# mainboard-revb.net
KiCad netlist of a schematic drawn in EAGLE
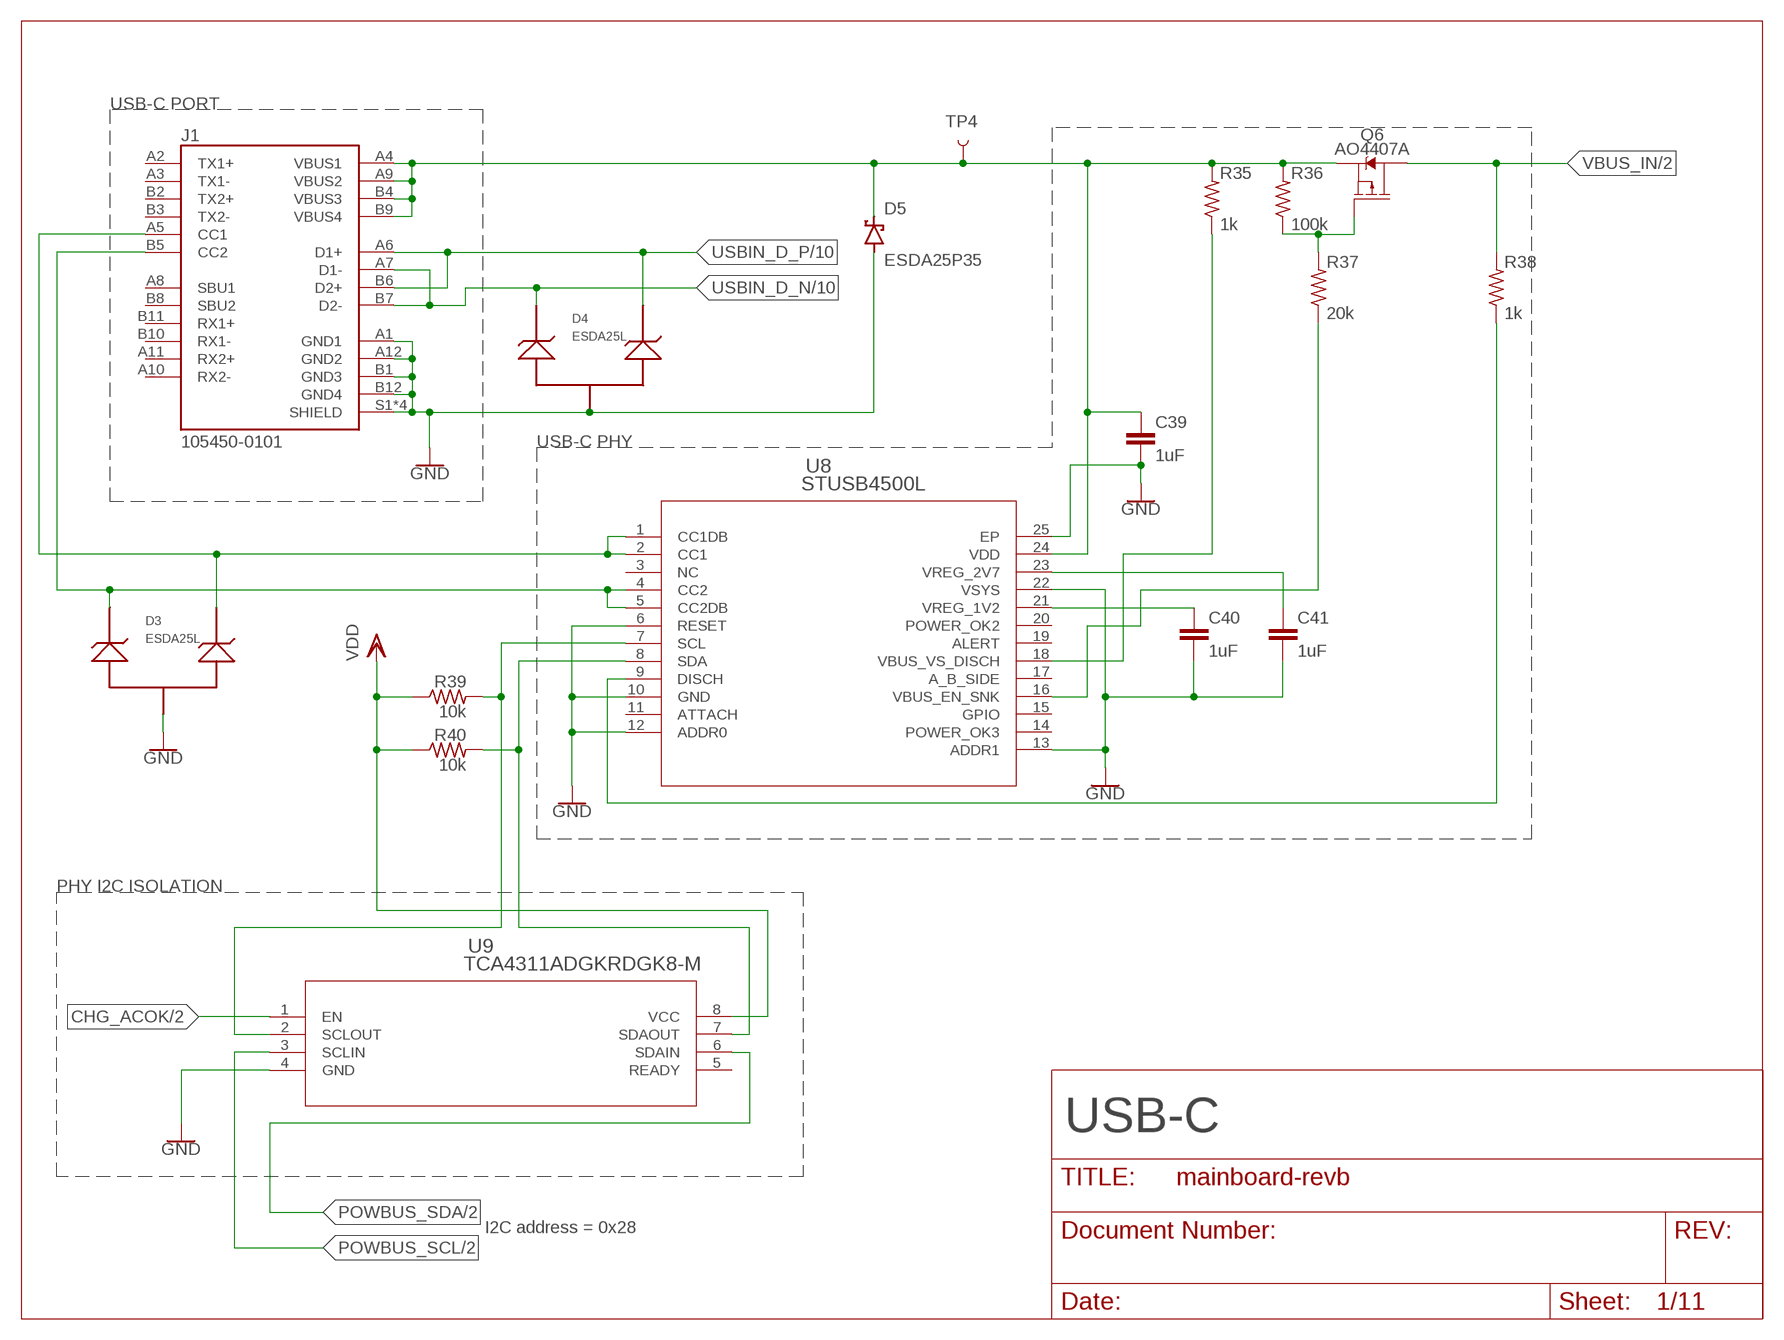
[diagram p0: schematic, sheet 1]
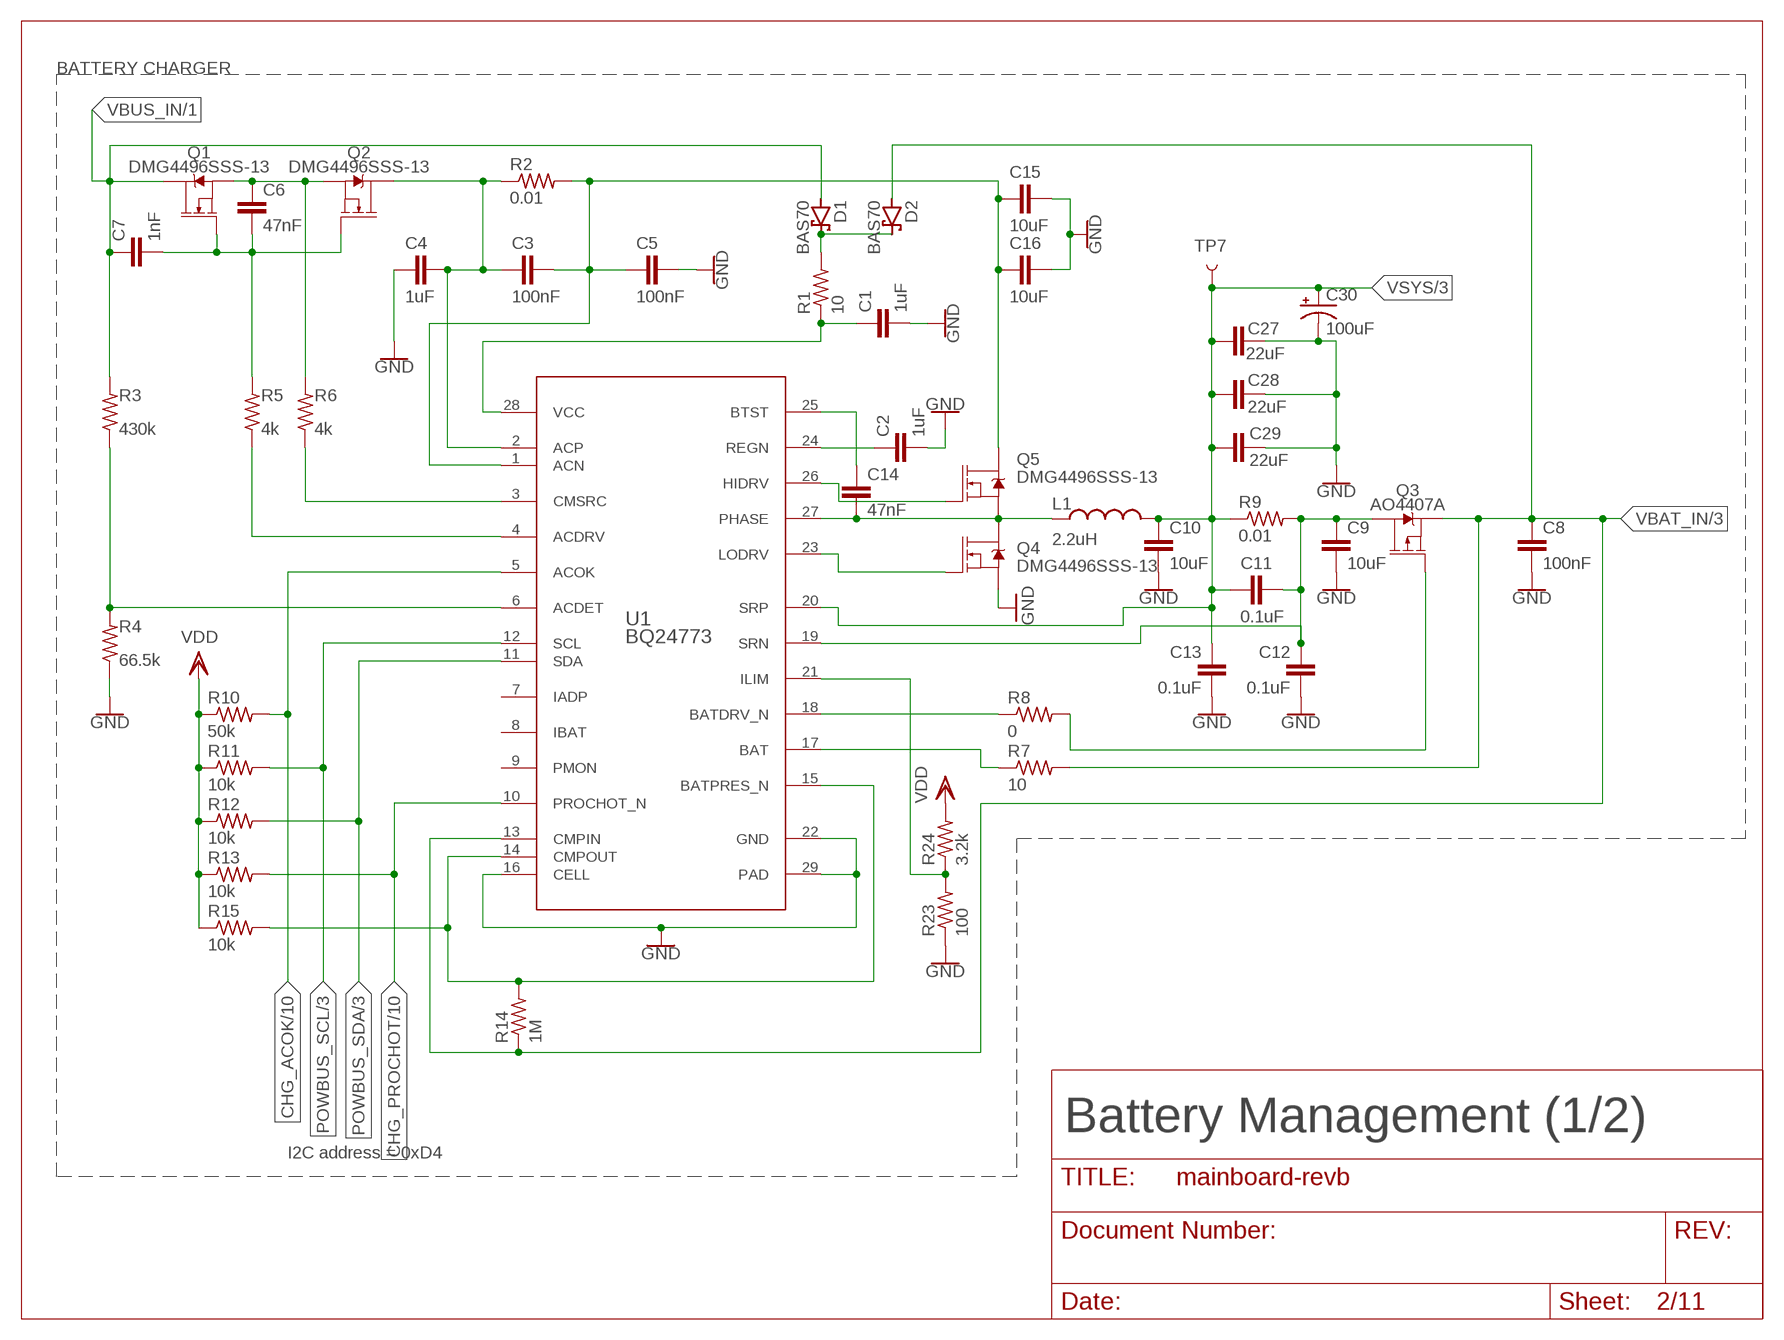
[diagram p1: schematic, sheet 2]
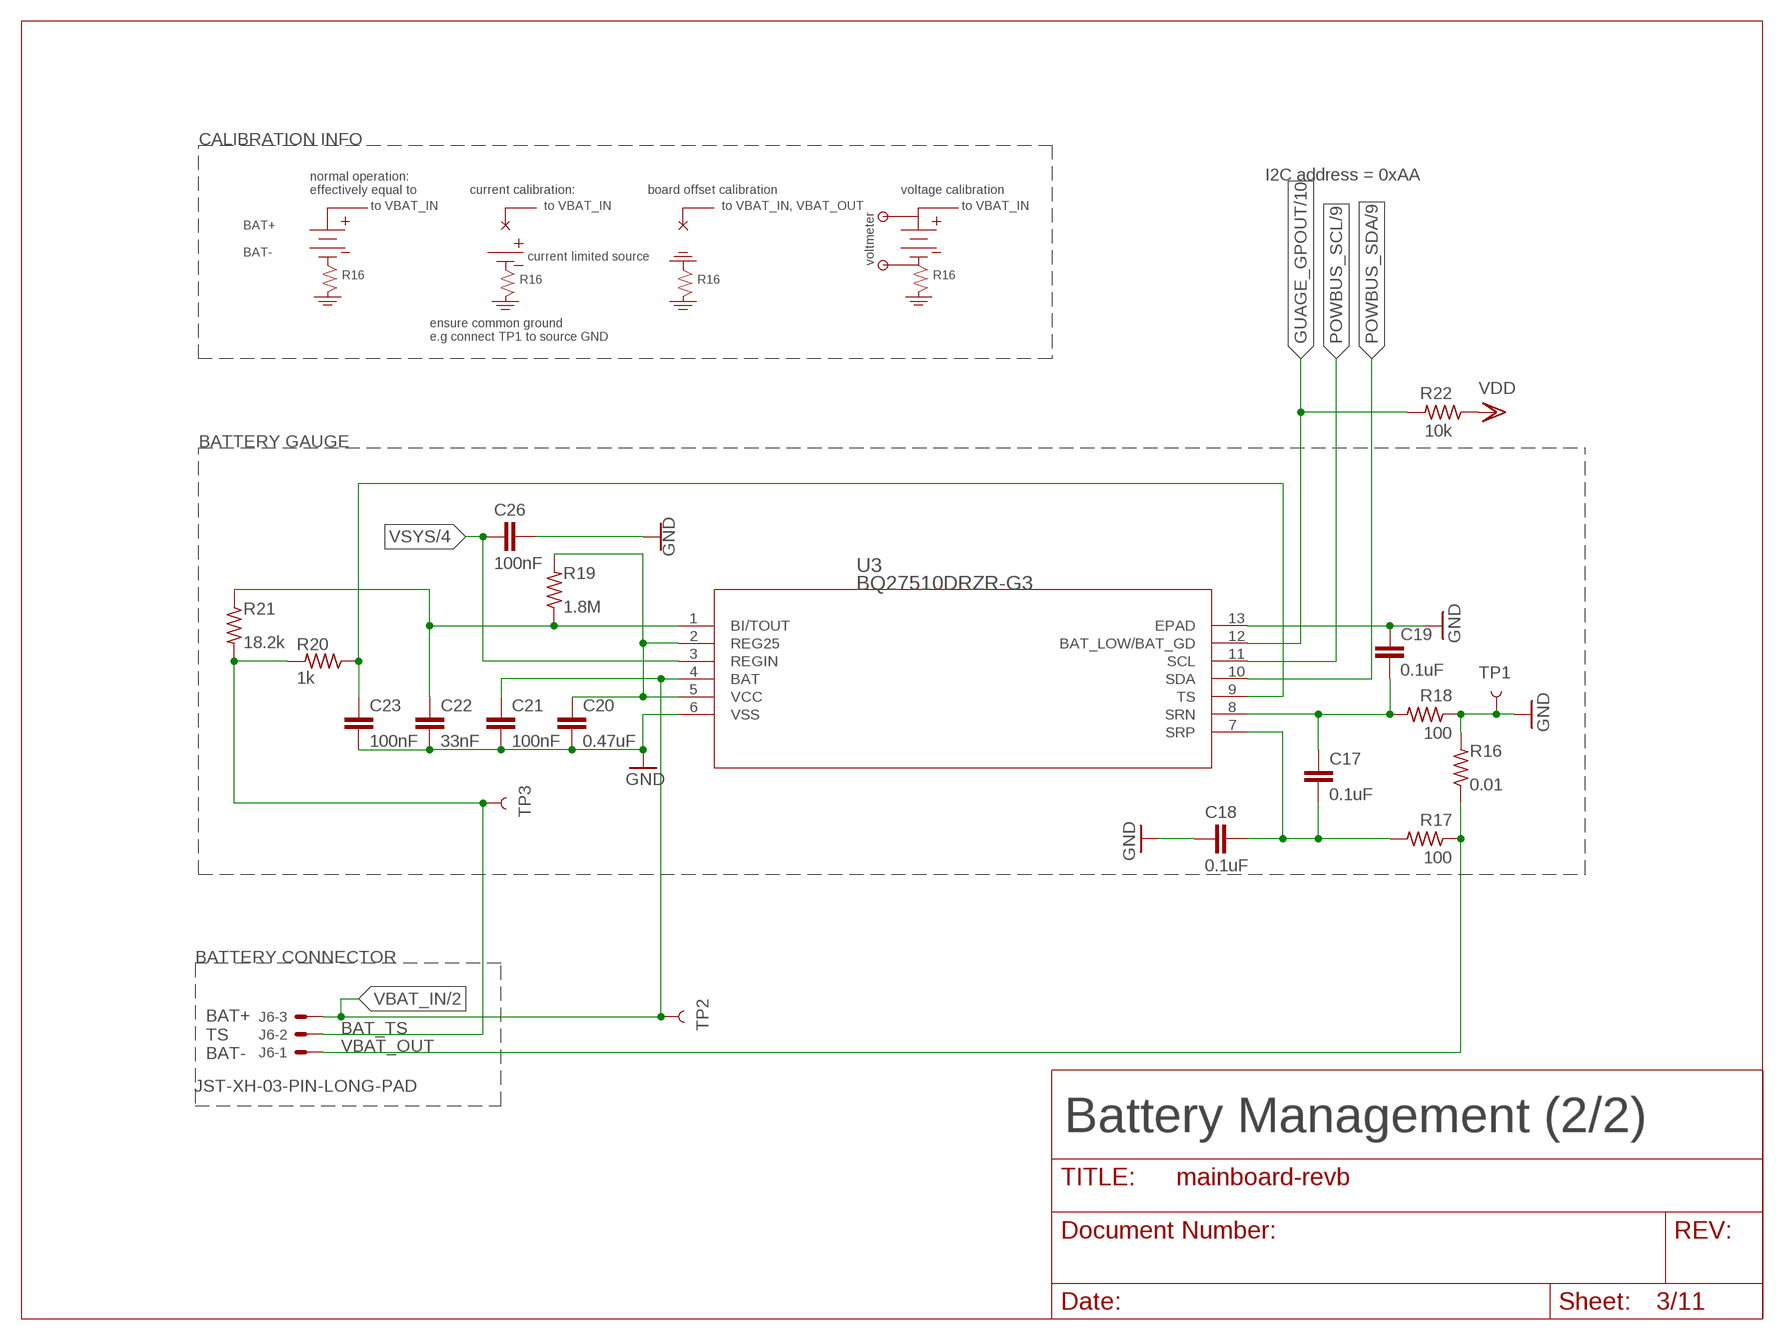
[diagram p2: schematic, sheet 3]
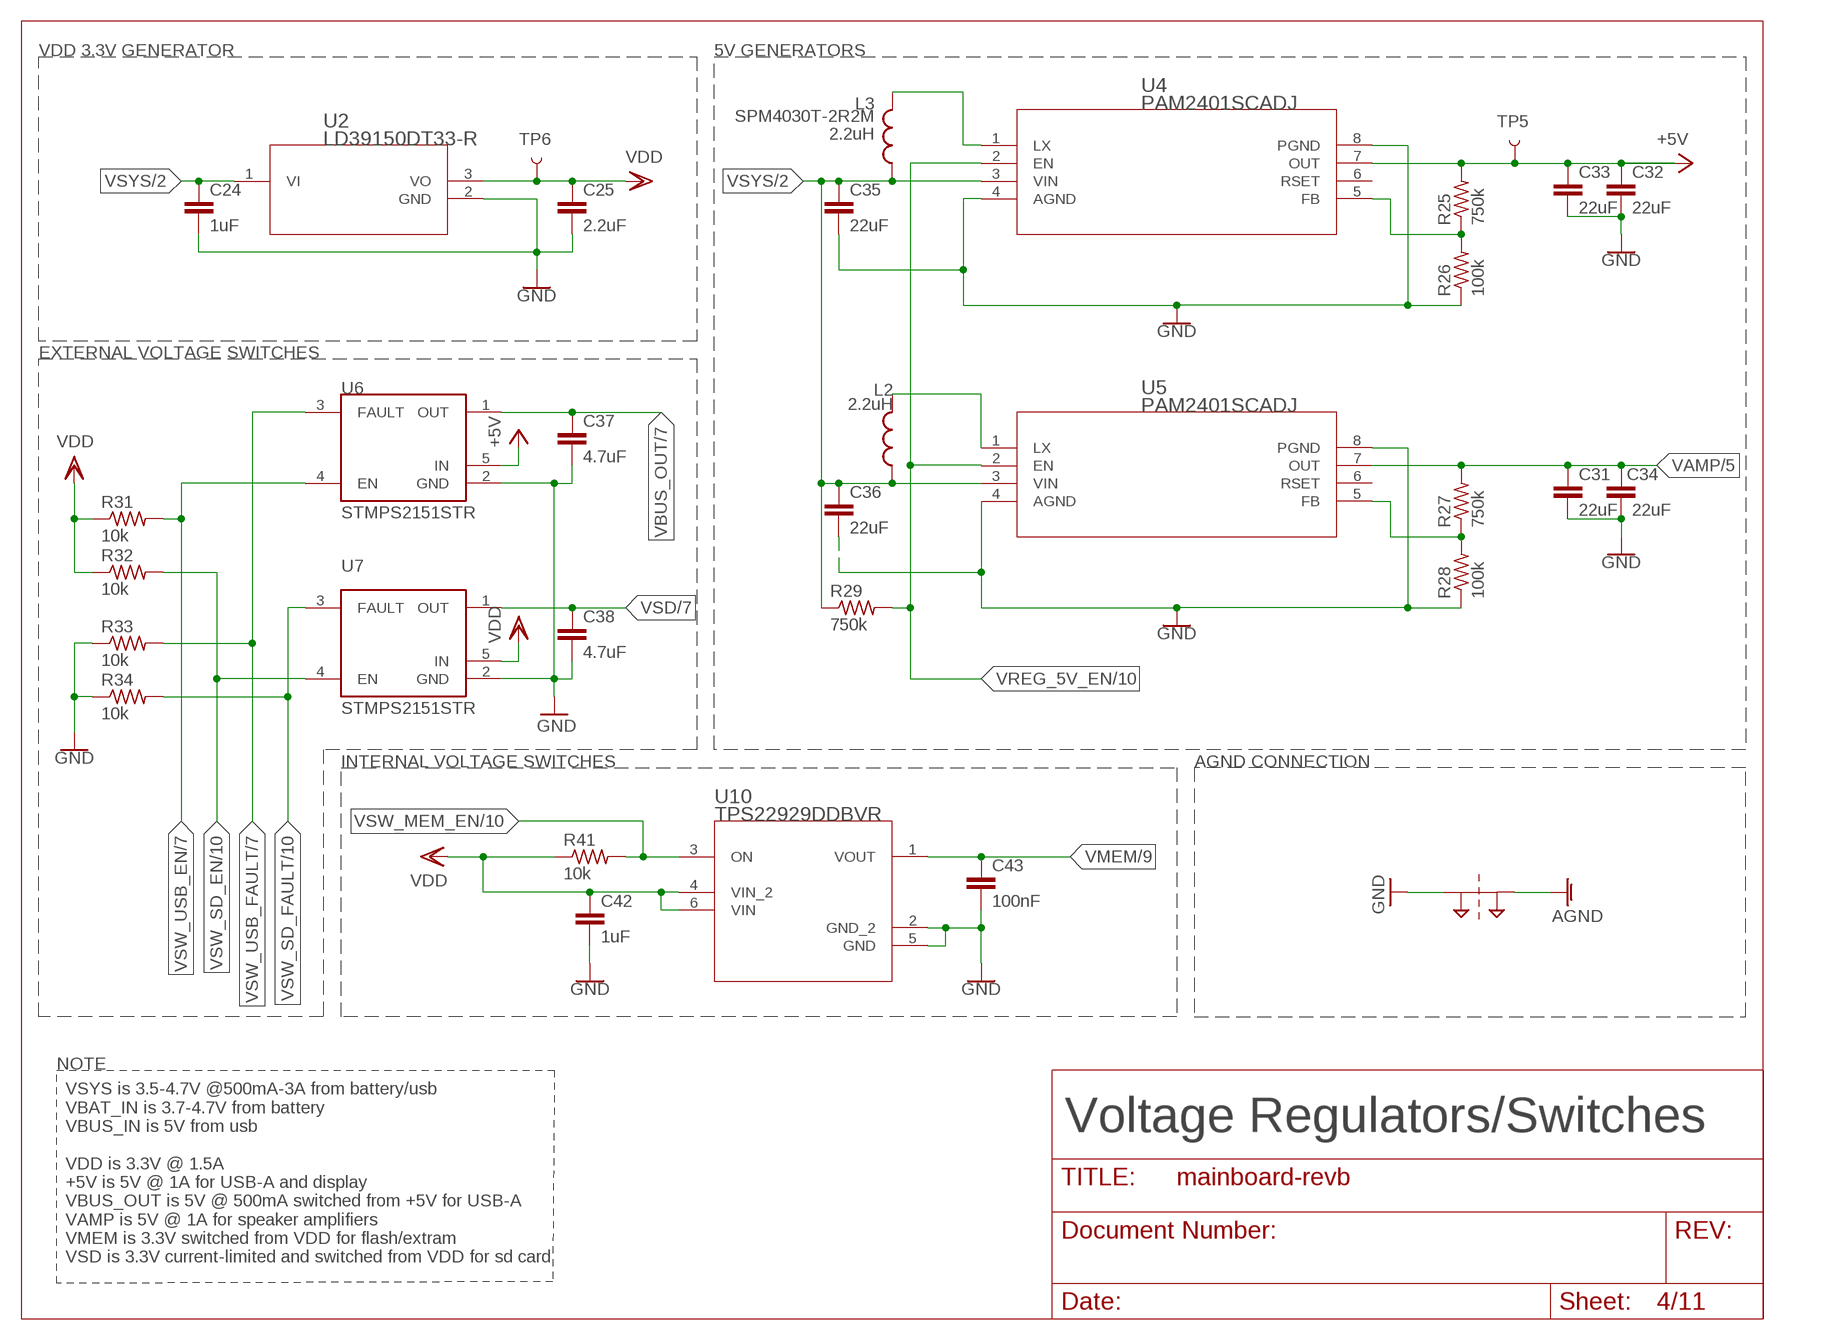
[diagram p3: schematic, sheet 4]
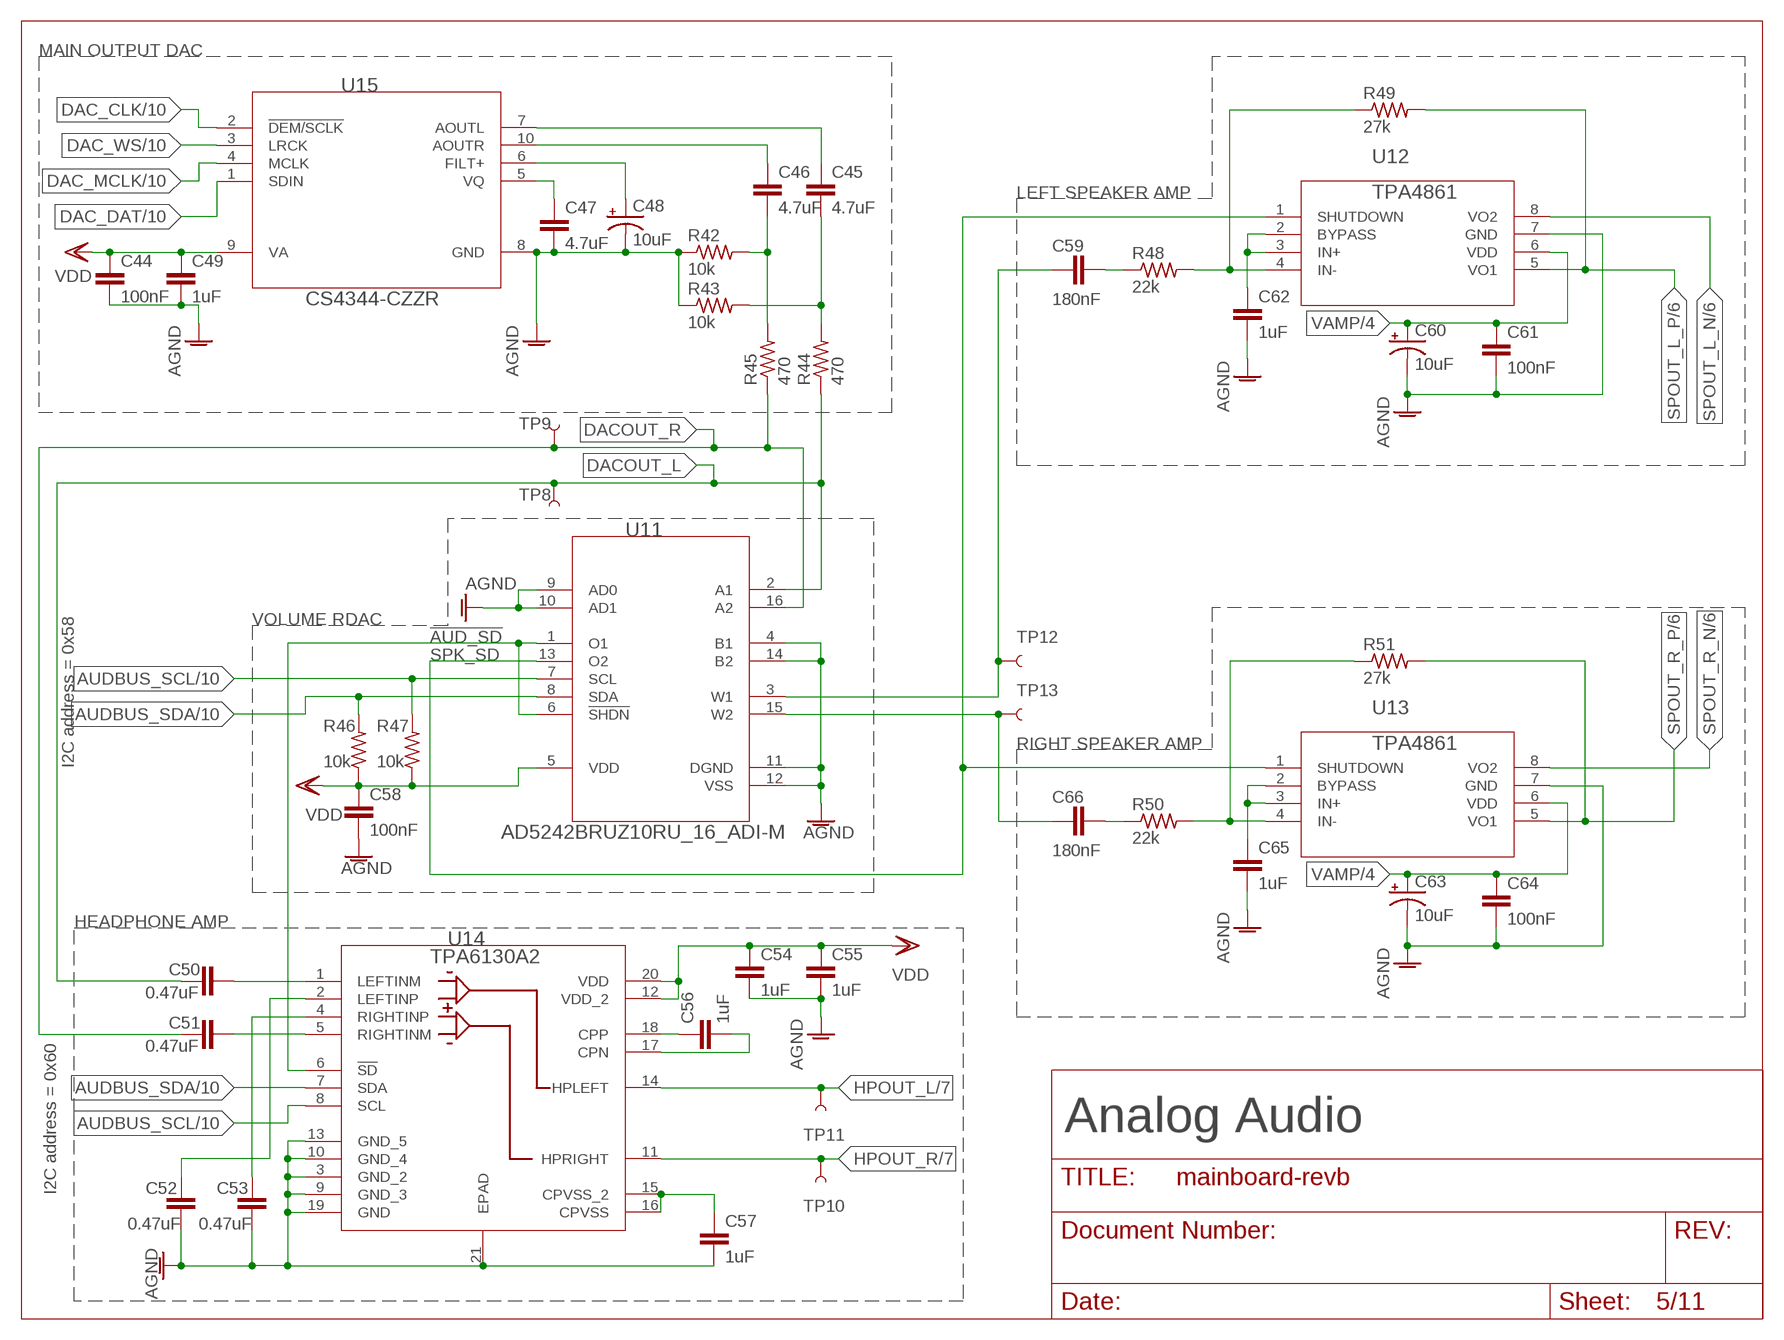
[diagram p4: schematic, sheet 5]
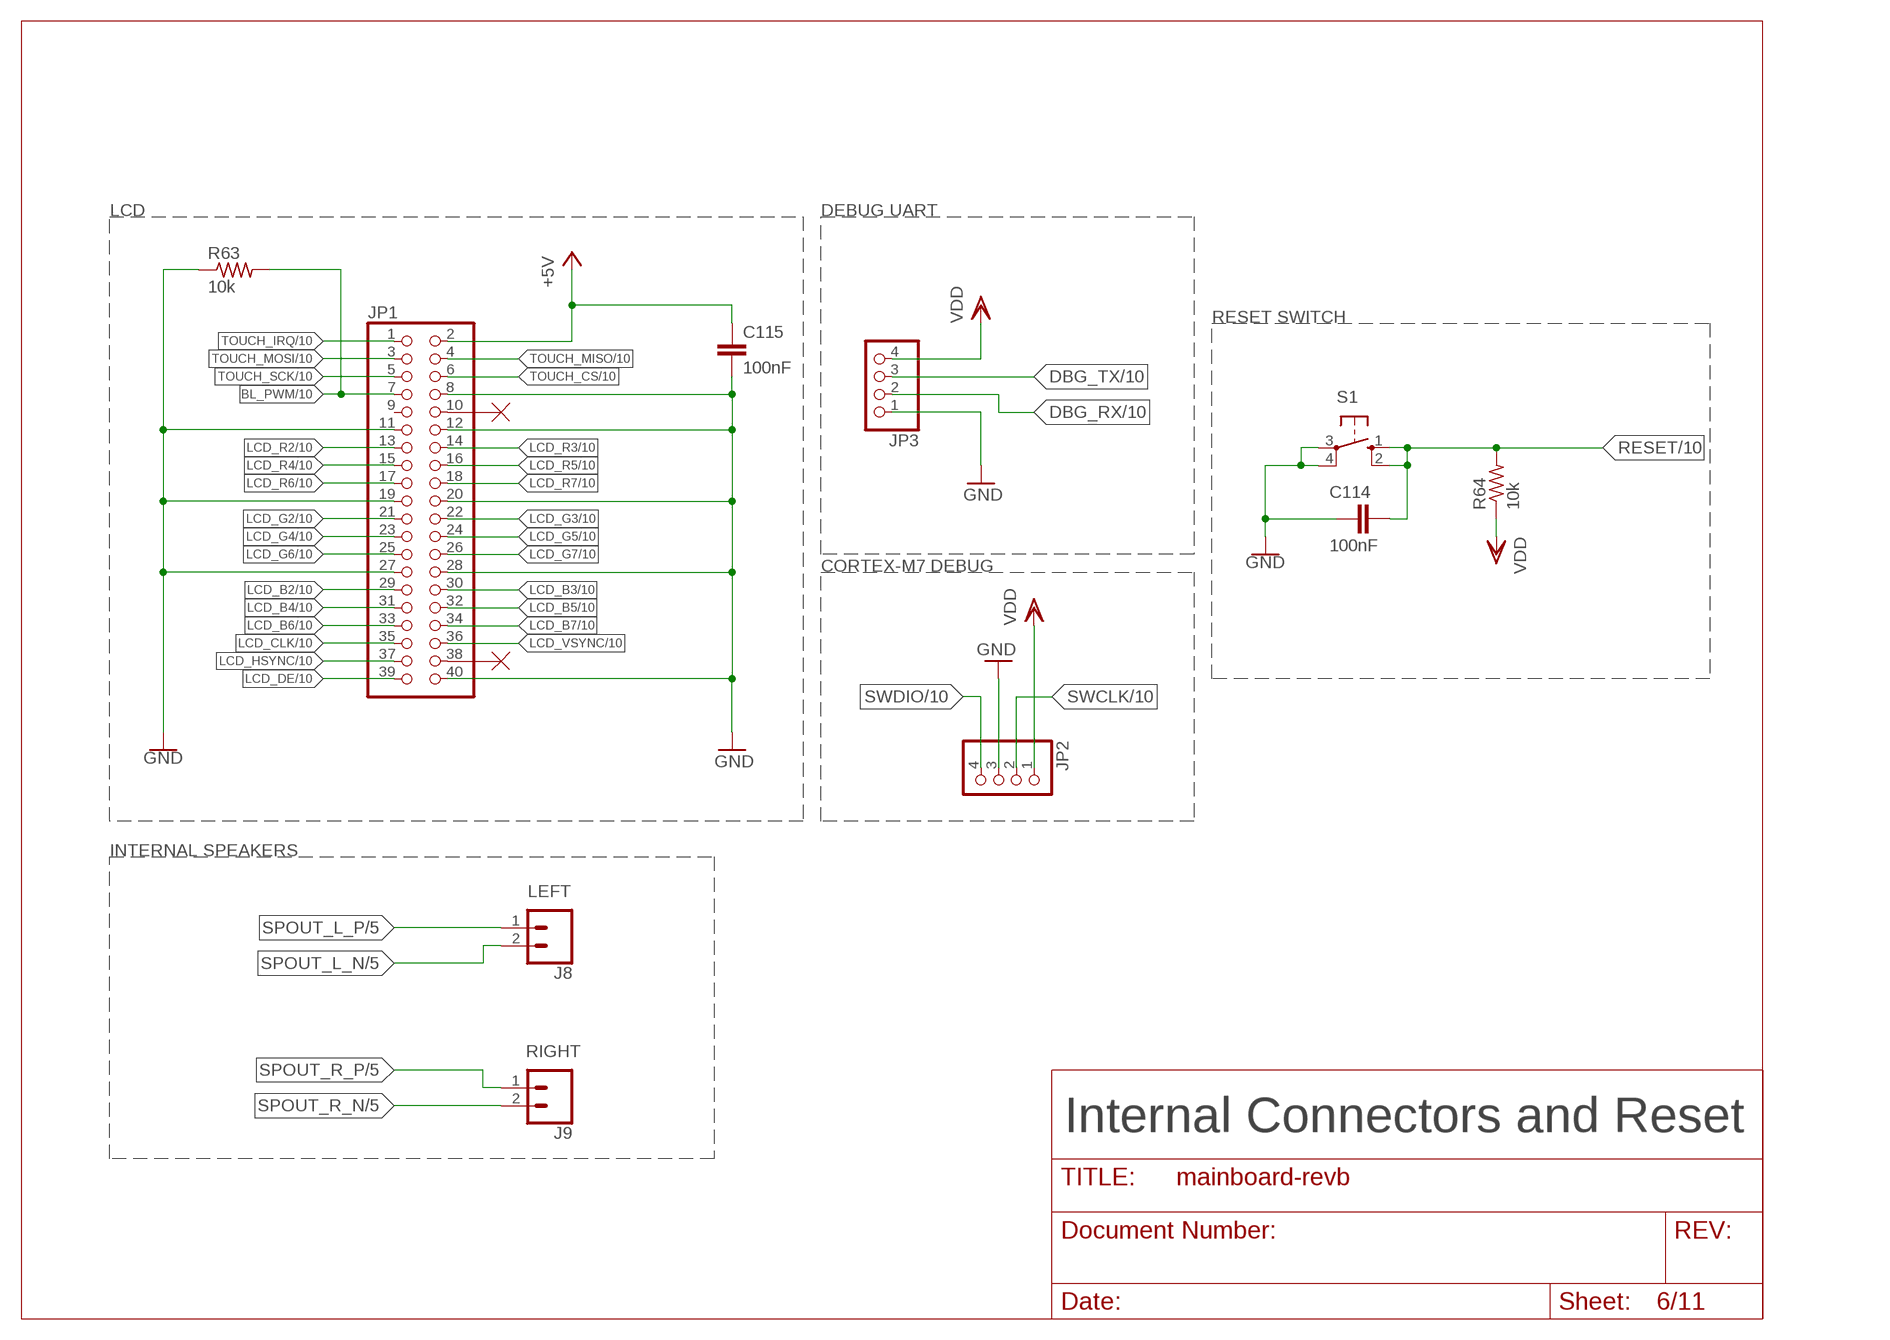
[diagram p5: schematic, sheet 6]
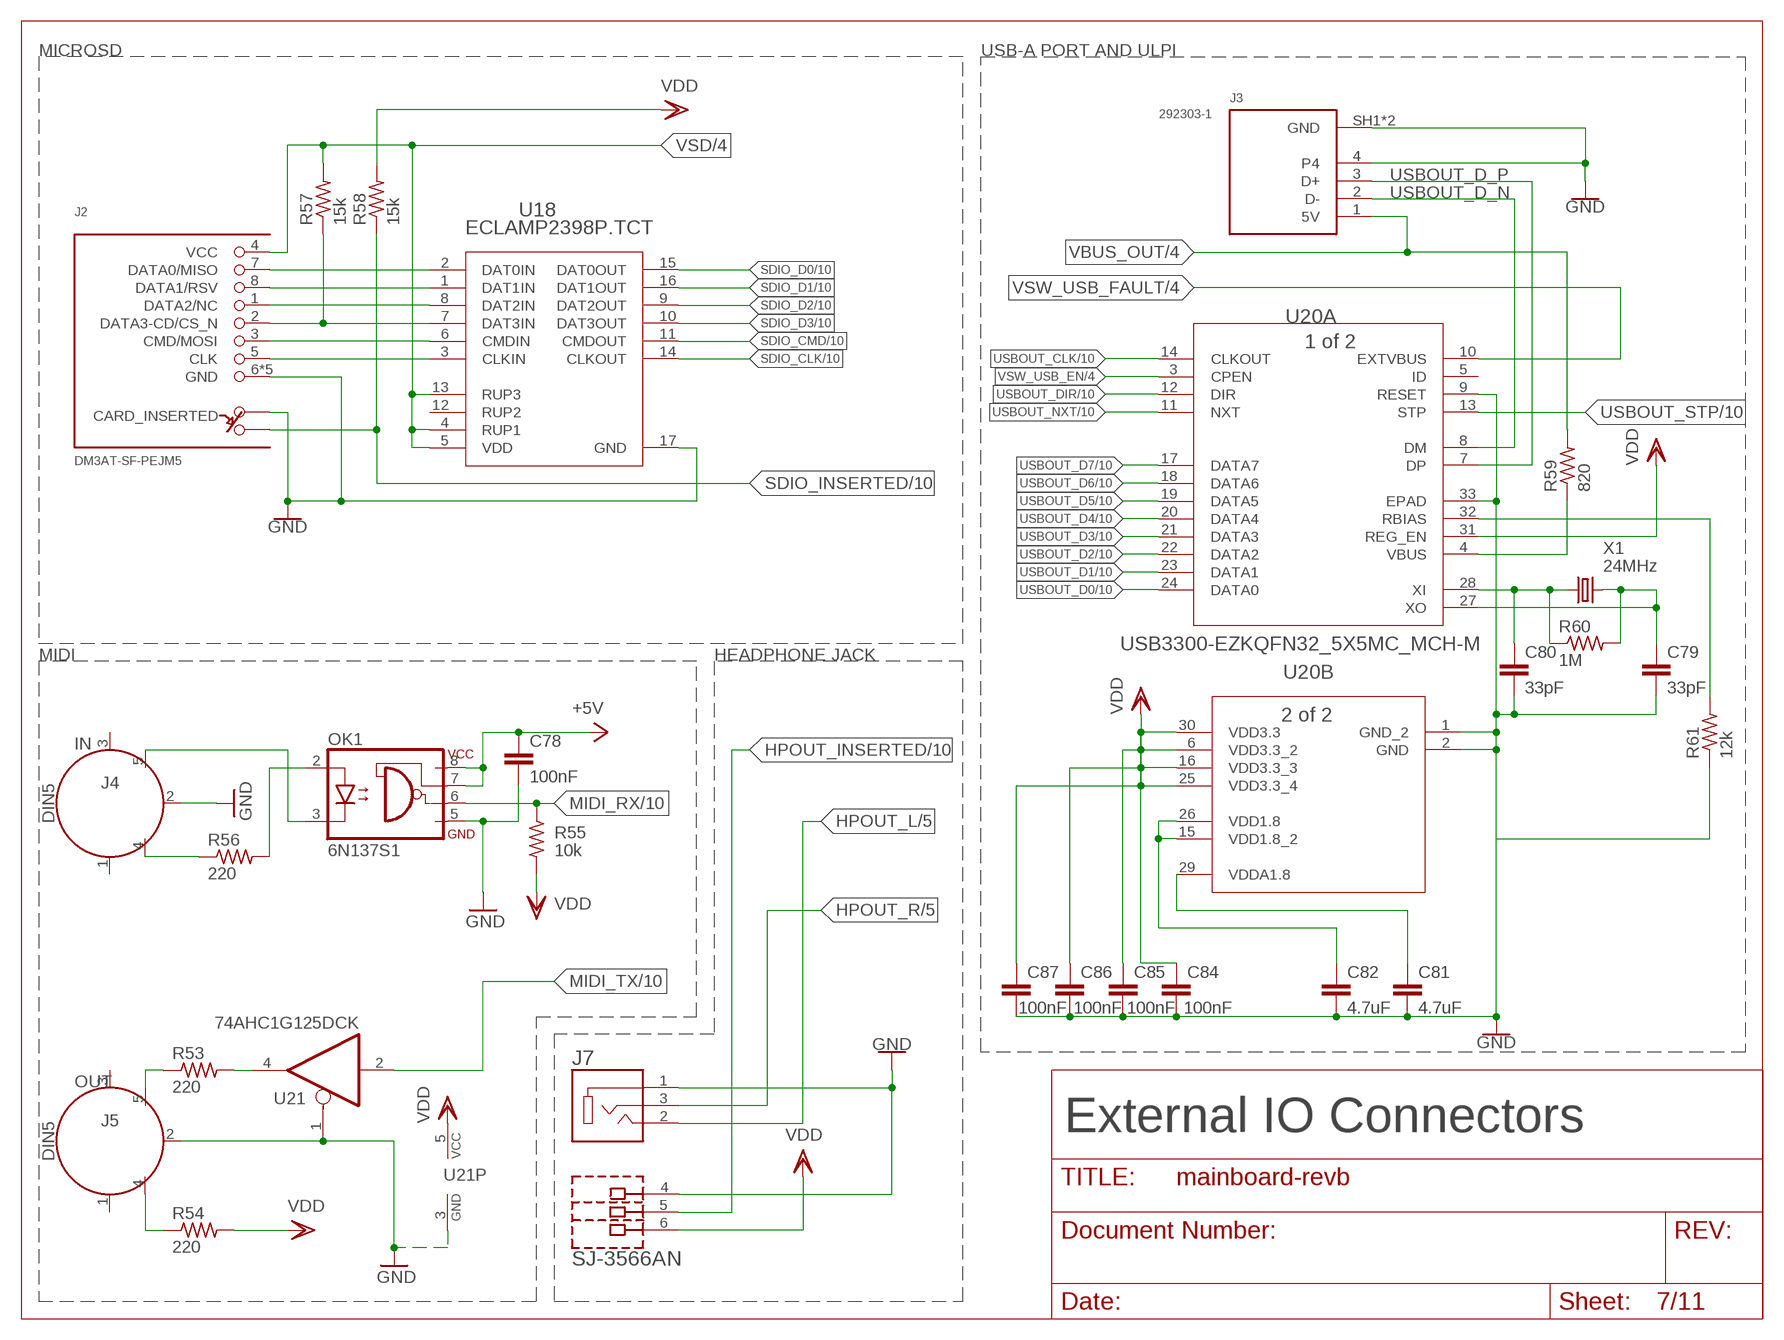
[diagram p6: schematic, sheet 7]
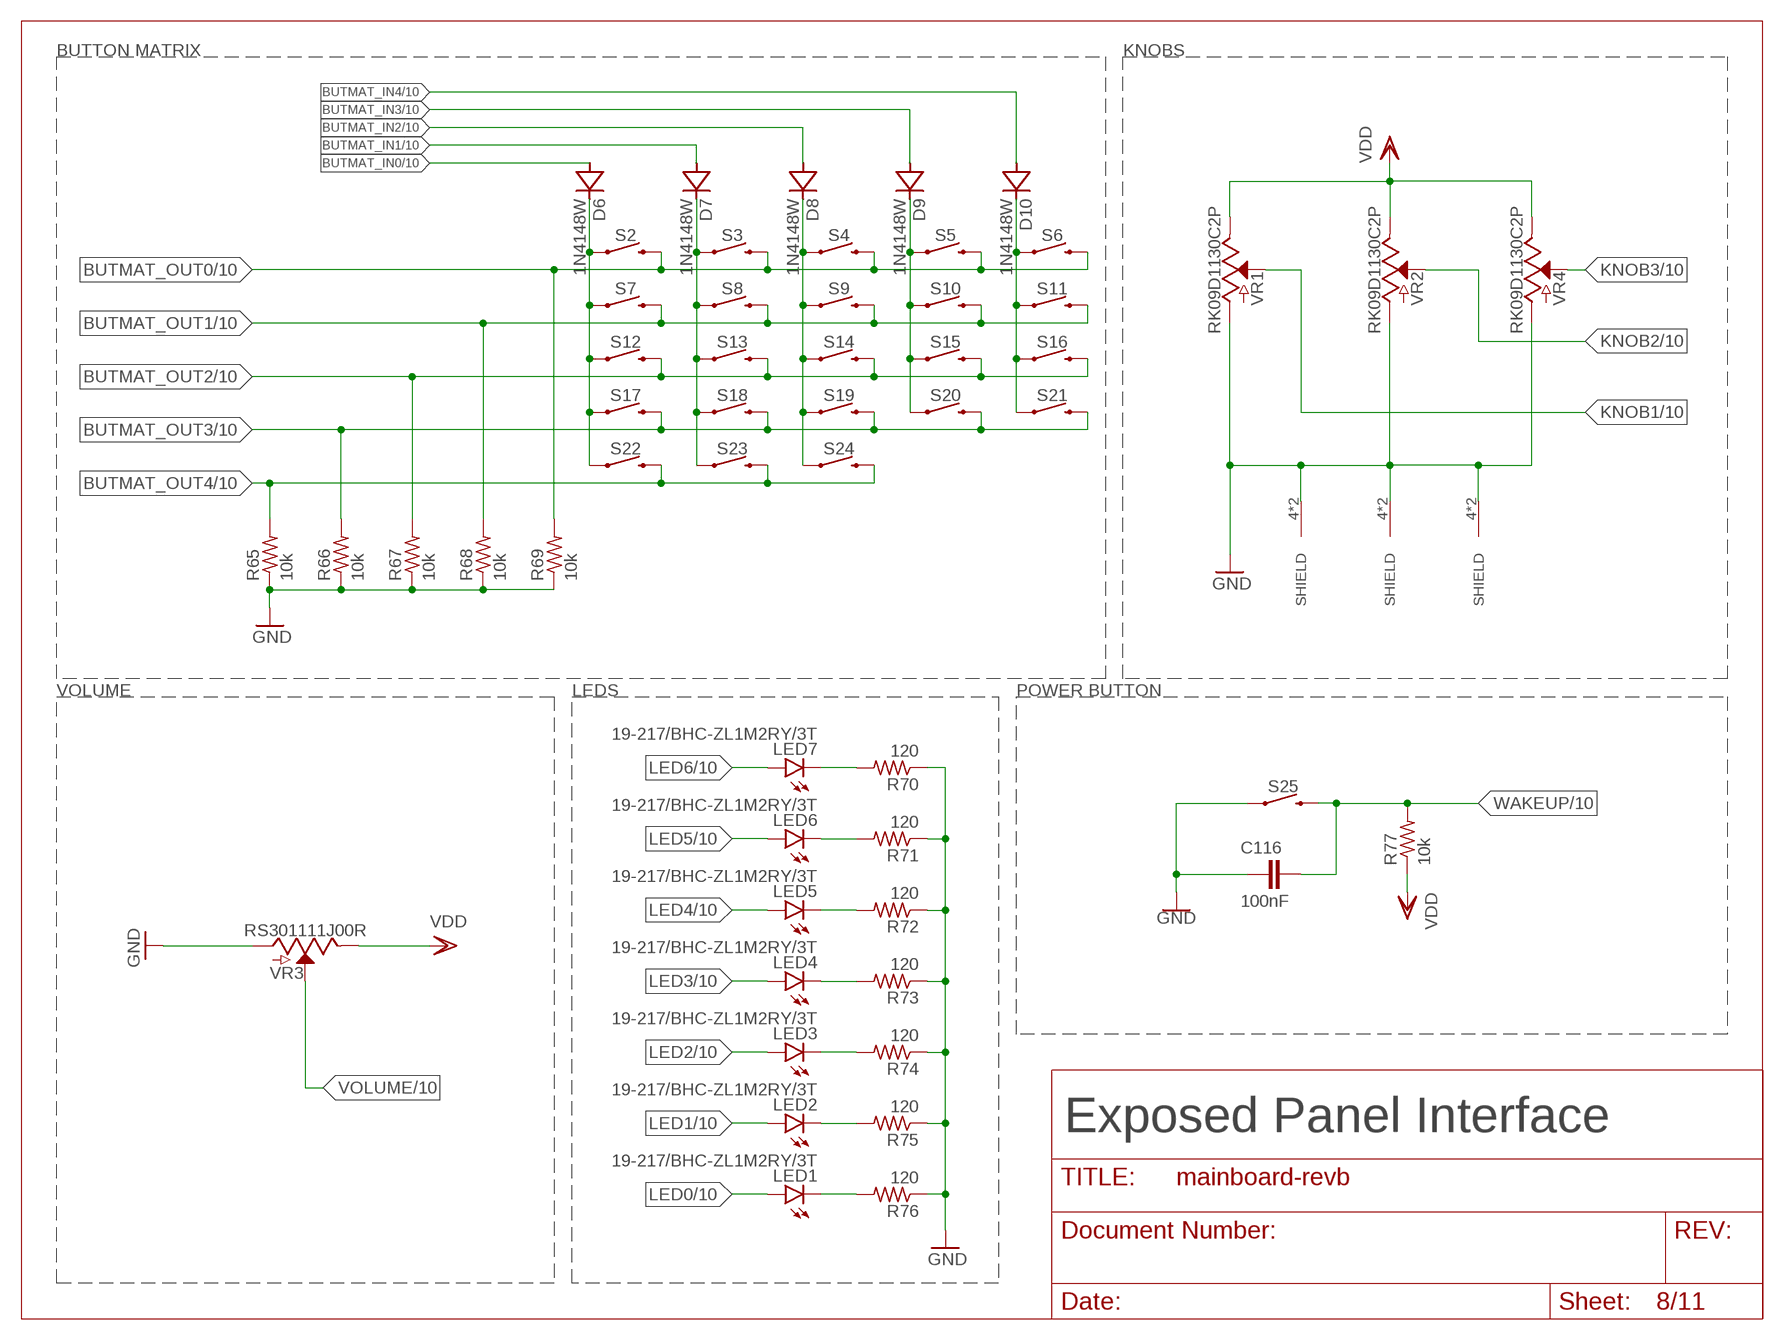
[diagram p7: schematic, sheet 8]
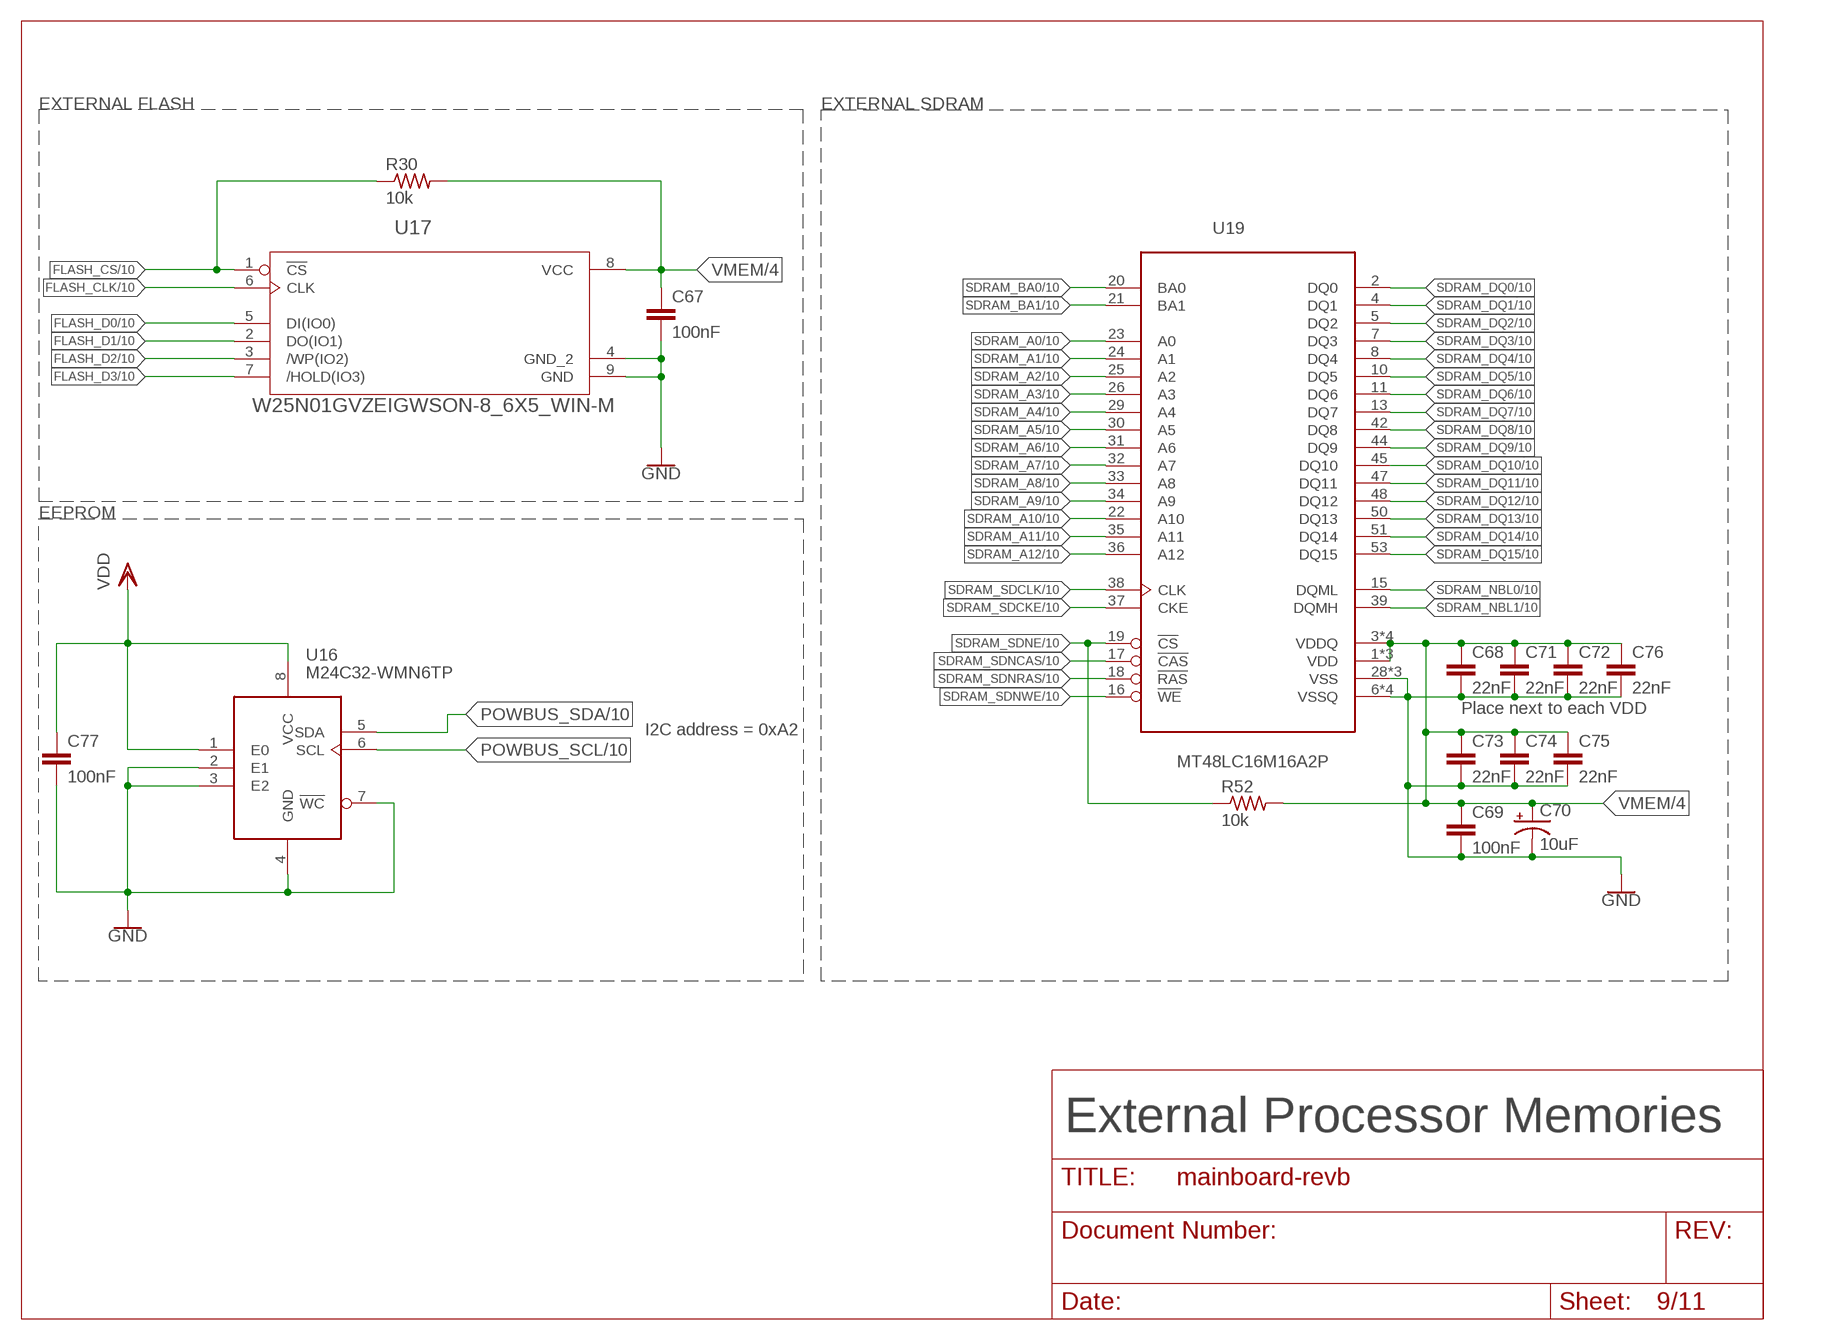
[diagram p8: schematic, sheet 9]
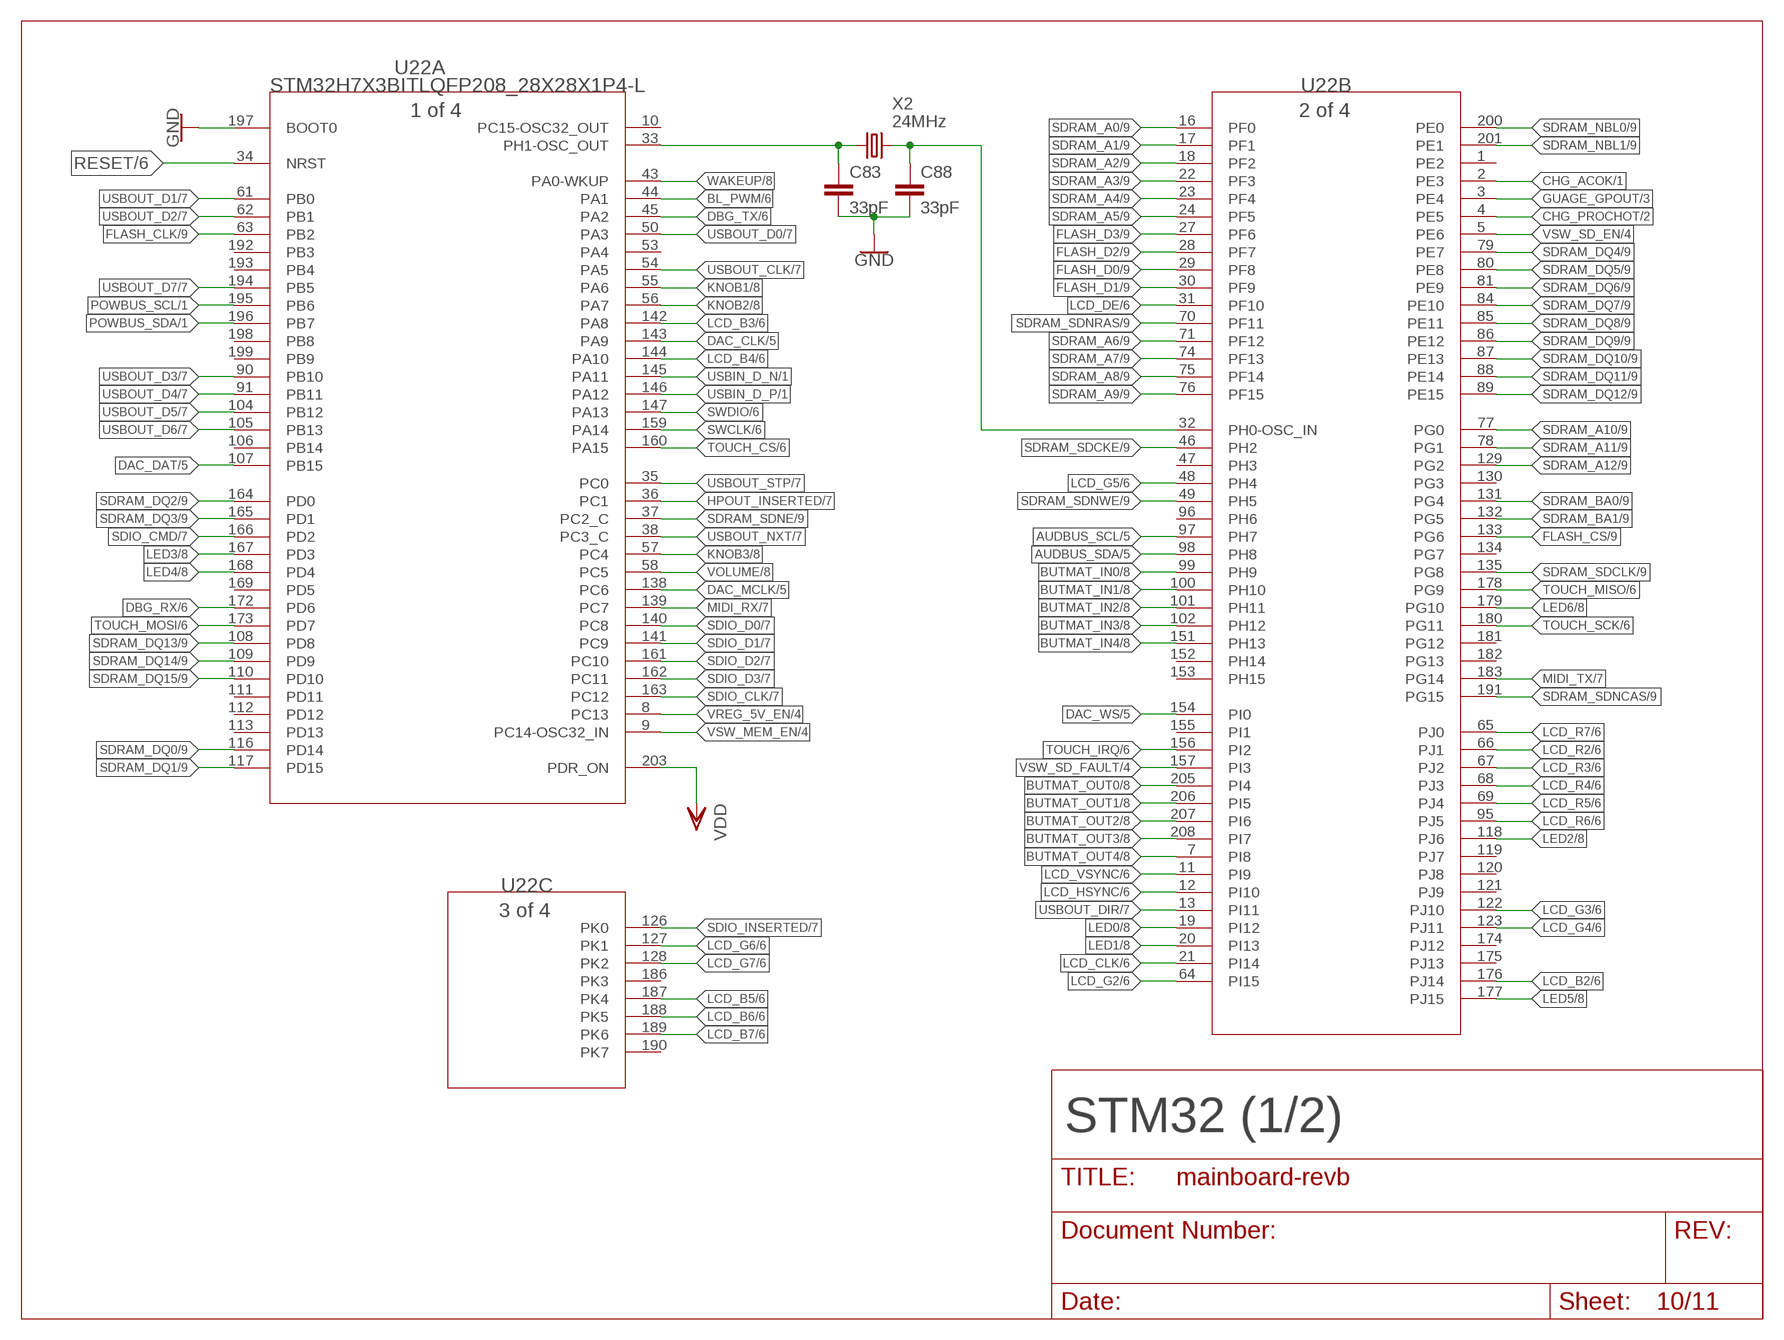
[diagram p9: schematic, sheet 10]
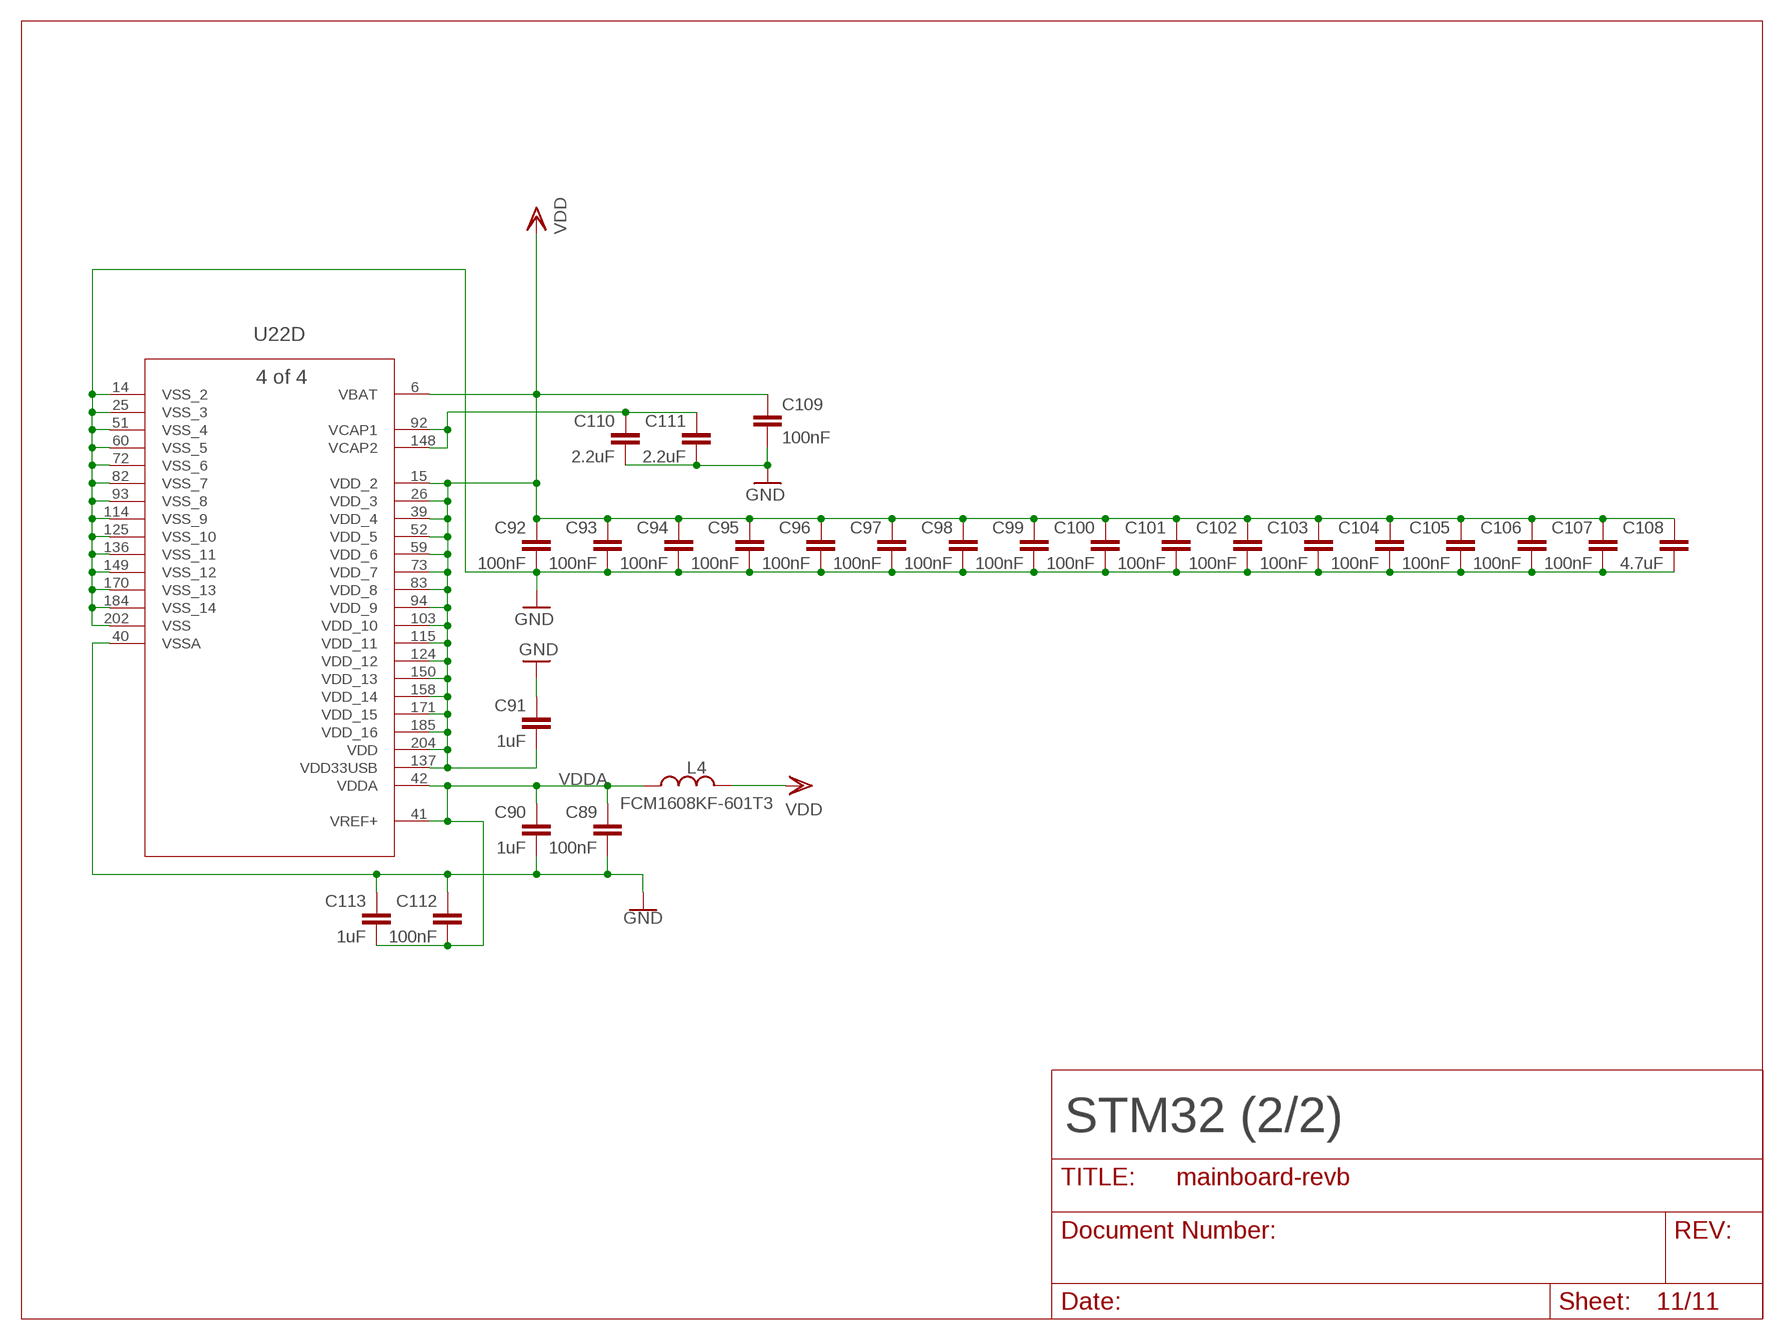
[diagram p10: schematic, sheet 11]

(export (version "E")
  (design (tool "Eeschema 10.0.6"))
  (components
    (comp (ref "C17")
      (value "0.1uF")
      (footprint "eagle-import:C0402")
      (libsource (lib "eagle-import") (part "C-EUC0402"))
    )
    (comp (ref "C18")
      (value "0.1uF")
      (footprint "eagle-import:C0402")
      (libsource (lib "eagle-import") (part "C-EUC0402"))
    )
    (comp (ref "C19")
      (value "0.1uF")
      (footprint "eagle-import:C0402")
      (libsource (lib "eagle-import") (part "C-EUC0402"))
    )
    (comp (ref "C20")
      (value "0.47uF")
      (footprint "eagle-import:C0402")
      (libsource (lib "eagle-import") (part "C-EUC0402"))
    )
    (comp (ref "C21")
      (value "100nF")
      (footprint "eagle-import:C0402")
      (libsource (lib "eagle-import") (part "C-EUC0402"))
    )
    (comp (ref "C22")
      (value "33nF")
      (footprint "eagle-import:C0402")
      (libsource (lib "eagle-import") (part "C-EUC0402"))
    )
    (comp (ref "C23")
      (value "100nF")
      (footprint "eagle-import:C0402")
      (libsource (lib "eagle-import") (part "C-EUC0402"))
    )
    (comp (ref "C26")
      (value "100nF")
      (footprint "eagle-import:C0402")
      (libsource (lib "eagle-import") (part "C-EUC0402"))
    )
    (comp (ref "J6")
      (value "JST-XH-03-PIN-LONG-PAD")
      (footprint "eagle-import:JST-XH-03-PACKAGE-LONG-PAD")
      (libsource (lib "eagle-import") (part "JST-XH-03-PIN-LONG-PAD"))
    )
    (comp (ref "R16")
      (value "0.01")
      (footprint "eagle-import:R0402")
      (libsource (lib "eagle-import") (part "R-US_R0402"))
    )
    (comp (ref "R17")
      (value "100")
      (footprint "eagle-import:R0402")
      (libsource (lib "eagle-import") (part "R-US_R0402"))
    )
    (comp (ref "R18")
      (value "100")
      (footprint "eagle-import:R0402")
      (libsource (lib "eagle-import") (part "R-US_R0402"))
    )
    (comp (ref "R19")
      (value "1.8M")
      (footprint "eagle-import:R0402")
      (libsource (lib "eagle-import") (part "R-US_R0402"))
    )
    (comp (ref "R20")
      (value "1k")
      (footprint "eagle-import:R0402")
      (libsource (lib "eagle-import") (part "R-US_R0402"))
    )
    (comp (ref "R21")
      (value "18.2k")
      (footprint "eagle-import:R0402")
      (libsource (lib "eagle-import") (part "R-US_R0402"))
    )
    (comp (ref "R22")
      (value "10k")
      (footprint "eagle-import:R0402")
      (libsource (lib "eagle-import") (part "R-US_R0402"))
    )
    (comp (ref "TP1")
      (value "TEST-POINT3X4")
      (footprint "eagle-import:PAD.03X.04")
      (libsource (lib "eagle-import") (part "TEST-POINT3X4"))
    )
    (comp (ref "TP2")
      (value "TEST-POINT3X4")
      (footprint "eagle-import:PAD.03X.04")
      (libsource (lib "eagle-import") (part "TEST-POINT3X4"))
    )
    (comp (ref "TP3")
      (value "TEST-POINT3X4")
      (footprint "eagle-import:PAD.03X.04")
      (libsource (lib "eagle-import") (part "TEST-POINT3X4"))
    )
    (comp (ref "U3")
      (value "BQ27510DRZR-G3")
      (footprint "eagle-import:DRZ12_1P95X2P45_TEX")
      (fields (field (name "MANUFACTURER") "Texas Instruments"))
      (libsource (lib "eagle-import") (part "BQ27510DRZR-G3"))
    )
    (comp (ref "C1")
      (value "1uF")
      (footprint "eagle-import:C0402")
      (libsource (lib "eagle-import") (part "C-EUC0402"))
    )
    (comp (ref "C2")
      (value "1uF")
      (footprint "eagle-import:C0402")
      (libsource (lib "eagle-import") (part "C-EUC0402"))
    )
    (comp (ref "C3")
      (value "100nF")
      (footprint "eagle-import:C0402")
      (libsource (lib "eagle-import") (part "C-EUC0402"))
    )
    (comp (ref "C4")
      (value "1uF")
      (footprint "eagle-import:C0402")
      (libsource (lib "eagle-import") (part "C-EUC0402"))
    )
    (comp (ref "C5")
      (value "100nF")
      (footprint "eagle-import:C0402")
      (libsource (lib "eagle-import") (part "C-EUC0402"))
    )
    (comp (ref "C6")
      (value "47nF")
      (footprint "eagle-import:C0402")
      (libsource (lib "eagle-import") (part "C-EUC0402"))
    )
    (comp (ref "C7")
      (value "1nF")
      (footprint "eagle-import:C0402")
      (libsource (lib "eagle-import") (part "C-EUC0402"))
    )
    (comp (ref "C8")
      (value "100nF")
      (footprint "eagle-import:C0402")
      (libsource (lib "eagle-import") (part "C-EUC0402"))
    )
    (comp (ref "C9")
      (value "10uF")
      (footprint "eagle-import:C0402")
      (libsource (lib "eagle-import") (part "C-EUC0402"))
    )
    (comp (ref "C10")
      (value "10uF")
      (footprint "eagle-import:C0402")
      (libsource (lib "eagle-import") (part "C-EUC0402"))
    )
    (comp (ref "C11")
      (value "0.1uF")
      (footprint "eagle-import:C0402")
      (libsource (lib "eagle-import") (part "C-EUC0402"))
    )
    (comp (ref "C12")
      (value "0.1uF")
      (footprint "eagle-import:C0402")
      (libsource (lib "eagle-import") (part "C-EUC0402"))
    )
    (comp (ref "C13")
      (value "0.1uF")
      (footprint "eagle-import:C0402")
      (libsource (lib "eagle-import") (part "C-EUC0402"))
    )
    (comp (ref "C14")
      (value "47nF")
      (footprint "eagle-import:C0402")
      (libsource (lib "eagle-import") (part "C-EUC0402"))
    )
    (comp (ref "C15")
      (value "10uF")
      (footprint "eagle-import:C0402")
      (libsource (lib "eagle-import") (part "C-EUC0402"))
    )
    (comp (ref "C16")
      (value "10uF")
      (footprint "eagle-import:C0402")
      (libsource (lib "eagle-import") (part "C-EUC0402"))
    )
    (comp (ref "C27")
      (value "22uF")
      (footprint "eagle-import:C0402")
      (libsource (lib "eagle-import") (part "C-EUC0402"))
    )
    (comp (ref "C28")
      (value "22uF")
      (footprint "eagle-import:C0402")
      (libsource (lib "eagle-import") (part "C-EUC0402"))
    )
    (comp (ref "C29")
      (value "22uF")
      (footprint "eagle-import:C0402")
      (libsource (lib "eagle-import") (part "C-EUC0402"))
    )
    (comp (ref "C30")
      (value "100uF")
      (footprint "eagle-import:C_6032-28R")
      (libsource (lib "eagle-import") (part "CPOL-USC/6032-28R"))
    )
    (comp (ref "D1")
      (value "BAS70")
      (footprint "eagle-import:SOT23")
      (libsource (lib "eagle-import") (part "BAS70"))
    )
    (comp (ref "D2")
      (value "BAS70")
      (footprint "eagle-import:SOT23")
      (libsource (lib "eagle-import") (part "BAS70"))
    )
    (comp (ref "L1")
      (value "2.2uH")
      (footprint "eagle-import:INDPM7165X300N")
      (libsource (lib "eagle-import") (part "SPM6530T-2R2M"))
    )
    (comp (ref "Q1")
      (value "DMG4496SSS-13")
      (footprint "eagle-import:SOIC8")
      (libsource (lib "eagle-import") (part "DMG4496SSS-13"))
    )
    (comp (ref "Q2")
      (value "DMG4496SSS-13")
      (footprint "eagle-import:SOIC8")
      (libsource (lib "eagle-import") (part "DMG4496SSS-13"))
    )
    (comp (ref "Q3")
      (value "AO4407A")
      (footprint "eagle-import:SOIC8")
      (libsource (lib "eagle-import") (part "AO4407A"))
    )
    (comp (ref "Q4")
      (value "DMG4496SSS-13")
      (footprint "eagle-import:SOIC8")
      (libsource (lib "eagle-import") (part "DMG4496SSS-13"))
    )
    (comp (ref "Q5")
      (value "DMG4496SSS-13")
      (footprint "eagle-import:SOIC8")
      (libsource (lib "eagle-import") (part "DMG4496SSS-13"))
    )
    (comp (ref "R1")
      (value "10")
      (footprint "eagle-import:R0402")
      (libsource (lib "eagle-import") (part "R-US_R0402"))
    )
    (comp (ref "R2")
      (value "0.01")
      (footprint "eagle-import:R0402")
      (libsource (lib "eagle-import") (part "R-US_R0402"))
    )
    (comp (ref "R3")
      (value "430k")
      (footprint "eagle-import:R0402")
      (libsource (lib "eagle-import") (part "R-US_R0402"))
    )
    (comp (ref "R4")
      (value "66.5k")
      (footprint "eagle-import:R0402")
      (libsource (lib "eagle-import") (part "R-US_R0402"))
    )
    (comp (ref "R5")
      (value "4k")
      (footprint "eagle-import:R0402")
      (libsource (lib "eagle-import") (part "R-US_R0402"))
    )
    (comp (ref "R6")
      (value "4k")
      (footprint "eagle-import:R0402")
      (libsource (lib "eagle-import") (part "R-US_R0402"))
    )
    (comp (ref "R7")
      (value "10")
      (footprint "eagle-import:R0402")
      (libsource (lib "eagle-import") (part "R-US_R0402"))
    )
    (comp (ref "R8")
      (value "0")
      (footprint "eagle-import:R0402")
      (libsource (lib "eagle-import") (part "R-US_R0402"))
    )
    (comp (ref "R9")
      (value "0.01")
      (footprint "eagle-import:R0402")
      (libsource (lib "eagle-import") (part "R-US_R0402"))
    )
    (comp (ref "R10")
      (value "50k")
      (footprint "eagle-import:R0402")
      (libsource (lib "eagle-import") (part "R-US_R0402"))
    )
    (comp (ref "R11")
      (value "10k")
      (footprint "eagle-import:R0402")
      (libsource (lib "eagle-import") (part "R-US_R0402"))
    )
    (comp (ref "R12")
      (value "10k")
      (footprint "eagle-import:R0402")
      (libsource (lib "eagle-import") (part "R-US_R0402"))
    )
    (comp (ref "R13")
      (value "10k")
      (footprint "eagle-import:R0402")
      (libsource (lib "eagle-import") (part "R-US_R0402"))
    )
    (comp (ref "R14")
      (value "1M")
      (footprint "eagle-import:R0402")
      (libsource (lib "eagle-import") (part "R-US_R0402"))
    )
    (comp (ref "R15")
      (value "10k")
      (footprint "eagle-import:R0402")
      (libsource (lib "eagle-import") (part "R-US_R0402"))
    )
    (comp (ref "R23")
      (value "100")
      (footprint "eagle-import:R0402")
      (libsource (lib "eagle-import") (part "R-US_R0402"))
    )
    (comp (ref "R24")
      (value "3.2k")
      (footprint "eagle-import:R0402")
      (libsource (lib "eagle-import") (part "R-US_R0402"))
    )
    (comp (ref "TP7")
      (value "TEST-POINT3X4")
      (footprint "eagle-import:PAD.03X.04")
      (libsource (lib "eagle-import") (part "SparkFun-Connectors_513_TEST-POINT3X4"))
    )
    (comp (ref "U1")
      (value "Value")
      (footprint "eagle-import:RUY0028A")
      (fields
        (field (name "ALTERNATE_PARTNUMBER") "BQ24773RUYT")
        (field (name "MANUFACTURER") "Texas Instruments")
        (field (name "PARTNUMBER") "BQ24773RUYR")
      )
      (libsource (lib "eagle-import") (part "BQ24773RUYR"))
    )
    (comp (ref "C78")
      (value "100nF")
      (footprint "eagle-import:C0402")
      (libsource (lib "eagle-import") (part "C-EUC0402"))
    )
    (comp (ref "C79")
      (value "33pF")
      (footprint "eagle-import:C0402")
      (libsource (lib "eagle-import") (part "C-EUC0402"))
    )
    (comp (ref "C80")
      (value "33pF")
      (footprint "eagle-import:C0402")
      (libsource (lib "eagle-import") (part "C-EUC0402"))
    )
    (comp (ref "C81")
      (value "4.7uF")
      (footprint "eagle-import:C0402")
      (libsource (lib "eagle-import") (part "C-EUC0402"))
    )
    (comp (ref "C82")
      (value "4.7uF")
      (footprint "eagle-import:C0402")
      (libsource (lib "eagle-import") (part "C-EUC0402"))
    )
    (comp (ref "C84")
      (value "100nF")
      (footprint "eagle-import:C0402")
      (libsource (lib "eagle-import") (part "C-EUC0402"))
    )
    (comp (ref "C85")
      (value "100nF")
      (footprint "eagle-import:C0402")
      (libsource (lib "eagle-import") (part "C-EUC0402"))
    )
    (comp (ref "C86")
      (value "100nF")
      (footprint "eagle-import:C0402")
      (libsource (lib "eagle-import") (part "C-EUC0402"))
    )
    (comp (ref "C87")
      (value "100nF")
      (footprint "eagle-import:C0402")
      (libsource (lib "eagle-import") (part "C-EUC0402"))
    )
    (comp (ref "J2")
      (value "DM3AT-SF-PEJM5")
      (footprint "eagle-import:DM3AT-SF-PEJM5")
      (fields (field (name "MANUFACTURER") "Hirose Electric Co Ltd"))
      (libsource (lib "eagle-import") (part "DM3AT-SF-PEJM5"))
    )
    (comp (ref "J3")
      (value "292303-1")
      (footprint "eagle-import:TE_292303-1")
      (fields (field (name "MF") "TE Connectivity"))
      (libsource (lib "eagle-import") (part "292303-1"))
    )
    (comp (ref "J4")
      (value "DIN5")
      (footprint "eagle-import:DIN5-RA-PTH")
      (libsource (lib "eagle-import") (part "DIN5"))
    )
    (comp (ref "J5")
      (value "DIN5")
      (footprint "eagle-import:DIN5-RA-PTH")
      (libsource (lib "eagle-import") (part "DIN5"))
    )
    (comp (ref "J7")
      (value "SJ-3566AN")
      (footprint "eagle-import:CUI_SJ-3566AN")
      (fields (field (name "MF") "CUI Devices"))
      (libsource (lib "eagle-import") (part "SJ-3566AN"))
    )
    (comp (ref "OK1")
      (value "6N137S1")
      (footprint "eagle-import:SOP254P1030X390-8L")
      (libsource (lib "eagle-import") (part "6N137S1"))
    )
    (comp (ref "R53")
      (value "220")
      (footprint "eagle-import:R0603")
      (libsource (lib "eagle-import") (part "R-US_R0603"))
    )
    (comp (ref "R54")
      (value "220")
      (footprint "eagle-import:R0603")
      (libsource (lib "eagle-import") (part "R-US_R0603"))
    )
    (comp (ref "R55")
      (value "10k")
      (footprint "eagle-import:R0603")
      (libsource (lib "eagle-import") (part "R-US_R0603"))
    )
    (comp (ref "R56")
      (value "220")
      (footprint "eagle-import:R0603")
      (libsource (lib "eagle-import") (part "R-US_R0603"))
    )
    (comp (ref "R57")
      (value "15k")
      (footprint "eagle-import:R0603")
      (libsource (lib "eagle-import") (part "R-US_R0603"))
    )
    (comp (ref "R58")
      (value "15k")
      (footprint "eagle-import:R0603")
      (libsource (lib "eagle-import") (part "R-US_R0603"))
    )
    (comp (ref "R59")
      (value "820")
      (footprint "eagle-import:R0603")
      (libsource (lib "eagle-import") (part "R-US_R0603"))
    )
    (comp (ref "R60")
      (value "1M")
      (footprint "eagle-import:R0603")
      (libsource (lib "eagle-import") (part "R-US_R0603"))
    )
    (comp (ref "R61")
      (value "12k")
      (footprint "eagle-import:R0603")
      (libsource (lib "eagle-import") (part "R-US_R0603"))
    )
    (comp (ref "U18")
      (value "ECLAMP2398P.TCT")
      (footprint "eagle-import:SLP4014P16_SEM")
      (fields (field (name "COPYRIGHT") "Copyright (C) 2018 Accelerated Designs. All rights reserved"))
      (libsource (lib "eagle-import") (part "ECLAMP2398P.TCT"))
    )
    (comp (ref "U20")
      (value "USB3300-EZKQFN32_5X5MC_MCH-M")
      (footprint "eagle-import:QFN32_5X5MC_MCH-M")
      (fields
        (field (name "MANUFACTURER_PART_NUMBER") "USB3300-EZK")
        (field (name "COPYRIGHT") "Copyright (C) 2018 Accelerated Designs. All rights reserved")
      )
      (libsource (lib "eagle-import") (part "USB3300-EZKQFN32_5X5MC_MCH-M"))
    )
    (comp (ref "U21")
      (value "74AHC1G125DCK")
      (footprint "eagle-import:SC70-5")
      (libsource (lib "eagle-import") (part "741G125DCKAHC"))
    )
    (comp (ref "X1")
      (value "24MHz")
      (footprint "eagle-import:HC49_S")
      (libsource (lib "eagle-import") (part "CRYSTALHC49S"))
    )
    (comp (ref "C83")
      (value "33pF")
      (footprint "eagle-import:C0603")
      (libsource (lib "eagle-import") (part "C-EUC0603"))
    )
    (comp (ref "C88")
      (value "33pF")
      (footprint "eagle-import:C0603")
      (libsource (lib "eagle-import") (part "C-EUC0603"))
    )
    (comp (ref "U22")
      (value "STM32H7X3BITLQFP208_28X28X1P4-L")
      (footprint "eagle-import:LQFP208_28X28X1P4-L")
      (fields
        (field (name "MANUFACTURER_PART_NUMBER") "STM32H7X3BIT")
        (field (name "COPYRIGHT") "Copyright (C) 2016 Accelerated Designs. All rights reserved")
      )
      (libsource (lib "eagle-import") (part "STM32H7X3BITLQFP208_28X28X1P4-L"))
    )
    (comp (ref "X2")
      (value "24MHz")
      (footprint "eagle-import:HC49_S")
      (libsource (lib "eagle-import") (part "CRYSTALHC49S"))
    )
    (comp (ref "C39")
      (value "1uF")
      (footprint "eagle-import:C0805")
      (libsource (lib "eagle-import") (part "C-EUC0805"))
    )
    (comp (ref "C40")
      (value "1uF")
      (footprint "eagle-import:C0805")
      (libsource (lib "eagle-import") (part "C-EUC0805"))
    )
    (comp (ref "C41")
      (value "1uF")
      (footprint "eagle-import:C0805")
      (libsource (lib "eagle-import") (part "C-EUC0805"))
    )
    (comp (ref "D3")
      (value "ESDA25L")
      (footprint "eagle-import:SOT85P255X140-3L")
      (libsource (lib "eagle-import") (part "ESDAL"))
    )
    (comp (ref "D4")
      (value "ESDA25L")
      (footprint "eagle-import:SOT85P255X140-3L")
      (libsource (lib "eagle-import") (part "ESDAL"))
    )
    (comp (ref "D5")
      (value "ESDA25P35")
      (footprint "eagle-import:SOD123FL")
      (libsource (lib "eagle-import") (part "SMF5.0AT1"))
    )
    (comp (ref "J1")
      (value "105450-0101")
      (footprint "eagle-import:MOLEX_105450-0101")
      (fields
        (field (name "DIGI-KEY_PART_NUMBER") "WM12856CT-ND")
        (field (name "MF") "Molex")
        (field (name "MP") "1054500101")
      )
      (libsource (lib "eagle-import") (part "105450-0101"))
    )
    (comp (ref "Q6")
      (value "AO4407A")
      (footprint "eagle-import:SOIC8")
      (libsource (lib "eagle-import") (part "AO4407A"))
    )
    (comp (ref "R35")
      (value "1k")
      (footprint "eagle-import:R0402")
      (libsource (lib "eagle-import") (part "R-US_R0402"))
    )
    (comp (ref "R36")
      (value "100k")
      (footprint "eagle-import:R0402")
      (libsource (lib "eagle-import") (part "R-US_R0402"))
    )
    (comp (ref "R37")
      (value "20k")
      (footprint "eagle-import:R0402")
      (libsource (lib "eagle-import") (part "R-US_R0402"))
    )
    (comp (ref "R38")
      (value "1k")
      (footprint "eagle-import:R0402")
      (libsource (lib "eagle-import") (part "R-US_R0402"))
    )
    (comp (ref "R39")
      (value "10k")
      (footprint "eagle-import:R0402")
      (libsource (lib "eagle-import") (part "R-US_R0402"))
    )
    (comp (ref "R40")
      (value "10k")
      (footprint "eagle-import:R0402")
      (libsource (lib "eagle-import") (part "R-US_R0402"))
    )
    (comp (ref "TP4")
      (value "TEST-POINT3X4")
      (footprint "eagle-import:PAD.03X.04")
      (libsource (lib "eagle-import") (part "SparkFun-Connectors_513_TEST-POINT3X4"))
    )
    (comp (ref "U8")
      (value "STUSB4500L")
      (footprint "eagle-import:QFN24EP_4X4_STM-M")
      (fields
        (field (name "MANUFACTURER_PART_NUMBER") "STUSB4500QTR")
        (field (name "COPYRIGHT") "Copyright (C) 2018 Accelerated Designs. All rights reserved")
      )
      (libsource (lib "eagle-import") (part "STUSB4500QTRQFN24EP_4X4_STM-M"))
    )
    (comp (ref "U9")
      (value "TCA4311ADGKRDGK8-M")
      (footprint "eagle-import:DGK8-M")
      (fields
        (field (name "GENERIC_PART_NUMBER") "TCA4311A")
        (field (name "MANUFACTURER") "Texas Instruments")
        (field (name "MANUFACTURER_PART_NUMBER") "TCA4311ADGKR")
      )
      (libsource (lib "eagle-import") (part "TCA4311ADGKRDGK8-M"))
    )
    (comp (ref "C44")
      (value "100nF")
      (footprint "eagle-import:C0504")
      (libsource (lib "eagle-import") (part "C-EUC0504"))
    )
    (comp (ref "C45")
      (value "4.7uF")
      (footprint "eagle-import:C0504")
      (libsource (lib "eagle-import") (part "C-EUC0504"))
    )
    (comp (ref "C46")
      (value "4.7uF")
      (footprint "eagle-import:C0504")
      (libsource (lib "eagle-import") (part "C-EUC0504"))
    )
    (comp (ref "C47")
      (value "4.7uF")
      (footprint "eagle-import:C0504")
      (libsource (lib "eagle-import") (part "C-EUC0504"))
    )
    (comp (ref "C48")
      (value "10uF")
      (footprint "eagle-import:SMC_C")
      (libsource (lib "eagle-import") (part "CPOL-USSMCC"))
    )
    (comp (ref "C49")
      (value "1uF")
      (footprint "eagle-import:C0504")
      (libsource (lib "eagle-import") (part "C-EUC0504"))
    )
    (comp (ref "C50")
      (value "0.47uF")
      (footprint "eagle-import:C0504")
      (libsource (lib "eagle-import") (part "C-EUC0504"))
    )
    (comp (ref "C51")
      (value "0.47uF")
      (footprint "eagle-import:C0504")
      (libsource (lib "eagle-import") (part "C-EUC0504"))
    )
    (comp (ref "C52")
      (value "0.47uF")
      (footprint "eagle-import:C0504")
      (libsource (lib "eagle-import") (part "C-EUC0504"))
    )
    (comp (ref "C53")
      (value "0.47uF")
      (footprint "eagle-import:C0504")
      (libsource (lib "eagle-import") (part "C-EUC0504"))
    )
    (comp (ref "C54")
      (value "1uF")
      (footprint "eagle-import:C0504")
      (libsource (lib "eagle-import") (part "C-EUC0504"))
    )
    (comp (ref "C55")
      (value "1uF")
      (footprint "eagle-import:C0504")
      (libsource (lib "eagle-import") (part "C-EUC0504"))
    )
    (comp (ref "C56")
      (value "1uF")
      (footprint "eagle-import:C0504")
      (libsource (lib "eagle-import") (part "C-EUC0504"))
    )
    (comp (ref "C57")
      (value "1uF")
      (footprint "eagle-import:C0504")
      (libsource (lib "eagle-import") (part "C-EUC0504"))
    )
    (comp (ref "C58")
      (value "100nF")
      (footprint "eagle-import:C0504")
      (libsource (lib "eagle-import") (part "C-EUC0504"))
    )
    (comp (ref "C59")
      (value "180nF")
      (footprint "eagle-import:C0504")
      (libsource (lib "eagle-import") (part "C-EUC0504"))
    )
    (comp (ref "C60")
      (value "10uF")
      (footprint "eagle-import:SMC_C")
      (libsource (lib "eagle-import") (part "CPOL-USSMCC"))
    )
    (comp (ref "C61")
      (value "100nF")
      (footprint "eagle-import:C0504")
      (libsource (lib "eagle-import") (part "C-EUC0504"))
    )
    (comp (ref "C62")
      (value "1uF")
      (footprint "eagle-import:C0504")
      (libsource (lib "eagle-import") (part "C-EUC0504"))
    )
    (comp (ref "C63")
      (value "10uF")
      (footprint "eagle-import:SMC_C")
      (libsource (lib "eagle-import") (part "CPOL-USSMCC"))
    )
    (comp (ref "C64")
      (value "100nF")
      (footprint "eagle-import:C0504")
      (libsource (lib "eagle-import") (part "C-EUC0504"))
    )
    (comp (ref "C65")
      (value "1uF")
      (footprint "eagle-import:C0504")
      (libsource (lib "eagle-import") (part "C-EUC0504"))
    )
    (comp (ref "C66")
      (value "180nF")
      (footprint "eagle-import:C0504")
      (libsource (lib "eagle-import") (part "C-EUC0504"))
    )
    (comp (ref "R42")
      (value "10k")
      (footprint "eagle-import:R0603")
      (libsource (lib "eagle-import") (part "R-US_R0603"))
    )
    (comp (ref "R43")
      (value "10k")
      (footprint "eagle-import:R0603")
      (libsource (lib "eagle-import") (part "R-US_R0603"))
    )
    (comp (ref "R44")
      (value "470")
      (footprint "eagle-import:R0603")
      (libsource (lib "eagle-import") (part "R-US_R0603"))
    )
    (comp (ref "R45")
      (value "470")
      (footprint "eagle-import:R0603")
      (libsource (lib "eagle-import") (part "R-US_R0603"))
    )
    (comp (ref "R46")
      (value "10k")
      (footprint "eagle-import:R0603")
      (libsource (lib "eagle-import") (part "R-US_R0603"))
    )
    (comp (ref "R47")
      (value "10k")
      (footprint "eagle-import:R0603")
      (libsource (lib "eagle-import") (part "R-US_R0603"))
    )
    (comp (ref "R48")
      (value "22k")
      (footprint "eagle-import:R0603")
      (libsource (lib "eagle-import") (part "R-US_R0603"))
    )
    (comp (ref "R49")
      (value "27k")
      (footprint "eagle-import:R0603")
      (libsource (lib "eagle-import") (part "R-US_R0603"))
    )
    (comp (ref "R50")
      (value "22k")
      (footprint "eagle-import:R0603")
      (libsource (lib "eagle-import") (part "R-US_R0603"))
    )
    (comp (ref "R51")
      (value "27k")
      (footprint "eagle-import:R0603")
      (libsource (lib "eagle-import") (part "R-US_R0603"))
    )
    (comp (ref "TP8")
      (value "TEST-POINT3X4")
      (footprint "eagle-import:PAD.03X.04")
      (libsource (lib "eagle-import") (part "TEST-POINT3X4"))
    )
    (comp (ref "TP9")
      (value "TEST-POINT3X4")
      (footprint "eagle-import:PAD.03X.04")
      (libsource (lib "eagle-import") (part "TEST-POINT3X4"))
    )
    (comp (ref "TP10")
      (value "TEST-POINT3X4")
      (footprint "eagle-import:PAD.03X.04")
      (libsource (lib "eagle-import") (part "TEST-POINT3X4"))
    )
    (comp (ref "TP11")
      (value "TEST-POINT3X4")
      (footprint "eagle-import:PAD.03X.04")
      (libsource (lib "eagle-import") (part "TEST-POINT3X4"))
    )
    (comp (ref "TP12")
      (value "TEST-POINT3X4")
      (footprint "eagle-import:PAD.03X.04")
      (libsource (lib "eagle-import") (part "TEST-POINT3X4"))
    )
    (comp (ref "TP13")
      (value "TEST-POINT3X4")
      (footprint "eagle-import:PAD.03X.04")
      (libsource (lib "eagle-import") (part "TEST-POINT3X4"))
    )
    (comp (ref "U11")
      (value "AD5242BRUZ10RU_16_ADI-M")
      (footprint "eagle-import:RU_16_ADI-M")
      (fields (field (name "MANUFACTURER_PART_NUMBER") "AD5242BRUZ10"))
      (libsource (lib "eagle-import") (part "AD5242BRUZ10RU_16_ADI-M"))
    )
    (comp (ref "U12")
      (value "TPA4861DRD8_TEX-M")
      (footprint "eagle-import:D8_TEX-M")
      (fields
        (field (name "MANUFACTURER") "Texas Instruments")
        (field (name "MANUFACTURER_PART_NUMBER") "TPA4861DR")
      )
      (libsource (lib "eagle-import") (part "TPA4861DRD8_TEX-M"))
    )
    (comp (ref "U13")
      (value "TPA4861DRD8_TEX-M")
      (footprint "eagle-import:D8_TEX-M")
      (fields
        (field (name "MANUFACTURER") "Texas Instruments")
        (field (name "MANUFACTURER_PART_NUMBER") "TPA4861DR")
      )
      (libsource (lib "eagle-import") (part "TPA4861DRD8_TEX-M"))
    )
    (comp (ref "U14")
      (value "TPA6130A2RTJR")
      (footprint "eagle-import:RTJ20_2P7X2P7")
      (fields (field (name "MANUFACTURER") "Texas Instruments"))
      (libsource (lib "eagle-import") (part "TPA6130A2RTJR"))
    )
    (comp (ref "U15")
      (value "CS4344-CZZR")
      (footprint "eagle-import:CIR_3TSSOP-10")
      (libsource (lib "eagle-import") (part "CS4344-CZZR"))
    )
    (comp (ref "C116")
      (value "100nF")
      (footprint "eagle-import:C0603")
      (libsource (lib "eagle-import") (part "C-EUC0603"))
    )
    (comp (ref "D6")
      (value "1N4148W")
      (footprint "eagle-import:SOD123")
      (libsource (lib "eagle-import") (part "1N4148W"))
    )
    (comp (ref "D7")
      (value "1N4148W")
      (footprint "eagle-import:SOD123")
      (libsource (lib "eagle-import") (part "1N4148W"))
    )
    (comp (ref "D8")
      (value "1N4148W")
      (footprint "eagle-import:SOD123")
      (libsource (lib "eagle-import") (part "1N4148W"))
    )
    (comp (ref "D9")
      (value "1N4148W")
      (footprint "eagle-import:SOD123")
      (libsource (lib "eagle-import") (part "1N4148W"))
    )
    (comp (ref "D10")
      (value "1N4148W")
      (footprint "eagle-import:SOD123")
      (libsource (lib "eagle-import") (part "1N4148W"))
    )
    (comp (ref "LED1")
      (value "19-217/BHC-ZL1M2RY/3T")
      (footprint "eagle-import:CHIPLED_0603")
      (libsource (lib "eagle-import") (part "LEDCHIPLED_0603"))
    )
    (comp (ref "LED2")
      (value "19-217/BHC-ZL1M2RY/3T")
      (footprint "eagle-import:CHIPLED_0603")
      (libsource (lib "eagle-import") (part "LEDCHIPLED_0603"))
    )
    (comp (ref "LED3")
      (value "19-217/BHC-ZL1M2RY/3T")
      (footprint "eagle-import:CHIPLED_0603")
      (libsource (lib "eagle-import") (part "LEDCHIPLED_0603"))
    )
    (comp (ref "LED4")
      (value "19-217/BHC-ZL1M2RY/3T")
      (footprint "eagle-import:CHIPLED_0603")
      (libsource (lib "eagle-import") (part "LEDCHIPLED_0603"))
    )
    (comp (ref "LED5")
      (value "19-217/BHC-ZL1M2RY/3T")
      (footprint "eagle-import:CHIPLED_0603")
      (libsource (lib "eagle-import") (part "LEDCHIPLED_0603"))
    )
    (comp (ref "LED6")
      (value "19-217/BHC-ZL1M2RY/3T")
      (footprint "eagle-import:CHIPLED_0603")
      (libsource (lib "eagle-import") (part "LEDCHIPLED_0603"))
    )
    (comp (ref "LED7")
      (value "19-217/BHC-ZL1M2RY/3T")
      (footprint "eagle-import:CHIPLED_0603")
      (libsource (lib "eagle-import") (part "LEDCHIPLED_0603"))
    )
    (comp (ref "R65")
      (value "10k")
      (footprint "eagle-import:R0603")
      (libsource (lib "eagle-import") (part "R-US_R0603"))
    )
    (comp (ref "R66")
      (value "10k")
      (footprint "eagle-import:R0603")
      (libsource (lib "eagle-import") (part "R-US_R0603"))
    )
    (comp (ref "R67")
      (value "10k")
      (footprint "eagle-import:R0603")
      (libsource (lib "eagle-import") (part "R-US_R0603"))
    )
    (comp (ref "R68")
      (value "10k")
      (footprint "eagle-import:R0603")
      (libsource (lib "eagle-import") (part "R-US_R0603"))
    )
    (comp (ref "R69")
      (value "10k")
      (footprint "eagle-import:R0603")
      (libsource (lib "eagle-import") (part "R-US_R0603"))
    )
    (comp (ref "R70")
      (value "120")
      (footprint "eagle-import:R0603")
      (libsource (lib "eagle-import") (part "R-US_R0603"))
    )
    (comp (ref "R71")
      (value "120")
      (footprint "eagle-import:R0603")
      (libsource (lib "eagle-import") (part "R-US_R0603"))
    )
    (comp (ref "R72")
      (value "120")
      (footprint "eagle-import:R0603")
      (libsource (lib "eagle-import") (part "R-US_R0603"))
    )
    (comp (ref "R73")
      (value "120")
      (footprint "eagle-import:R0603")
      (libsource (lib "eagle-import") (part "R-US_R0603"))
    )
    (comp (ref "R74")
      (value "120")
      (footprint "eagle-import:R0603")
      (libsource (lib "eagle-import") (part "R-US_R0603"))
    )
    (comp (ref "R75")
      (value "120")
      (footprint "eagle-import:R0603")
      (libsource (lib "eagle-import") (part "R-US_R0603"))
    )
    (comp (ref "R76")
      (value "120")
      (footprint "eagle-import:R0603")
      (libsource (lib "eagle-import") (part "R-US_R0603"))
    )
    (comp (ref "R77")
      (value "10k")
      (footprint "eagle-import:R0603")
      (libsource (lib "eagle-import") (part "R-US_R0603"))
    )
    (comp (ref "S2")
      (value "B3F-1052")
      (footprint "eagle-import:TACTILE_SWITCH_PTH_6.0MM")
      (libsource (lib "eagle-import") (part "B3F-1052"))
    )
    (comp (ref "S3")
      (value "B3F-1052")
      (footprint "eagle-import:TACTILE_SWITCH_PTH_6.0MM")
      (libsource (lib "eagle-import") (part "B3F-1052"))
    )
    (comp (ref "S4")
      (value "B3F-1052")
      (footprint "eagle-import:TACTILE_SWITCH_PTH_6.0MM")
      (libsource (lib "eagle-import") (part "B3F-1052"))
    )
    (comp (ref "S5")
      (value "B3F-1052")
      (footprint "eagle-import:TACTILE_SWITCH_PTH_6.0MM")
      (libsource (lib "eagle-import") (part "B3F-1052"))
    )
    (comp (ref "S6")
      (value "B3F-1052")
      (footprint "eagle-import:TACTILE_SWITCH_PTH_6.0MM")
      (libsource (lib "eagle-import") (part "B3F-1052"))
    )
    (comp (ref "S7")
      (value "B3F-1052")
      (footprint "eagle-import:TACTILE_SWITCH_PTH_6.0MM")
      (libsource (lib "eagle-import") (part "B3F-1052"))
    )
    (comp (ref "S8")
      (value "B3F-1052")
      (footprint "eagle-import:TACTILE_SWITCH_PTH_6.0MM")
      (libsource (lib "eagle-import") (part "B3F-1052"))
    )
    (comp (ref "S9")
      (value "B3F-1052")
      (footprint "eagle-import:TACTILE_SWITCH_PTH_6.0MM")
      (libsource (lib "eagle-import") (part "B3F-1052"))
    )
    (comp (ref "S10")
      (value "B3F-1052")
      (footprint "eagle-import:TACTILE_SWITCH_PTH_6.0MM")
      (libsource (lib "eagle-import") (part "B3F-1052"))
    )
    (comp (ref "S11")
      (value "B3F-1052")
      (footprint "eagle-import:TACTILE_SWITCH_PTH_6.0MM")
      (libsource (lib "eagle-import") (part "B3F-1052"))
    )
    (comp (ref "S12")
      (value "B3F-1052")
      (footprint "eagle-import:TACTILE_SWITCH_PTH_6.0MM")
      (libsource (lib "eagle-import") (part "B3F-1052"))
    )
    (comp (ref "S13")
      (value "B3F-1052")
      (footprint "eagle-import:TACTILE_SWITCH_PTH_6.0MM")
      (libsource (lib "eagle-import") (part "B3F-1052"))
    )
    (comp (ref "S14")
      (value "B3F-1052")
      (footprint "eagle-import:TACTILE_SWITCH_PTH_6.0MM")
      (libsource (lib "eagle-import") (part "B3F-1052"))
    )
    (comp (ref "S15")
      (value "B3F-1052")
      (footprint "eagle-import:TACTILE_SWITCH_PTH_6.0MM")
      (libsource (lib "eagle-import") (part "B3F-1052"))
    )
    (comp (ref "S16")
      (value "B3F-1052")
      (footprint "eagle-import:TACTILE_SWITCH_PTH_6.0MM")
      (libsource (lib "eagle-import") (part "B3F-1052"))
    )
    (comp (ref "S17")
      (value "B3F-1052")
      (footprint "eagle-import:TACTILE_SWITCH_PTH_6.0MM")
      (libsource (lib "eagle-import") (part "B3F-1052"))
    )
    (comp (ref "S18")
      (value "B3F-1052")
      (footprint "eagle-import:TACTILE_SWITCH_PTH_6.0MM")
      (libsource (lib "eagle-import") (part "B3F-1052"))
    )
    (comp (ref "S19")
      (value "B3F-1052")
      (footprint "eagle-import:TACTILE_SWITCH_PTH_6.0MM")
      (libsource (lib "eagle-import") (part "B3F-1052"))
    )
    (comp (ref "S20")
      (value "B3F-1052")
      (footprint "eagle-import:TACTILE_SWITCH_PTH_6.0MM")
      (libsource (lib "eagle-import") (part "B3F-1052"))
    )
    (comp (ref "S21")
      (value "B3F-1052")
      (footprint "eagle-import:TACTILE_SWITCH_PTH_6.0MM")
      (libsource (lib "eagle-import") (part "B3F-1052"))
    )
    (comp (ref "S22")
      (value "B3F-1052")
      (footprint "eagle-import:TACTILE_SWITCH_PTH_6.0MM")
      (libsource (lib "eagle-import") (part "B3F-1052"))
    )
    (comp (ref "S23")
      (value "B3F-1052")
      (footprint "eagle-import:TACTILE_SWITCH_PTH_6.0MM")
      (libsource (lib "eagle-import") (part "B3F-1052"))
    )
    (comp (ref "S24")
      (value "B3F-1052")
      (footprint "eagle-import:TACTILE_SWITCH_PTH_6.0MM")
      (libsource (lib "eagle-import") (part "B3F-1052"))
    )
    (comp (ref "S25")
      (value "B3F-1052")
      (footprint "eagle-import:TACTILE_SWITCH_PTH_6.0MM")
      (libsource (lib "eagle-import") (part "B3F-1052"))
    )
    (comp (ref "VR1")
      (value "RK09D1130C2P")
      (footprint "eagle-import:RK09D1130C3C")
      (fields
        (field (name "MOUSER_PART_NUMBER") "688-RK09D1130C2P")
        (field (name "RS_PART_NUMBER") "1726272")
      )
      (libsource (lib "eagle-import") (part "RK09D1130C2P"))
    )
    (comp (ref "VR2")
      (value "RK09D1130C2P")
      (footprint "eagle-import:RK09D1130C3C")
      (fields
        (field (name "MOUSER_PART_NUMBER") "688-RK09D1130C2P")
        (field (name "RS_PART_NUMBER") "1726272")
      )
      (libsource (lib "eagle-import") (part "RK09D1130C2P"))
    )
    (comp (ref "VR3")
      (value "RS301111J00R")
      (footprint "eagle-import:RS301111J00R")
      (fields (field (name "LCSC_PART_NUMBER") "C361172"))
      (libsource (lib "eagle-import") (part "RS301111J00R"))
    )
    (comp (ref "VR4")
      (value "RK09D1130C2P")
      (footprint "eagle-import:RK09D1130C3C")
      (fields
        (field (name "MOUSER_PART_NUMBER") "688-RK09D1130C2P")
        (field (name "RS_PART_NUMBER") "1726272")
      )
      (libsource (lib "eagle-import") (part "RK09D1130C2P"))
    )
    (comp (ref "C89")
      (value "100nF")
      (footprint "eagle-import:C0603")
      (libsource (lib "eagle-import") (part "C-EUC0603"))
    )
    (comp (ref "C90")
      (value "1uF")
      (footprint "eagle-import:C0603")
      (libsource (lib "eagle-import") (part "C-EUC0603"))
    )
    (comp (ref "C91")
      (value "1uF")
      (footprint "eagle-import:C0603")
      (libsource (lib "eagle-import") (part "C-EUC0603"))
    )
    (comp (ref "C92")
      (value "100nF")
      (footprint "eagle-import:C0603")
      (libsource (lib "eagle-import") (part "C-EUC0603"))
    )
    (comp (ref "C93")
      (value "100nF")
      (footprint "eagle-import:C0603")
      (libsource (lib "eagle-import") (part "C-EUC0603"))
    )
    (comp (ref "C94")
      (value "100nF")
      (footprint "eagle-import:C0603")
      (libsource (lib "eagle-import") (part "C-EUC0603"))
    )
    (comp (ref "C95")
      (value "100nF")
      (footprint "eagle-import:C0603")
      (libsource (lib "eagle-import") (part "C-EUC0603"))
    )
    (comp (ref "C96")
      (value "100nF")
      (footprint "eagle-import:C0603")
      (libsource (lib "eagle-import") (part "C-EUC0603"))
    )
    (comp (ref "C97")
      (value "100nF")
      (footprint "eagle-import:C0603")
      (libsource (lib "eagle-import") (part "C-EUC0603"))
    )
    (comp (ref "C98")
      (value "100nF")
      (footprint "eagle-import:C0603")
      (libsource (lib "eagle-import") (part "C-EUC0603"))
    )
    (comp (ref "C99")
      (value "100nF")
      (footprint "eagle-import:C0603")
      (libsource (lib "eagle-import") (part "C-EUC0603"))
    )
    (comp (ref "C100")
      (value "100nF")
      (footprint "eagle-import:C0603")
      (libsource (lib "eagle-import") (part "C-EUC0603"))
    )
    (comp (ref "C101")
      (value "100nF")
      (footprint "eagle-import:C0603")
      (libsource (lib "eagle-import") (part "C-EUC0603"))
    )
    (comp (ref "C102")
      (value "100nF")
      (footprint "eagle-import:C0603")
      (libsource (lib "eagle-import") (part "C-EUC0603"))
    )
    (comp (ref "C103")
      (value "100nF")
      (footprint "eagle-import:C0603")
      (libsource (lib "eagle-import") (part "C-EUC0603"))
    )
    (comp (ref "C104")
      (value "100nF")
      (footprint "eagle-import:C0603")
      (libsource (lib "eagle-import") (part "C-EUC0603"))
    )
    (comp (ref "C105")
      (value "100nF")
      (footprint "eagle-import:C0603")
      (libsource (lib "eagle-import") (part "C-EUC0603"))
    )
    (comp (ref "C106")
      (value "100nF")
      (footprint "eagle-import:C0603")
      (libsource (lib "eagle-import") (part "C-EUC0603"))
    )
    (comp (ref "C107")
      (value "100nF")
      (footprint "eagle-import:C0603")
      (libsource (lib "eagle-import") (part "C-EUC0603"))
    )
    (comp (ref "C108")
      (value "4.7uF")
      (footprint "eagle-import:C0603")
      (libsource (lib "eagle-import") (part "C-EUC0603"))
    )
    (comp (ref "C109")
      (value "100nF")
      (footprint "eagle-import:C0603")
      (libsource (lib "eagle-import") (part "C-EUC0603"))
    )
    (comp (ref "C110")
      (value "2.2uF")
      (footprint "eagle-import:C0603")
      (libsource (lib "eagle-import") (part "C-EUC0603"))
    )
    (comp (ref "C111")
      (value "2.2uF")
      (footprint "eagle-import:C0603")
      (libsource (lib "eagle-import") (part "C-EUC0603"))
    )
    (comp (ref "C112")
      (value "100nF")
      (footprint "eagle-import:C0603")
      (libsource (lib "eagle-import") (part "C-EUC0603"))
    )
    (comp (ref "C113")
      (value "1uF")
      (footprint "eagle-import:C0603")
      (libsource (lib "eagle-import") (part "C-EUC0603"))
    )
    (comp (ref "L4")
      (value "FCM1608KF-601T3")
      (footprint "eagle-import:INDC1608X95N")
      (fields (field (name "MPN") "FCM1608KF-601T3"))
      (libsource (lib "eagle-import") (part "LCHIP-0603(1608-METRIC)_"))
    )
    (comp (ref "C24")
      (value "1uF")
      (footprint "eagle-import:C0402")
      (libsource (lib "eagle-import") (part "C-EUC0402"))
    )
    (comp (ref "C25")
      (value "2.2uF")
      (footprint "eagle-import:C0402")
      (libsource (lib "eagle-import") (part "C-EUC0402"))
    )
    (comp (ref "C31")
      (value "22uF")
      (footprint "eagle-import:C0402")
      (libsource (lib "eagle-import") (part "C-EUC0402"))
    )
    (comp (ref "C32")
      (value "22uF")
      (footprint "eagle-import:C0402")
      (libsource (lib "eagle-import") (part "C-EUC0402"))
    )
    (comp (ref "C33")
      (value "22uF")
      (footprint "eagle-import:C0402")
      (libsource (lib "eagle-import") (part "C-EUC0402"))
    )
    (comp (ref "C34")
      (value "22uF")
      (footprint "eagle-import:C0402")
      (libsource (lib "eagle-import") (part "C-EUC0402"))
    )
    (comp (ref "C35")
      (value "22uF")
      (footprint "eagle-import:C0402")
      (libsource (lib "eagle-import") (part "C-EUC0402"))
    )
    (comp (ref "C36")
      (value "22uF")
      (footprint "eagle-import:C0402")
      (libsource (lib "eagle-import") (part "C-EUC0402"))
    )
    (comp (ref "C37")
      (value "4.7uF")
      (footprint "eagle-import:C0402")
      (libsource (lib "eagle-import") (part "C-EUC0402"))
    )
    (comp (ref "C38")
      (value "4.7uF")
      (footprint "eagle-import:C0402")
      (libsource (lib "eagle-import") (part "C-EUC0402"))
    )
    (comp (ref "C42")
      (value "1uF")
      (footprint "eagle-import:C0402")
      (libsource (lib "eagle-import") (part "C-EUC0402"))
    )
    (comp (ref "C43")
      (value "100nF")
      (footprint "eagle-import:C0402")
      (libsource (lib "eagle-import") (part "C-EUC0402"))
    )
    (comp (ref "L2")
      (value "2.2uH")
      (footprint "eagle-import:INDM4030X267")
      (fields (field (name "MPN") "SPM4030T-2R2M"))
      (libsource (lib "eagle-import") (part "LMOLDED-1612(4030-METRIC)_"))
    )
    (comp (ref "L3")
      (value "2.2uH")
      (footprint "eagle-import:INDM4030X267")
      (fields (field (name "MPN") "SPM4030T-2R2M"))
      (libsource (lib "eagle-import") (part "LMOLDED-1612(4030-METRIC)_"))
    )
    (comp (ref "R25")
      (value "750k")
      (footprint "eagle-import:R0805")
      (libsource (lib "eagle-import") (part "R-US_R0805"))
    )
    (comp (ref "R26")
      (value "100k")
      (footprint "eagle-import:R0805")
      (libsource (lib "eagle-import") (part "R-US_R0805"))
    )
    (comp (ref "R27")
      (value "750k")
      (footprint "eagle-import:R0805")
      (libsource (lib "eagle-import") (part "R-US_R0805"))
    )
    (comp (ref "R28")
      (value "100k")
      (footprint "eagle-import:R0805")
      (libsource (lib "eagle-import") (part "R-US_R0805"))
    )
    (comp (ref "R29")
      (value "750k")
      (footprint "eagle-import:R0805")
      (libsource (lib "eagle-import") (part "R-US_R0805"))
    )
    (comp (ref "R31")
      (value "10k")
      (footprint "eagle-import:R0805")
      (libsource (lib "eagle-import") (part "R-US_R0805"))
    )
    (comp (ref "R32")
      (value "10k")
      (footprint "eagle-import:R0805")
      (libsource (lib "eagle-import") (part "R-US_R0805"))
    )
    (comp (ref "R33")
      (value "10k")
      (footprint "eagle-import:R0805")
      (libsource (lib "eagle-import") (part "R-US_R0805"))
    )
    (comp (ref "R34")
      (value "10k")
      (footprint "eagle-import:R0805")
      (libsource (lib "eagle-import") (part "R-US_R0805"))
    )
    (comp (ref "R41")
      (value "10k")
      (footprint "eagle-import:R0805")
      (libsource (lib "eagle-import") (part "R-US_R0805"))
    )
    (comp (ref "SUPPLY1")
      (value "2PT_GND_TIE")
      (footprint "eagle-import:2PT_GND_TIE")
      (libsource (lib "eagle-import") (part "2PT_GND_TIE"))
    )
    (comp (ref "TP5")
      (value "TEST-POINT3X4")
      (footprint "eagle-import:PAD.03X.04")
      (libsource (lib "eagle-import") (part "SparkFun-Connectors_513_TEST-POINT3X4"))
    )
    (comp (ref "TP6")
      (value "TEST-POINT3X4")
      (footprint "eagle-import:PAD.03X.04")
      (libsource (lib "eagle-import") (part "SparkFun-Connectors_513_TEST-POINT3X4"))
    )
    (comp (ref "U2")
      (value "LD39150DT33-R")
      (footprint "eagle-import:SOT_0DT33-R_STM")
      (libsource (lib "eagle-import") (part "LD39150DT33-R"))
    )
    (comp (ref "U4")
      (value "PAM2401SCADJ")
      (footprint "eagle-import:MSOP8_DIO")
      (libsource (lib "eagle-import") (part "PAM2401SCADJ"))
    )
    (comp (ref "U5")
      (value "PAM2401SCADJ")
      (footprint "eagle-import:MSOP8_DIO")
      (libsource (lib "eagle-import") (part "PAM2401SCADJ"))
    )
    (comp (ref "U6")
      (value "STMPS2151STR")
      (footprint "eagle-import:SOT23-5L")
      (libsource (lib "eagle-import") (part "STMPS2151STR"))
    )
    (comp (ref "U7")
      (value "STMPS2151STR")
      (footprint "eagle-import:SOT23-5L")
      (libsource (lib "eagle-import") (part "STMPS2151STR"))
    )
    (comp (ref "U10")
      (value "TPS22929DDBVR")
      (footprint "eagle-import:DBV6")
      (fields
        (field (name "GENERIC_PART_NUMBER") "TPS22929D")
        (field (name "MANUFACTURER") "Texas Instruments")
      )
      (libsource (lib "eagle-import") (part "TPS22929DDBVR"))
    )
    (comp (ref "C114")
      (value "100nF")
      (footprint "eagle-import:C0603")
      (libsource (lib "eagle-import") (part "C-EUC0603"))
    )
    (comp (ref "C115")
      (value "100nF")
      (footprint "eagle-import:C0603")
      (libsource (lib "eagle-import") (part "C-EUC0603"))
    )
    (comp (ref "J8")
      (value "CONN_025MM")
      (footprint "eagle-import:SCREWTERMINAL-5MM-2")
      (libsource (lib "eagle-import") (part "CONN_025MM"))
    )
    (comp (ref "J9")
      (value "CONN_025MM")
      (footprint "eagle-import:SCREWTERMINAL-5MM-2")
      (libsource (lib "eagle-import") (part "CONN_025MM"))
    )
    (comp (ref "JP1")
      (value "PINHD-2X20")
      (footprint "eagle-import:2X20")
      (libsource (lib "eagle-import") (part "PINHD-2X20"))
    )
    (comp (ref "JP2")
      (value "PINHD-1X4")
      (footprint "eagle-import:1X04")
      (libsource (lib "eagle-import") (part "PINHD-1X4"))
    )
    (comp (ref "JP3")
      (value "PINHD-1X4")
      (footprint "eagle-import:1X04")
      (libsource (lib "eagle-import") (part "PINHD-1X4"))
    )
    (comp (ref "R63")
      (value "10k")
      (footprint "eagle-import:R0603")
      (libsource (lib "eagle-import") (part "R-US_R0603"))
    )
    (comp (ref "R64")
      (value "10k")
      (footprint "eagle-import:R0603")
      (libsource (lib "eagle-import") (part "R-US_R0603"))
    )
    (comp (ref "S1")
      (value "10-XX")
      (footprint "eagle-import:B3F-10XX")
      (fields (field (name "MPN") "B3F-1000"))
      (libsource (lib "eagle-import") (part "10-XX"))
    )
    (comp (ref "C67")
      (value "100nF")
      (footprint "eagle-import:C0402")
      (libsource (lib "eagle-import") (part "C-EUC0402"))
    )
    (comp (ref "C68")
      (value "22nF")
      (footprint "eagle-import:C0402")
      (libsource (lib "eagle-import") (part "C-EUC0402"))
    )
    (comp (ref "C69")
      (value "100nF")
      (footprint "eagle-import:C0402")
      (libsource (lib "eagle-import") (part "C-EUC0402"))
    )
    (comp (ref "C70")
      (value "10uF")
      (footprint "eagle-import:SMC_B")
      (libsource (lib "eagle-import") (part "CPOL-USSMCB"))
    )
    (comp (ref "C71")
      (value "22nF")
      (footprint "eagle-import:C0402")
      (libsource (lib "eagle-import") (part "C-EUC0402"))
    )
    (comp (ref "C72")
      (value "22nF")
      (footprint "eagle-import:C0402")
      (libsource (lib "eagle-import") (part "C-EUC0402"))
    )
    (comp (ref "C73")
      (value "22nF")
      (footprint "eagle-import:C0402")
      (libsource (lib "eagle-import") (part "C-EUC0402"))
    )
    (comp (ref "C74")
      (value "22nF")
      (footprint "eagle-import:C0402")
      (libsource (lib "eagle-import") (part "C-EUC0402"))
    )
    (comp (ref "C75")
      (value "22nF")
      (footprint "eagle-import:C0402")
      (libsource (lib "eagle-import") (part "C-EUC0402"))
    )
    (comp (ref "C76")
      (value "22nF")
      (footprint "eagle-import:C0402")
      (libsource (lib "eagle-import") (part "C-EUC0402"))
    )
    (comp (ref "C77")
      (value "100nF")
      (footprint "eagle-import:C0402")
      (libsource (lib "eagle-import") (part "C-EUC0402"))
    )
    (comp (ref "R30")
      (value "10k")
      (footprint "eagle-import:R0402")
      (libsource (lib "eagle-import") (part "R-US_R0402"))
    )
    (comp (ref "R52")
      (value "10k")
      (footprint "eagle-import:R0402")
      (libsource (lib "eagle-import") (part "R-US_R0402"))
    )
    (comp (ref "U16")
      (value "M24C32-WMN6TP")
      (footprint "eagle-import:SOIC127P600X175-8N")
      (libsource (lib "eagle-import") (part "M24C32-WMN6TP"))
    )
    (comp (ref "U17")
      (value "W25N01GVZEIGWSON-8_6X5_WIN-M")
      (footprint "eagle-import:WSON-8_6X5_WIN-M")
      (fields
        (field (name "MANUFACTURER_PART_NUMBER") "W25N01GVZEIG")
        (field (name "COPYRIGHT") "Copyright (C) 2018 Accelerated Designs. All rights reserved")
      )
      (libsource (lib "eagle-import") (part "W25N01GVZEIGWSON-8_6X5_WIN-M"))
    )
    (comp (ref "U19")
      (value "MT48LC16M16A2P")
      (footprint "eagle-import:SOP80P1176X120-54N")
      (libsource (lib "eagle-import") (part "MT48LC16M16A2P"))
    )
  )
  (nets
    (net (code "1") (name "+5V") (class "Default")
      (node (ref "C115") (pin "1") (pinfunction "1_1") (pintype "passive"))
      (node (ref "C32") (pin "1") (pinfunction "1_1") (pintype "passive"))
      (node (ref "C33") (pin "1") (pinfunction "1_1") (pintype "passive"))
      (node (ref "C78") (pin "1") (pinfunction "1_1") (pintype "passive"))
      (node (ref "JP1") (pin "2") (pinfunction "2_2") (pintype "passive"))
      (node (ref "OK1") (pin "7") (pinfunction "VE_7") (pintype "passive"))
      (node (ref "OK1") (pin "8") (pinfunction "VCC_8") (pintype "passive"))
      (node (ref "R25") (pin "2") (pinfunction "2_2") (pintype "passive"))
      (node (ref "TP5") (pin "P$1") (pinfunction "1_P$1") (pintype "bidirectional"))
      (node (ref "U4") (pin "7") (pinfunction "OUT_7") (pintype "output"))
      (node (ref "U6") (pin "5") (pinfunction "IN_5") (pintype "power_in"))
    )
    (net (code "2") (name "AGND") (class "Default")
      (node (ref "C44") (pin "2") (pinfunction "2_2") (pintype "passive"))
      (node (ref "C47") (pin "1") (pinfunction "1_1") (pintype "passive"))
      (node (ref "C48") (pin "-") (pinfunction "-_-") (pintype "passive"))
      (node (ref "C49") (pin "2") (pinfunction "2_2") (pintype "passive"))
      (node (ref "C52") (pin "1") (pinfunction "1_1") (pintype "passive"))
      (node (ref "C53") (pin "1") (pinfunction "1_1") (pintype "passive"))
      (node (ref "C54") (pin "2") (pinfunction "2_2") (pintype "passive"))
      (node (ref "C55") (pin "2") (pinfunction "2_2") (pintype "passive"))
      (node (ref "C57") (pin "2") (pinfunction "2_2") (pintype "passive"))
      (node (ref "C58") (pin "2") (pinfunction "2_2") (pintype "passive"))
      (node (ref "C60") (pin "-") (pinfunction "-_-") (pintype "passive"))
      (node (ref "C61") (pin "2") (pinfunction "2_2") (pintype "passive"))
      (node (ref "C62") (pin "2") (pinfunction "2_2") (pintype "passive"))
      (node (ref "C63") (pin "-") (pinfunction "-_-") (pintype "passive"))
      (node (ref "C64") (pin "2") (pinfunction "2_2") (pintype "passive"))
      (node (ref "C65") (pin "2") (pinfunction "2_2") (pintype "passive"))
      (node (ref "R42") (pin "1") (pinfunction "1_1") (pintype "passive"))
      (node (ref "R43") (pin "1") (pinfunction "1_1") (pintype "passive"))
      (node (ref "SUPPLY1") (pin "P$2") (pinfunction "P$2_P$2") (pintype "bidirectional"))
      (node (ref "U11") (pin "10") (pinfunction "AD1_10") (pintype "passive"))
      (node (ref "U11") (pin "11") (pinfunction "DGND_11") (pintype "passive"))
      (node (ref "U11") (pin "12") (pinfunction "VSS_12") (pintype "power_in"))
      (node (ref "U11") (pin "14") (pinfunction "B2_14") (pintype "passive"))
      (node (ref "U11") (pin "4") (pinfunction "B1_4") (pintype "passive"))
      (node (ref "U11") (pin "9") (pinfunction "AD0_9") (pintype "passive"))
      (node (ref "U12") (pin "7") (pinfunction "GND_7") (pintype "power_in"))
      (node (ref "U13") (pin "7") (pinfunction "GND_7") (pintype "power_in"))
      (node (ref "U14") (pin "10") (pinfunction "GND_4_10") (pintype "power_in"))
      (node (ref "U14") (pin "13") (pinfunction "GND_5_13") (pintype "power_in"))
      (node (ref "U14") (pin "19") (pinfunction "GND_19") (pintype "power_in"))
      (node (ref "U14") (pin "21") (pinfunction "EPAD_21") (pintype "passive"))
      (node (ref "U14") (pin "3") (pinfunction "GND_2_3") (pintype "power_in"))
      (node (ref "U14") (pin "9") (pinfunction "GND_3_9") (pintype "power_in"))
      (node (ref "U15") (pin "8") (pinfunction "GND_8") (pintype "power_in"))
    )
    (net (code "3") (name "AUDBUS_SCL") (class "Default")
      (node (ref "R47") (pin "2") (pinfunction "2_2") (pintype "passive"))
      (node (ref "U11") (pin "7") (pinfunction "SCL_7") (pintype "passive"))
      (node (ref "U14") (pin "8") (pinfunction "SCL_8") (pintype "input"))
      (node (ref "U22") (pin "97") (pinfunction "PH7_97") (pintype "bidirectional"))
    )
    (net (code "4") (name "AUDBUS_SDA") (class "Default")
      (node (ref "R46") (pin "2") (pinfunction "2_2") (pintype "passive"))
      (node (ref "U11") (pin "8") (pinfunction "SDA_8") (pintype "passive"))
      (node (ref "U14") (pin "7") (pinfunction "SDA_7") (pintype "bidirectional"))
      (node (ref "U22") (pin "98") (pinfunction "PH8_98") (pintype "bidirectional"))
    )
    (net (code "5") (name "BAT_TS") (class "Default")
      (node (ref "J6") (pin "2") (pinfunction "S_2") (pintype "passive"))
      (node (ref "R20") (pin "2") (pinfunction "2_2") (pintype "passive"))
      (node (ref "R21") (pin "2") (pinfunction "2_2") (pintype "passive"))
      (node (ref "TP3") (pin "P$1") (pinfunction "1_P$1") (pintype "bidirectional"))
    )
    (net (code "6") (name "BL_PWM") (class "Default")
      (node (ref "JP1") (pin "7") (pinfunction "7_7") (pintype "passive"))
      (node (ref "R63") (pin "2") (pinfunction "2_2") (pintype "passive"))
      (node (ref "U22") (pin "44") (pinfunction "PA1_44") (pintype "bidirectional"))
    )
    (net (code "7") (name "BUTMAT_IN0") (class "Default")
      (node (ref "D6") (pin "A") (pinfunction "A_A") (pintype "passive"))
      (node (ref "U22") (pin "99") (pinfunction "PH9_99") (pintype "bidirectional"))
    )
    (net (code "8") (name "BUTMAT_IN1") (class "Default")
      (node (ref "D7") (pin "A") (pinfunction "A_A") (pintype "passive"))
      (node (ref "U22") (pin "100") (pinfunction "PH10_100") (pintype "bidirectional"))
    )
    (net (code "9") (name "BUTMAT_IN2") (class "Default")
      (node (ref "D8") (pin "A") (pinfunction "A_A") (pintype "passive"))
      (node (ref "U22") (pin "101") (pinfunction "PH11_101") (pintype "bidirectional"))
    )
    (net (code "10") (name "BUTMAT_IN3") (class "Default")
      (node (ref "D9") (pin "A") (pinfunction "A_A") (pintype "passive"))
      (node (ref "U22") (pin "102") (pinfunction "PH12_102") (pintype "bidirectional"))
    )
    (net (code "11") (name "BUTMAT_IN4") (class "Default")
      (node (ref "D10") (pin "A") (pinfunction "A_A") (pintype "passive"))
      (node (ref "U22") (pin "151") (pinfunction "PH13_151") (pintype "bidirectional"))
    )
    (net (code "12") (name "BUTMAT_OUT0") (class "Default")
      (node (ref "R69") (pin "2") (pinfunction "2_2") (pintype "passive"))
      (node (ref "S2") (pin "3") (pinfunction "2_3") (pintype "passive"))
      (node (ref "S3") (pin "3") (pinfunction "2_3") (pintype "passive"))
      (node (ref "S4") (pin "3") (pinfunction "2_3") (pintype "passive"))
      (node (ref "S5") (pin "3") (pinfunction "2_3") (pintype "passive"))
      (node (ref "S6") (pin "3") (pinfunction "2_3") (pintype "passive"))
      (node (ref "U22") (pin "205") (pinfunction "PI4_205") (pintype "bidirectional"))
    )
    (net (code "13") (name "BUTMAT_OUT1") (class "Default")
      (node (ref "R68") (pin "2") (pinfunction "2_2") (pintype "passive"))
      (node (ref "S10") (pin "3") (pinfunction "2_3") (pintype "passive"))
      (node (ref "S11") (pin "3") (pinfunction "2_3") (pintype "passive"))
      (node (ref "S7") (pin "3") (pinfunction "2_3") (pintype "passive"))
      (node (ref "S8") (pin "3") (pinfunction "2_3") (pintype "passive"))
      (node (ref "S9") (pin "3") (pinfunction "2_3") (pintype "passive"))
      (node (ref "U22") (pin "206") (pinfunction "PI5_206") (pintype "bidirectional"))
    )
    (net (code "14") (name "BUTMAT_OUT2") (class "Default")
      (node (ref "R67") (pin "2") (pinfunction "2_2") (pintype "passive"))
      (node (ref "S12") (pin "3") (pinfunction "2_3") (pintype "passive"))
      (node (ref "S13") (pin "3") (pinfunction "2_3") (pintype "passive"))
      (node (ref "S14") (pin "3") (pinfunction "2_3") (pintype "passive"))
      (node (ref "S15") (pin "3") (pinfunction "2_3") (pintype "passive"))
      (node (ref "S16") (pin "3") (pinfunction "2_3") (pintype "passive"))
      (node (ref "U22") (pin "207") (pinfunction "PI6_207") (pintype "bidirectional"))
    )
    (net (code "15") (name "BUTMAT_OUT3") (class "Default")
      (node (ref "R66") (pin "2") (pinfunction "2_2") (pintype "passive"))
      (node (ref "S17") (pin "3") (pinfunction "2_3") (pintype "passive"))
      (node (ref "S18") (pin "3") (pinfunction "2_3") (pintype "passive"))
      (node (ref "S19") (pin "3") (pinfunction "2_3") (pintype "passive"))
      (node (ref "S20") (pin "3") (pinfunction "2_3") (pintype "passive"))
      (node (ref "S21") (pin "3") (pinfunction "2_3") (pintype "passive"))
      (node (ref "U22") (pin "208") (pinfunction "PI7_208") (pintype "bidirectional"))
    )
    (net (code "16") (name "BUTMAT_OUT4") (class "Default")
      (node (ref "R65") (pin "2") (pinfunction "2_2") (pintype "passive"))
      (node (ref "S22") (pin "3") (pinfunction "2_3") (pintype "passive"))
      (node (ref "S23") (pin "3") (pinfunction "2_3") (pintype "passive"))
      (node (ref "S24") (pin "3") (pinfunction "2_3") (pintype "passive"))
      (node (ref "U22") (pin "7") (pinfunction "PI8_7") (pintype "bidirectional"))
    )
    (net (code "17") (name "CHG_ACOK") (class "Default")
      (node (ref "R10") (pin "2") (pinfunction "2_2") (pintype "passive"))
      (node (ref "U1") (pin "5") (pinfunction "ACOK_5") (pintype "output"))
      (node (ref "U22") (pin "2") (pinfunction "PE3_2") (pintype "bidirectional"))
      (node (ref "U9") (pin "1") (pinfunction "EN_1") (pintype "passive"))
    )
    (net (code "18") (name "CHG_PROCHOT") (class "Default")
      (node (ref "R13") (pin "2") (pinfunction "2_2") (pintype "passive"))
      (node (ref "U1") (pin "10") (pinfunction "PROCHOT_N_10") (pintype "output"))
      (node (ref "U22") (pin "4") (pinfunction "PE5_4") (pintype "bidirectional"))
    )
    (net (code "19") (name "DACOUT_L") (class "Default")
      (node (ref "C50") (pin "1") (pinfunction "1_1") (pintype "passive"))
      (node (ref "R44") (pin "1") (pinfunction "1_1") (pintype "passive"))
      (node (ref "TP8") (pin "P$1") (pinfunction "1_P$1") (pintype "bidirectional"))
      (node (ref "U11") (pin "2") (pinfunction "A1_2") (pintype "passive"))
    )
    (net (code "20") (name "DACOUT_R") (class "Default")
      (node (ref "C51") (pin "1") (pinfunction "1_1") (pintype "passive"))
      (node (ref "R45") (pin "1") (pinfunction "1_1") (pintype "passive"))
      (node (ref "TP9") (pin "P$1") (pinfunction "1_P$1") (pintype "bidirectional"))
      (node (ref "U11") (pin "16") (pinfunction "A2_16") (pintype "passive"))
    )
    (net (code "21") (name "DAC_CLK") (class "Default")
      (node (ref "U15") (pin "2") (pinfunction "~{DEM/SCLK}_2") (pintype "input"))
      (node (ref "U22") (pin "143") (pinfunction "PA9_143") (pintype "bidirectional"))
    )
    (net (code "22") (name "DAC_DAT") (class "Default")
      (node (ref "U15") (pin "1") (pinfunction "SDIN_1") (pintype "input"))
      (node (ref "U22") (pin "107") (pinfunction "PB15_107") (pintype "bidirectional"))
    )
    (net (code "23") (name "DAC_MCLK") (class "Default")
      (node (ref "U15") (pin "4") (pinfunction "MCLK_4") (pintype "input"))
      (node (ref "U22") (pin "138") (pinfunction "PC6_138") (pintype "bidirectional"))
    )
    (net (code "24") (name "DAC_WS") (class "Default")
      (node (ref "U15") (pin "3") (pinfunction "LRCK_3") (pintype "input"))
      (node (ref "U22") (pin "154") (pinfunction "PI0_154") (pintype "bidirectional"))
    )
    (net (code "25") (name "DBG_RX") (class "Default")
      (node (ref "JP3") (pin "2") (pinfunction "2_2") (pintype "passive"))
      (node (ref "U22") (pin "172") (pinfunction "PD6_172") (pintype "bidirectional"))
    )
    (net (code "26") (name "DBG_TX") (class "Default")
      (node (ref "JP3") (pin "3") (pinfunction "3_3") (pintype "passive"))
      (node (ref "U22") (pin "45") (pinfunction "PA2_45") (pintype "bidirectional"))
    )
    (net (code "27") (name "FLASH_CLK") (class "Default")
      (node (ref "U17") (pin "6") (pinfunction "CLK_6") (pintype "input"))
      (node (ref "U22") (pin "63") (pinfunction "PB2_63") (pintype "bidirectional"))
    )
    (net (code "28") (name "FLASH_CS") (class "Default")
      (node (ref "R30") (pin "1") (pinfunction "1_1") (pintype "passive"))
      (node (ref "U17") (pin "1") (pinfunction "~{CS}_1") (pintype "input"))
      (node (ref "U22") (pin "133") (pinfunction "PG6_133") (pintype "bidirectional"))
    )
    (net (code "29") (name "FLASH_D0") (class "Default")
      (node (ref "U17") (pin "5") (pinfunction "DI(IO0)_5") (pintype "bidirectional"))
      (node (ref "U22") (pin "29") (pinfunction "PF8_29") (pintype "bidirectional"))
    )
    (net (code "30") (name "FLASH_D1") (class "Default")
      (node (ref "U17") (pin "2") (pinfunction "DO(IO1)_2") (pintype "bidirectional"))
      (node (ref "U22") (pin "30") (pinfunction "PF9_30") (pintype "bidirectional"))
    )
    (net (code "31") (name "FLASH_D2") (class "Default")
      (node (ref "U17") (pin "3") (pinfunction "/WP(IO2)_3") (pintype "bidirectional"))
      (node (ref "U22") (pin "28") (pinfunction "PF7_28") (pintype "bidirectional"))
    )
    (net (code "32") (name "FLASH_D3") (class "Default")
      (node (ref "U17") (pin "7") (pinfunction "/HOLD(IO3)_7") (pintype "bidirectional"))
      (node (ref "U22") (pin "27") (pinfunction "PF6_27") (pintype "bidirectional"))
    )
    (net (code "33") (name "GND") (class "Default")
      (node (ref "C1") (pin "2") (pinfunction "2_2") (pintype "passive"))
      (node (ref "C10") (pin "2") (pinfunction "2_2") (pintype "passive"))
      (node (ref "C100") (pin "2") (pinfunction "2_2") (pintype "passive"))
      (node (ref "C101") (pin "2") (pinfunction "2_2") (pintype "passive"))
      (node (ref "C102") (pin "2") (pinfunction "2_2") (pintype "passive"))
      (node (ref "C103") (pin "2") (pinfunction "2_2") (pintype "passive"))
      (node (ref "C104") (pin "2") (pinfunction "2_2") (pintype "passive"))
      (node (ref "C105") (pin "2") (pinfunction "2_2") (pintype "passive"))
      (node (ref "C106") (pin "2") (pinfunction "2_2") (pintype "passive"))
      (node (ref "C107") (pin "2") (pinfunction "2_2") (pintype "passive"))
      (node (ref "C108") (pin "2") (pinfunction "2_2") (pintype "passive"))
      (node (ref "C109") (pin "2") (pinfunction "2_2") (pintype "passive"))
      (node (ref "C110") (pin "2") (pinfunction "2_2") (pintype "passive"))
      (node (ref "C111") (pin "2") (pinfunction "2_2") (pintype "passive"))
      (node (ref "C112") (pin "1") (pinfunction "1_1") (pintype "passive"))
      (node (ref "C113") (pin "1") (pinfunction "1_1") (pintype "passive"))
      (node (ref "C114") (pin "1") (pinfunction "1_1") (pintype "passive"))
      (node (ref "C115") (pin "2") (pinfunction "2_2") (pintype "passive"))
      (node (ref "C116") (pin "1") (pinfunction "1_1") (pintype "passive"))
      (node (ref "C12") (pin "1") (pinfunction "1_1") (pintype "passive"))
      (node (ref "C13") (pin "1") (pinfunction "1_1") (pintype "passive"))
      (node (ref "C15") (pin "1") (pinfunction "1_1") (pintype "passive"))
      (node (ref "C16") (pin "1") (pinfunction "1_1") (pintype "passive"))
      (node (ref "C18") (pin "1") (pinfunction "1_1") (pintype "passive"))
      (node (ref "C19") (pin "1") (pinfunction "1_1") (pintype "passive"))
      (node (ref "C2") (pin "2") (pinfunction "2_2") (pintype "passive"))
      (node (ref "C20") (pin "2") (pinfunction "2_2") (pintype "passive"))
      (node (ref "C21") (pin "2") (pinfunction "2_2") (pintype "passive"))
      (node (ref "C22") (pin "2") (pinfunction "2_2") (pintype "passive"))
      (node (ref "C23") (pin "2") (pinfunction "2_2") (pintype "passive"))
      (node (ref "C24") (pin "2") (pinfunction "2_2") (pintype "passive"))
      (node (ref "C25") (pin "2") (pinfunction "2_2") (pintype "passive"))
      (node (ref "C26") (pin "2") (pinfunction "2_2") (pintype "passive"))
      (node (ref "C27") (pin "1") (pinfunction "1_1") (pintype "passive"))
      (node (ref "C28") (pin "1") (pinfunction "1_1") (pintype "passive"))
      (node (ref "C29") (pin "1") (pinfunction "1_1") (pintype "passive"))
      (node (ref "C30") (pin "-") (pinfunction "-_-") (pintype "passive"))
      (node (ref "C31") (pin "2") (pinfunction "2_2") (pintype "passive"))
      (node (ref "C32") (pin "2") (pinfunction "2_2") (pintype "passive"))
      (node (ref "C33") (pin "2") (pinfunction "2_2") (pintype "passive"))
      (node (ref "C34") (pin "2") (pinfunction "2_2") (pintype "passive"))
      (node (ref "C35") (pin "2") (pinfunction "2_2") (pintype "passive"))
      (node (ref "C36") (pin "2") (pinfunction "2_2") (pintype "passive"))
      (node (ref "C37") (pin "2") (pinfunction "2_2") (pintype "passive"))
      (node (ref "C38") (pin "2") (pinfunction "2_2") (pintype "passive"))
      (node (ref "C39") (pin "2") (pinfunction "2_2") (pintype "passive"))
      (node (ref "C4") (pin "1") (pinfunction "1_1") (pintype "passive"))
      (node (ref "C40") (pin "2") (pinfunction "2_2") (pintype "passive"))
      (node (ref "C41") (pin "2") (pinfunction "2_2") (pintype "passive"))
      (node (ref "C42") (pin "2") (pinfunction "2_2") (pintype "passive"))
      (node (ref "C43") (pin "2") (pinfunction "2_2") (pintype "passive"))
      (node (ref "C5") (pin "2") (pinfunction "2_2") (pintype "passive"))
      (node (ref "C67") (pin "2") (pinfunction "2_2") (pintype "passive"))
      (node (ref "C68") (pin "2") (pinfunction "2_2") (pintype "passive"))
      (node (ref "C69") (pin "2") (pinfunction "2_2") (pintype "passive"))
      (node (ref "C70") (pin "-") (pinfunction "-_-") (pintype "passive"))
      (node (ref "C71") (pin "2") (pinfunction "2_2") (pintype "passive"))
      (node (ref "C72") (pin "2") (pinfunction "2_2") (pintype "passive"))
      (node (ref "C73") (pin "2") (pinfunction "2_2") (pintype "passive"))
      (node (ref "C74") (pin "2") (pinfunction "2_2") (pintype "passive"))
      (node (ref "C75") (pin "2") (pinfunction "2_2") (pintype "passive"))
      (node (ref "C76") (pin "2") (pinfunction "2_2") (pintype "passive"))
      (node (ref "C77") (pin "2") (pinfunction "2_2") (pintype "passive"))
      (node (ref "C78") (pin "2") (pinfunction "2_2") (pintype "passive"))
      (node (ref "C79") (pin "2") (pinfunction "2_2") (pintype "passive"))
      (node (ref "C8") (pin "2") (pinfunction "2_2") (pintype "passive"))
      (node (ref "C80") (pin "2") (pinfunction "2_2") (pintype "passive"))
      (node (ref "C81") (pin "2") (pinfunction "2_2") (pintype "passive"))
      (node (ref "C82") (pin "2") (pinfunction "2_2") (pintype "passive"))
      (node (ref "C83") (pin "2") (pinfunction "2_2") (pintype "passive"))
      (node (ref "C84") (pin "2") (pinfunction "2_2") (pintype "passive"))
      (node (ref "C85") (pin "2") (pinfunction "2_2") (pintype "passive"))
      (node (ref "C86") (pin "2") (pinfunction "2_2") (pintype "passive"))
      (node (ref "C87") (pin "2") (pinfunction "2_2") (pintype "passive"))
      (node (ref "C88") (pin "2") (pinfunction "2_2") (pintype "passive"))
      (node (ref "C89") (pin "2") (pinfunction "2_2") (pintype "passive"))
      (node (ref "C9") (pin "2") (pinfunction "2_2") (pintype "passive"))
      (node (ref "C90") (pin "2") (pinfunction "2_2") (pintype "passive"))
      (node (ref "C91") (pin "1") (pinfunction "1_1") (pintype "passive"))
      (node (ref "C92") (pin "2") (pinfunction "2_2") (pintype "passive"))
      (node (ref "C93") (pin "2") (pinfunction "2_2") (pintype "passive"))
      (node (ref "C94") (pin "2") (pinfunction "2_2") (pintype "passive"))
      (node (ref "C95") (pin "2") (pinfunction "2_2") (pintype "passive"))
      (node (ref "C96") (pin "2") (pinfunction "2_2") (pintype "passive"))
      (node (ref "C97") (pin "2") (pinfunction "2_2") (pintype "passive"))
      (node (ref "C98") (pin "2") (pinfunction "2_2") (pintype "passive"))
      (node (ref "C99") (pin "2") (pinfunction "2_2") (pintype "passive"))
      (node (ref "D3") (pin "3") (pinfunction "P$3_3") (pintype "bidirectional"))
      (node (ref "D4") (pin "3") (pinfunction "P$3_3") (pintype "bidirectional"))
      (node (ref "D5") (pin "A") (pinfunction "A_A") (pintype "passive"))
      (node (ref "J1") (pin "A1") (pinfunction "GND1_A1") (pintype "passive"))
      (node (ref "J1") (pin "A12") (pinfunction "GND2_A12") (pintype "passive"))
      (node (ref "J1") (pin "B1") (pinfunction "GND3_B1") (pintype "passive"))
      (node (ref "J1") (pin "B12") (pinfunction "GND4_B12") (pintype "passive"))
      (node (ref "J1") (pin "S1") (pinfunction "SHIELD_S1") (pintype "passive"))
      (node (ref "J1") (pin "S2") (pinfunction "SHIELD_S2") (pintype "passive"))
      (node (ref "J1") (pin "S3") (pinfunction "SHIELD_S3") (pintype "passive"))
      (node (ref "J1") (pin "S4") (pinfunction "SHIELD_S4") (pintype "passive"))
      (node (ref "J2") (pin "6") (pinfunction "GND_6") (pintype "bidirectional"))
      (node (ref "J2") (pin "A") (pinfunction "A_A") (pintype "bidirectional"))
      (node (ref "J2") (pin "MOUNT0") (pinfunction "GND_MOUNT0") (pintype "bidirectional"))
      (node (ref "J2") (pin "MOUNT1") (pinfunction "GND_MOUNT1") (pintype "bidirectional"))
      (node (ref "J2") (pin "MOUNT2") (pinfunction "GND_MOUNT2") (pintype "bidirectional"))
      (node (ref "J2") (pin "MOUNT3") (pinfunction "GND_MOUNT3") (pintype "bidirectional"))
      (node (ref "J3") (pin "4") (pinfunction "P4_4") (pintype "passive"))
      (node (ref "J3") (pin "SH1") (pinfunction "GND_SH1") (pintype "passive"))
      (node (ref "J3") (pin "SH2") (pinfunction "GND_SH2") (pintype "passive"))
      (node (ref "J4") (pin "2") (pinfunction "2_2") (pintype "bidirectional"))
      (node (ref "J5") (pin "2") (pinfunction "2_2") (pintype "bidirectional"))
      (node (ref "J7") (pin "1") (pinfunction "1_1") (pintype "passive"))
      (node (ref "J7") (pin "4") (pinfunction "4_4") (pintype "passive"))
      (node (ref "JP1") (pin "11") (pinfunction "11_11") (pintype "passive"))
      (node (ref "JP1") (pin "12") (pinfunction "12_12") (pintype "passive"))
      (node (ref "JP1") (pin "19") (pinfunction "19_19") (pintype "passive"))
      (node (ref "JP1") (pin "20") (pinfunction "20_20") (pintype "passive"))
      (node (ref "JP1") (pin "27") (pinfunction "27_27") (pintype "passive"))
      (node (ref "JP1") (pin "28") (pinfunction "28_28") (pintype "passive"))
      (node (ref "JP1") (pin "40") (pinfunction "40_40") (pintype "passive"))
      (node (ref "JP1") (pin "8") (pinfunction "8_8") (pintype "passive"))
      (node (ref "JP2") (pin "3") (pinfunction "3_3") (pintype "passive"))
      (node (ref "JP3") (pin "1") (pinfunction "1_1") (pintype "passive"))
      (node (ref "OK1") (pin "5") (pinfunction "GND_5") (pintype "passive"))
      (node (ref "Q4") (pin "1") (pinfunction "S_1") (pintype "bidirectional"))
      (node (ref "Q4") (pin "2") (pinfunction "S_2") (pintype "bidirectional"))
      (node (ref "Q4") (pin "3") (pinfunction "S_3") (pintype "bidirectional"))
      (node (ref "R16") (pin "2") (pinfunction "2_2") (pintype "passive"))
      (node (ref "R18") (pin "1") (pinfunction "1_1") (pintype "passive"))
      (node (ref "R23") (pin "1") (pinfunction "1_1") (pintype "passive"))
      (node (ref "R26") (pin "1") (pinfunction "1_1") (pintype "passive"))
      (node (ref "R28") (pin "1") (pinfunction "1_1") (pintype "passive"))
      (node (ref "R33") (pin "1") (pinfunction "1_1") (pintype "passive"))
      (node (ref "R34") (pin "1") (pinfunction "1_1") (pintype "passive"))
      (node (ref "R4") (pin "1") (pinfunction "1_1") (pintype "passive"))
      (node (ref "R61") (pin "1") (pinfunction "1_1") (pintype "passive"))
      (node (ref "R63") (pin "1") (pinfunction "1_1") (pintype "passive"))
      (node (ref "R65") (pin "1") (pinfunction "1_1") (pintype "passive"))
      (node (ref "R66") (pin "1") (pinfunction "1_1") (pintype "passive"))
      (node (ref "R67") (pin "1") (pinfunction "1_1") (pintype "passive"))
      (node (ref "R68") (pin "1") (pinfunction "1_1") (pintype "passive"))
      (node (ref "R69") (pin "1") (pinfunction "1_1") (pintype "passive"))
      (node (ref "R70") (pin "1") (pinfunction "1_1") (pintype "passive"))
      (node (ref "R71") (pin "1") (pinfunction "1_1") (pintype "passive"))
      (node (ref "R72") (pin "1") (pinfunction "1_1") (pintype "passive"))
      (node (ref "R73") (pin "1") (pinfunction "1_1") (pintype "passive"))
      (node (ref "R74") (pin "1") (pinfunction "1_1") (pintype "passive"))
      (node (ref "R75") (pin "1") (pinfunction "1_1") (pintype "passive"))
      (node (ref "R76") (pin "1") (pinfunction "1_1") (pintype "passive"))
      (node (ref "S1") (pin "3") (pinfunction "P_3") (pintype "passive"))
      (node (ref "S1") (pin "4") (pinfunction "P1_4") (pintype "passive"))
      (node (ref "S25") (pin "1") (pinfunction "1_1") (pintype "passive"))
      (node (ref "SUPPLY1") (pin "P$1") (pinfunction "P$1_P$1") (pintype "bidirectional"))
      (node (ref "TP1") (pin "P$1") (pinfunction "1_P$1") (pintype "bidirectional"))
      (node (ref "U1") (pin "16") (pinfunction "CELL_16") (pintype "input"))
      (node (ref "U1") (pin "22") (pinfunction "GND_22") (pintype "power_in"))
      (node (ref "U1") (pin "29") (pinfunction "PAD_29") (pintype "power_in"))
      (node (ref "U10") (pin "2") (pinfunction "GND_2_2") (pintype "power_in"))
      (node (ref "U10") (pin "5") (pinfunction "GND_5") (pintype "power_in"))
      (node (ref "U16") (pin "2") (pinfunction "E1_2") (pintype "bidirectional"))
      (node (ref "U16") (pin "3") (pinfunction "E2_3") (pintype "bidirectional"))
      (node (ref "U16") (pin "4") (pinfunction "GND_4") (pintype "power_in"))
      (node (ref "U16") (pin "7") (pinfunction "~{WC}_7") (pintype "input"))
      (node (ref "U17") (pin "4") (pinfunction "GND_2_4") (pintype "passive"))
      (node (ref "U17") (pin "9") (pinfunction "GND_9") (pintype "passive"))
      (node (ref "U18") (pin "17") (pinfunction "GND_17") (pintype "passive"))
      (node (ref "U19") (pin "12") (pinfunction "VSSQ_12") (pintype "power_in"))
      (node (ref "U19") (pin "28") (pinfunction "VSS_28") (pintype "power_in"))
      (node (ref "U19") (pin "41") (pinfunction "VSS_41") (pintype "power_in"))
      (node (ref "U19") (pin "46") (pinfunction "VSSQ_46") (pintype "power_in"))
      (node (ref "U19") (pin "52") (pinfunction "VSSQ_52") (pintype "power_in"))
      (node (ref "U19") (pin "54") (pinfunction "VSS_54") (pintype "power_in"))
      (node (ref "U19") (pin "6") (pinfunction "VSSQ_6") (pintype "power_in"))
      (node (ref "U2") (pin "2") (pinfunction "GND_2") (pintype "passive"))
      (node (ref "U20") (pin "1") (pinfunction "GND_2_1") (pintype "power_in"))
      (node (ref "U20") (pin "2") (pinfunction "GND_2") (pintype "power_in"))
      (node (ref "U20") (pin "33") (pinfunction "EPAD_33") (pintype "passive"))
      (node (ref "U20") (pin "9") (pinfunction "RESET_9") (pintype "input"))
      (node (ref "U21") (pin "1") (pinfunction "OE_1") (pintype "input"))
      (node (ref "U21") (pin "3") (pinfunction "GND_3") (pintype "power_in"))
      (node (ref "U22") (pin "114") (pinfunction "VSS_9_114") (pintype "power_in"))
      (node (ref "U22") (pin "125") (pinfunction "VSS_10_125") (pintype "power_in"))
      (node (ref "U22") (pin "136") (pinfunction "VSS_11_136") (pintype "power_in"))
      (node (ref "U22") (pin "14") (pinfunction "VSS_2_14") (pintype "power_in"))
      (node (ref "U22") (pin "149") (pinfunction "VSS_12_149") (pintype "power_in"))
      (node (ref "U22") (pin "170") (pinfunction "VSS_13_170") (pintype "power_in"))
      (node (ref "U22") (pin "184") (pinfunction "VSS_14_184") (pintype "power_in"))
      (node (ref "U22") (pin "197") (pinfunction "BOOT0_197") (pintype "input"))
      (node (ref "U22") (pin "202") (pinfunction "VSS_202") (pintype "power_in"))
      (node (ref "U22") (pin "25") (pinfunction "VSS_3_25") (pintype "power_in"))
      (node (ref "U22") (pin "40") (pinfunction "VSSA_40") (pintype "power_in"))
      (node (ref "U22") (pin "51") (pinfunction "VSS_4_51") (pintype "power_in"))
      (node (ref "U22") (pin "60") (pinfunction "VSS_5_60") (pintype "power_in"))
      (node (ref "U22") (pin "72") (pinfunction "VSS_6_72") (pintype "power_in"))
      (node (ref "U22") (pin "82") (pinfunction "VSS_7_82") (pintype "power_in"))
      (node (ref "U22") (pin "93") (pinfunction "VSS_8_93") (pintype "power_in"))
      (node (ref "U3") (pin "13") (pinfunction "EPAD_13") (pintype "power_in"))
      (node (ref "U3") (pin "6") (pinfunction "VSS_6") (pintype "power_in"))
      (node (ref "U4") (pin "4") (pinfunction "AGND_4") (pintype "power_in"))
      (node (ref "U4") (pin "8") (pinfunction "PGND_8") (pintype "power_in"))
      (node (ref "U5") (pin "4") (pinfunction "AGND_4") (pintype "power_in"))
      (node (ref "U5") (pin "8") (pinfunction "PGND_8") (pintype "power_in"))
      (node (ref "U6") (pin "2") (pinfunction "GND_2") (pintype "power_in"))
      (node (ref "U7") (pin "2") (pinfunction "GND_2") (pintype "power_in"))
      (node (ref "U8") (pin "10") (pinfunction "GND_10") (pintype "passive"))
      (node (ref "U8") (pin "12") (pinfunction "ADDR0_12") (pintype "input"))
      (node (ref "U8") (pin "13") (pinfunction "ADDR1_13") (pintype "input"))
      (node (ref "U8") (pin "22") (pinfunction "VSYS_22") (pintype "power_in"))
      (node (ref "U8") (pin "25") (pinfunction "EP_25") (pintype "passive"))
      (node (ref "U8") (pin "6") (pinfunction "RESET_6") (pintype "input"))
      (node (ref "U9") (pin "4") (pinfunction "GND_4") (pintype "power_in"))
      (node (ref "VR1") (pin "1") (pinfunction "A_1") (pintype "passive"))
      (node (ref "VR1") (pin "4") (pinfunction "SHIELD_4") (pintype "bidirectional"))
      (node (ref "VR1") (pin "5") (pinfunction "SHIELD_5") (pintype "bidirectional"))
      (node (ref "VR2") (pin "1") (pinfunction "A_1") (pintype "passive"))
      (node (ref "VR2") (pin "4") (pinfunction "SHIELD_4") (pintype "bidirectional"))
      (node (ref "VR2") (pin "5") (pinfunction "SHIELD_5") (pintype "bidirectional"))
      (node (ref "VR3") (pin "1") (pinfunction "A_1") (pintype "passive"))
      (node (ref "VR4") (pin "1") (pinfunction "A_1") (pintype "passive"))
      (node (ref "VR4") (pin "4") (pinfunction "SHIELD_4") (pintype "bidirectional"))
      (node (ref "VR4") (pin "5") (pinfunction "SHIELD_5") (pintype "bidirectional"))
    )
    (net (code "34") (name "GUAGE_GPOUT") (class "Default")
      (node (ref "R22") (pin "2") (pinfunction "2_2") (pintype "passive"))
      (node (ref "U22") (pin "3") (pinfunction "PE4_3") (pintype "bidirectional"))
      (node (ref "U3") (pin "12") (pinfunction "BAT_LOW/BAT_GD_12") (pintype "output"))
    )
    (net (code "35") (name "HPOUT_INSERTED") (class "Default")
      (node (ref "J7") (pin "5") (pinfunction "5_5") (pintype "passive"))
      (node (ref "U22") (pin "36") (pinfunction "PC1_36") (pintype "bidirectional"))
    )
    (net (code "36") (name "HPOUT_L") (class "Default")
      (node (ref "J7") (pin "2") (pinfunction "2_2") (pintype "passive"))
      (node (ref "TP11") (pin "P$1") (pinfunction "1_P$1") (pintype "bidirectional"))
      (node (ref "U14") (pin "14") (pinfunction "HPLEFT_14") (pintype "output"))
    )
    (net (code "37") (name "HPOUT_R") (class "Default")
      (node (ref "J7") (pin "3") (pinfunction "3_3") (pintype "passive"))
      (node (ref "TP10") (pin "P$1") (pinfunction "1_P$1") (pintype "bidirectional"))
      (node (ref "U14") (pin "11") (pinfunction "HPRIGHT_11") (pintype "output"))
    )
    (net (code "38") (name "KNOB1") (class "Default")
      (node (ref "U22") (pin "55") (pinfunction "PA6_55") (pintype "bidirectional"))
      (node (ref "VR1") (pin "2") (pinfunction "S_2") (pintype "passive"))
    )
    (net (code "39") (name "KNOB2") (class "Default")
      (node (ref "U22") (pin "56") (pinfunction "PA7_56") (pintype "bidirectional"))
      (node (ref "VR2") (pin "2") (pinfunction "S_2") (pintype "passive"))
    )
    (net (code "40") (name "KNOB3") (class "Default")
      (node (ref "U22") (pin "57") (pinfunction "PC4_57") (pintype "bidirectional"))
      (node (ref "VR4") (pin "2") (pinfunction "S_2") (pintype "passive"))
    )
    (net (code "41") (name "LCD_B2") (class "Default")
      (node (ref "JP1") (pin "29") (pinfunction "29_29") (pintype "passive"))
      (node (ref "U22") (pin "176") (pinfunction "PJ14_176") (pintype "bidirectional"))
    )
    (net (code "42") (name "LCD_B3") (class "Default")
      (node (ref "JP1") (pin "30") (pinfunction "30_30") (pintype "passive"))
      (node (ref "U22") (pin "142") (pinfunction "PA8_142") (pintype "bidirectional"))
    )
    (net (code "43") (name "LCD_B4") (class "Default")
      (node (ref "JP1") (pin "31") (pinfunction "31_31") (pintype "passive"))
      (node (ref "U22") (pin "144") (pinfunction "PA10_144") (pintype "bidirectional"))
    )
    (net (code "44") (name "LCD_B5") (class "Default")
      (node (ref "JP1") (pin "32") (pinfunction "32_32") (pintype "passive"))
      (node (ref "U22") (pin "187") (pinfunction "PK4_187") (pintype "bidirectional"))
    )
    (net (code "45") (name "LCD_B6") (class "Default")
      (node (ref "JP1") (pin "33") (pinfunction "33_33") (pintype "passive"))
      (node (ref "U22") (pin "188") (pinfunction "PK5_188") (pintype "bidirectional"))
    )
    (net (code "46") (name "LCD_B7") (class "Default")
      (node (ref "JP1") (pin "34") (pinfunction "34_34") (pintype "passive"))
      (node (ref "U22") (pin "189") (pinfunction "PK6_189") (pintype "bidirectional"))
    )
    (net (code "47") (name "LCD_CLK") (class "Default")
      (node (ref "JP1") (pin "35") (pinfunction "35_35") (pintype "passive"))
      (node (ref "U22") (pin "21") (pinfunction "PI14_21") (pintype "bidirectional"))
    )
    (net (code "48") (name "LCD_DE") (class "Default")
      (node (ref "JP1") (pin "39") (pinfunction "39_39") (pintype "passive"))
      (node (ref "U22") (pin "31") (pinfunction "PF10_31") (pintype "bidirectional"))
    )
    (net (code "49") (name "LCD_G2") (class "Default")
      (node (ref "JP1") (pin "21") (pinfunction "21_21") (pintype "passive"))
      (node (ref "U22") (pin "64") (pinfunction "PI15_64") (pintype "bidirectional"))
    )
    (net (code "50") (name "LCD_G3") (class "Default")
      (node (ref "JP1") (pin "22") (pinfunction "22_22") (pintype "passive"))
      (node (ref "U22") (pin "122") (pinfunction "PJ10_122") (pintype "bidirectional"))
    )
    (net (code "51") (name "LCD_G4") (class "Default")
      (node (ref "JP1") (pin "23") (pinfunction "23_23") (pintype "passive"))
      (node (ref "U22") (pin "123") (pinfunction "PJ11_123") (pintype "bidirectional"))
    )
    (net (code "52") (name "LCD_G5") (class "Default")
      (node (ref "JP1") (pin "24") (pinfunction "24_24") (pintype "passive"))
      (node (ref "U22") (pin "48") (pinfunction "PH4_48") (pintype "bidirectional"))
    )
    (net (code "53") (name "LCD_G6") (class "Default")
      (node (ref "JP1") (pin "25") (pinfunction "25_25") (pintype "passive"))
      (node (ref "U22") (pin "127") (pinfunction "PK1_127") (pintype "bidirectional"))
    )
    (net (code "54") (name "LCD_G7") (class "Default")
      (node (ref "JP1") (pin "26") (pinfunction "26_26") (pintype "passive"))
      (node (ref "U22") (pin "128") (pinfunction "PK2_128") (pintype "bidirectional"))
    )
    (net (code "55") (name "LCD_HSYNC") (class "Default")
      (node (ref "JP1") (pin "37") (pinfunction "37_37") (pintype "passive"))
      (node (ref "U22") (pin "12") (pinfunction "PI10_12") (pintype "bidirectional"))
    )
    (net (code "56") (name "LCD_R2") (class "Default")
      (node (ref "JP1") (pin "13") (pinfunction "13_13") (pintype "passive"))
      (node (ref "U22") (pin "66") (pinfunction "PJ1_66") (pintype "bidirectional"))
    )
    (net (code "57") (name "LCD_R3") (class "Default")
      (node (ref "JP1") (pin "14") (pinfunction "14_14") (pintype "passive"))
      (node (ref "U22") (pin "67") (pinfunction "PJ2_67") (pintype "bidirectional"))
    )
    (net (code "58") (name "LCD_R4") (class "Default")
      (node (ref "JP1") (pin "15") (pinfunction "15_15") (pintype "passive"))
      (node (ref "U22") (pin "68") (pinfunction "PJ3_68") (pintype "bidirectional"))
    )
    (net (code "59") (name "LCD_R5") (class "Default")
      (node (ref "JP1") (pin "16") (pinfunction "16_16") (pintype "passive"))
      (node (ref "U22") (pin "69") (pinfunction "PJ4_69") (pintype "bidirectional"))
    )
    (net (code "60") (name "LCD_R6") (class "Default")
      (node (ref "JP1") (pin "17") (pinfunction "17_17") (pintype "passive"))
      (node (ref "U22") (pin "95") (pinfunction "PJ5_95") (pintype "bidirectional"))
    )
    (net (code "61") (name "LCD_R7") (class "Default")
      (node (ref "JP1") (pin "18") (pinfunction "18_18") (pintype "passive"))
      (node (ref "U22") (pin "65") (pinfunction "PJ0_65") (pintype "bidirectional"))
    )
    (net (code "62") (name "LCD_VSYNC") (class "Default")
      (node (ref "JP1") (pin "36") (pinfunction "36_36") (pintype "passive"))
      (node (ref "U22") (pin "11") (pinfunction "PI9_11") (pintype "bidirectional"))
    )
    (net (code "63") (name "LED0") (class "Default")
      (node (ref "LED1") (pin "A") (pinfunction "A_A") (pintype "passive"))
      (node (ref "U22") (pin "19") (pinfunction "PI12_19") (pintype "bidirectional"))
    )
    (net (code "64") (name "LED1") (class "Default")
      (node (ref "LED2") (pin "A") (pinfunction "A_A") (pintype "passive"))
      (node (ref "U22") (pin "20") (pinfunction "PI13_20") (pintype "bidirectional"))
    )
    (net (code "65") (name "LED2") (class "Default")
      (node (ref "LED3") (pin "A") (pinfunction "A_A") (pintype "passive"))
      (node (ref "U22") (pin "118") (pinfunction "PJ6_118") (pintype "bidirectional"))
    )
    (net (code "66") (name "LED3") (class "Default")
      (node (ref "LED4") (pin "A") (pinfunction "A_A") (pintype "passive"))
      (node (ref "U22") (pin "167") (pinfunction "PD3_167") (pintype "bidirectional"))
    )
    (net (code "67") (name "LED4") (class "Default")
      (node (ref "LED5") (pin "A") (pinfunction "A_A") (pintype "passive"))
      (node (ref "U22") (pin "168") (pinfunction "PD4_168") (pintype "bidirectional"))
    )
    (net (code "68") (name "LED5") (class "Default")
      (node (ref "LED6") (pin "A") (pinfunction "A_A") (pintype "passive"))
      (node (ref "U22") (pin "177") (pinfunction "PJ15_177") (pintype "bidirectional"))
    )
    (net (code "69") (name "LED6") (class "Default")
      (node (ref "LED7") (pin "A") (pinfunction "A_A") (pintype "passive"))
      (node (ref "U22") (pin "179") (pinfunction "PG10_179") (pintype "bidirectional"))
    )
    (net (code "70") (name "MIDI_RX") (class "Default")
      (node (ref "OK1") (pin "6") (pinfunction "VO_6") (pintype "passive"))
      (node (ref "R55") (pin "1") (pinfunction "1_1") (pintype "passive"))
      (node (ref "U22") (pin "139") (pinfunction "PC7_139") (pintype "bidirectional"))
    )
    (net (code "71") (name "MIDI_TX") (class "Default")
      (node (ref "U21") (pin "2") (pinfunction "I_2") (pintype "input"))
      (node (ref "U22") (pin "183") (pinfunction "PG14_183") (pintype "bidirectional"))
    )
    (net (code "72") (name "Net-(C6-Pad1)") (class "Default")
      (node (ref "C6") (pin "1") (pinfunction "1_1") (pintype "passive"))
      (node (ref "Q1") (pin "1") (pinfunction "S_1") (pintype "bidirectional"))
      (node (ref "Q1") (pin "2") (pinfunction "S_2") (pintype "bidirectional"))
      (node (ref "Q1") (pin "3") (pinfunction "S_3") (pintype "bidirectional"))
      (node (ref "Q2") (pin "1") (pinfunction "S_1") (pintype "bidirectional"))
      (node (ref "Q2") (pin "2") (pinfunction "S_2") (pintype "bidirectional"))
      (node (ref "Q2") (pin "3") (pinfunction "S_3") (pintype "bidirectional"))
      (node (ref "R6") (pin "2") (pinfunction "2_2") (pintype "passive"))
    )
    (net (code "73") (name "Net-(C45-Pad2)") (class "Default")
      (node (ref "C45") (pin "2") (pinfunction "2_2") (pintype "passive"))
      (node (ref "R43") (pin "2") (pinfunction "2_2") (pintype "passive"))
      (node (ref "R44") (pin "2") (pinfunction "2_2") (pintype "passive"))
    )
    (net (code "74") (name "Net-(C46-Pad2)") (class "Default")
      (node (ref "C46") (pin "2") (pinfunction "2_2") (pintype "passive"))
      (node (ref "R42") (pin "2") (pinfunction "2_2") (pintype "passive"))
      (node (ref "R45") (pin "2") (pinfunction "2_2") (pintype "passive"))
    )
    (net (code "75") (name "Net-(C59-Pad2)") (class "Default")
      (node (ref "C59") (pin "2") (pinfunction "2_2") (pintype "passive"))
      (node (ref "R48") (pin "1") (pinfunction "1_1") (pintype "passive"))
    )
    (net (code "76") (name "Net-(C66-Pad2)") (class "Default")
      (node (ref "C66") (pin "2") (pinfunction "2_2") (pintype "passive"))
      (node (ref "R50") (pin "1") (pinfunction "1_1") (pintype "passive"))
    )
    (net (code "77") (name "Net-(D1-C)") (class "Default")
      (node (ref "D1") (pin "3") (pinfunction "C_3") (pintype "passive"))
      (node (ref "D2") (pin "3") (pinfunction "C_3") (pintype "passive"))
      (node (ref "R1") (pin "2") (pinfunction "2_2") (pintype "passive"))
    )
    (net (code "78") (name "Net-(D3-P$1)") (class "Default")
      (node (ref "D3") (pin "1") (pinfunction "P$1_1") (pintype "bidirectional"))
      (node (ref "J1") (pin "B5") (pinfunction "CC2_B5") (pintype "passive"))
      (node (ref "U8") (pin "4") (pinfunction "CC2_4") (pintype "passive"))
      (node (ref "U8") (pin "5") (pinfunction "CC2DB_5") (pintype "passive"))
    )
    (net (code "79") (name "Net-(D3-P$2)") (class "Default")
      (node (ref "D3") (pin "2") (pinfunction "P$2_2") (pintype "bidirectional"))
      (node (ref "J1") (pin "A5") (pinfunction "CC1_A5") (pintype "passive"))
      (node (ref "U8") (pin "1") (pinfunction "CC1DB_1") (pintype "passive"))
      (node (ref "U8") (pin "2") (pinfunction "CC1_2") (pintype "passive"))
    )
    (net (code "80") (name "Net-(D6-PadC)") (class "Default")
      (node (ref "D6") (pin "C") (pinfunction "C_C") (pintype "passive"))
      (node (ref "S12") (pin "1") (pinfunction "1_1") (pintype "passive"))
      (node (ref "S17") (pin "1") (pinfunction "1_1") (pintype "passive"))
      (node (ref "S2") (pin "1") (pinfunction "1_1") (pintype "passive"))
      (node (ref "S22") (pin "1") (pinfunction "1_1") (pintype "passive"))
      (node (ref "S7") (pin "1") (pinfunction "1_1") (pintype "passive"))
    )
    (net (code "81") (name "Net-(D7-PadC)") (class "Default")
      (node (ref "D7") (pin "C") (pinfunction "C_C") (pintype "passive"))
      (node (ref "S13") (pin "1") (pinfunction "1_1") (pintype "passive"))
      (node (ref "S18") (pin "1") (pinfunction "1_1") (pintype "passive"))
      (node (ref "S23") (pin "1") (pinfunction "1_1") (pintype "passive"))
      (node (ref "S3") (pin "1") (pinfunction "1_1") (pintype "passive"))
      (node (ref "S8") (pin "1") (pinfunction "1_1") (pintype "passive"))
    )
    (net (code "82") (name "Net-(D8-PadC)") (class "Default")
      (node (ref "D8") (pin "C") (pinfunction "C_C") (pintype "passive"))
      (node (ref "S14") (pin "1") (pinfunction "1_1") (pintype "passive"))
      (node (ref "S19") (pin "1") (pinfunction "1_1") (pintype "passive"))
      (node (ref "S24") (pin "1") (pinfunction "1_1") (pintype "passive"))
      (node (ref "S4") (pin "1") (pinfunction "1_1") (pintype "passive"))
      (node (ref "S9") (pin "1") (pinfunction "1_1") (pintype "passive"))
    )
    (net (code "83") (name "Net-(D9-PadC)") (class "Default")
      (node (ref "D9") (pin "C") (pinfunction "C_C") (pintype "passive"))
      (node (ref "S10") (pin "1") (pinfunction "1_1") (pintype "passive"))
      (node (ref "S15") (pin "1") (pinfunction "1_1") (pintype "passive"))
      (node (ref "S20") (pin "1") (pinfunction "1_1") (pintype "passive"))
      (node (ref "S5") (pin "1") (pinfunction "1_1") (pintype "passive"))
    )
    (net (code "84") (name "Net-(D10-PadC)") (class "Default")
      (node (ref "D10") (pin "C") (pinfunction "C_C") (pintype "passive"))
      (node (ref "S11") (pin "1") (pinfunction "1_1") (pintype "passive"))
      (node (ref "S16") (pin "1") (pinfunction "1_1") (pintype "passive"))
      (node (ref "S21") (pin "1") (pinfunction "1_1") (pintype "passive"))
      (node (ref "S6") (pin "1") (pinfunction "1_1") (pintype "passive"))
    )
    (net (code "85") (name "Net-(J1-VBUS1)") (class "Default")
      (node (ref "C39") (pin "1") (pinfunction "1_1") (pintype "passive"))
      (node (ref "D5") (pin "C") (pinfunction "C_C") (pintype "passive"))
      (node (ref "J1") (pin "A4") (pinfunction "VBUS1_A4") (pintype "passive"))
      (node (ref "J1") (pin "A9") (pinfunction "VBUS2_A9") (pintype "passive"))
      (node (ref "J1") (pin "B4") (pinfunction "VBUS3_B4") (pintype "passive"))
      (node (ref "J1") (pin "B9") (pinfunction "VBUS4_B9") (pintype "passive"))
      (node (ref "Q6") (pin "1") (pinfunction "S_1") (pintype "bidirectional"))
      (node (ref "Q6") (pin "2") (pinfunction "S_2") (pintype "bidirectional"))
      (node (ref "Q6") (pin "3") (pinfunction "S_3") (pintype "bidirectional"))
      (node (ref "R35") (pin "2") (pinfunction "2_2") (pintype "passive"))
      (node (ref "R36") (pin "2") (pinfunction "2_2") (pintype "passive"))
      (node (ref "TP4") (pin "P$1") (pinfunction "1_P$1") (pintype "bidirectional"))
      (node (ref "U8") (pin "24") (pinfunction "VDD_24") (pintype "power_in"))
    )
    (net (code "86") (name "Net-(J2-CLK)") (class "Default")
      (node (ref "J2") (pin "5") (pinfunction "CLK_5") (pintype "bidirectional"))
      (node (ref "U18") (pin "3") (pinfunction "CLKIN_3") (pintype "input"))
    )
    (net (code "87") (name "Net-(J2-CMD{slash}MOSI)") (class "Default")
      (node (ref "J2") (pin "3") (pinfunction "CMD/MOSI_3") (pintype "bidirectional"))
      (node (ref "U18") (pin "6") (pinfunction "CMDIN_6") (pintype "input"))
    )
    (net (code "88") (name "Net-(J2-DATA0{slash}MISO)") (class "Default")
      (node (ref "J2") (pin "7") (pinfunction "DATA0/MISO_7") (pintype "bidirectional"))
      (node (ref "U18") (pin "2") (pinfunction "DAT0IN_2") (pintype "input"))
    )
    (net (code "89") (name "Net-(J2-DATA1{slash}RSV)") (class "Default")
      (node (ref "J2") (pin "8") (pinfunction "DATA1/RSV_8") (pintype "bidirectional"))
      (node (ref "U18") (pin "1") (pinfunction "DAT1IN_1") (pintype "input"))
    )
    (net (code "90") (name "Net-(J2-DATA2{slash}NC)") (class "Default")
      (node (ref "J2") (pin "1") (pinfunction "DATA2/NC_1") (pintype "bidirectional"))
      (node (ref "U18") (pin "8") (pinfunction "DAT2IN_8") (pintype "input"))
    )
    (net (code "91") (name "Net-(J2-DATA3-CD{slash}CS_N)") (class "Default")
      (node (ref "J2") (pin "2") (pinfunction "DATA3-CD/CS_N_2") (pintype "bidirectional"))
      (node (ref "R57") (pin "1") (pinfunction "1_1") (pintype "passive"))
      (node (ref "U18") (pin "7") (pinfunction "DAT3IN_7") (pintype "input"))
    )
    (net (code "92") (name "Net-(J4-Pad4)") (class "Default")
      (node (ref "J4") (pin "4") (pinfunction "4_4") (pintype "bidirectional"))
      (node (ref "R56") (pin "1") (pinfunction "1_1") (pintype "passive"))
    )
    (net (code "93") (name "Net-(J5-Pad4)") (class "Default")
      (node (ref "J5") (pin "4") (pinfunction "4_4") (pintype "bidirectional"))
      (node (ref "R54") (pin "1") (pinfunction "1_1") (pintype "passive"))
    )
    (net (code "94") (name "Net-(J5-Pad5)") (class "Default")
      (node (ref "J5") (pin "5") (pinfunction "5_5") (pintype "bidirectional"))
      (node (ref "R53") (pin "1") (pinfunction "1_1") (pintype "passive"))
    )
    (net (code "95") (name "Net-(LED1-PadC)") (class "Default")
      (node (ref "LED1") (pin "C") (pinfunction "C_C") (pintype "passive"))
      (node (ref "R76") (pin "2") (pinfunction "2_2") (pintype "passive"))
    )
    (net (code "96") (name "Net-(LED2-PadC)") (class "Default")
      (node (ref "LED2") (pin "C") (pinfunction "C_C") (pintype "passive"))
      (node (ref "R75") (pin "2") (pinfunction "2_2") (pintype "passive"))
    )
    (net (code "97") (name "Net-(LED3-PadC)") (class "Default")
      (node (ref "LED3") (pin "C") (pinfunction "C_C") (pintype "passive"))
      (node (ref "R74") (pin "2") (pinfunction "2_2") (pintype "passive"))
    )
    (net (code "98") (name "Net-(LED4-PadC)") (class "Default")
      (node (ref "LED4") (pin "C") (pinfunction "C_C") (pintype "passive"))
      (node (ref "R73") (pin "2") (pinfunction "2_2") (pintype "passive"))
    )
    (net (code "99") (name "Net-(LED5-PadC)") (class "Default")
      (node (ref "LED5") (pin "C") (pinfunction "C_C") (pintype "passive"))
      (node (ref "R72") (pin "2") (pinfunction "2_2") (pintype "passive"))
    )
    (net (code "100") (name "Net-(LED6-PadC)") (class "Default")
      (node (ref "LED6") (pin "C") (pinfunction "C_C") (pintype "passive"))
      (node (ref "R71") (pin "2") (pinfunction "2_2") (pintype "passive"))
    )
    (net (code "101") (name "Net-(LED7-PadC)") (class "Default")
      (node (ref "LED7") (pin "C") (pinfunction "C_C") (pintype "passive"))
      (node (ref "R70") (pin "2") (pinfunction "2_2") (pintype "passive"))
    )
    (net (code "102") (name "Net-(OK1-A)") (class "Default")
      (node (ref "OK1") (pin "2") (pinfunction "A_2") (pintype "passive"))
      (node (ref "R56") (pin "2") (pinfunction "2_2") (pintype "passive"))
    )
    (net (code "103") (name "Net-(OK1-C)") (class "Default")
      (node (ref "J4") (pin "5") (pinfunction "5_5") (pintype "bidirectional"))
      (node (ref "OK1") (pin "3") (pinfunction "C_3") (pintype "passive"))
    )
    (net (code "104") (name "Net-(Q1-G)") (class "Default")
      (node (ref "C6") (pin "2") (pinfunction "2_2") (pintype "passive"))
      (node (ref "C7") (pin "2") (pinfunction "2_2") (pintype "passive"))
      (node (ref "Q1") (pin "4") (pinfunction "G_4") (pintype "bidirectional"))
      (node (ref "Q2") (pin "4") (pinfunction "G_4") (pintype "bidirectional"))
      (node (ref "R5") (pin "2") (pinfunction "2_2") (pintype "passive"))
    )
    (net (code "105") (name "Net-(Q3-G)") (class "Default")
      (node (ref "Q3") (pin "4") (pinfunction "G_4") (pintype "bidirectional"))
      (node (ref "R8") (pin "2") (pinfunction "2_2") (pintype "passive"))
    )
    (net (code "106") (name "Net-(Q4-G)") (class "Default")
      (node (ref "Q4") (pin "4") (pinfunction "G_4") (pintype "bidirectional"))
      (node (ref "U1") (pin "23") (pinfunction "LODRV_23") (pintype "output"))
    )
    (net (code "107") (name "Net-(Q5-G)") (class "Default")
      (node (ref "Q5") (pin "4") (pinfunction "G_4") (pintype "bidirectional"))
      (node (ref "U1") (pin "26") (pinfunction "HIDRV_26") (pintype "output"))
    )
    (net (code "108") (name "Net-(Q6-G)") (class "Default")
      (node (ref "Q6") (pin "4") (pinfunction "G_4") (pintype "bidirectional"))
      (node (ref "R36") (pin "1") (pinfunction "1_1") (pintype "passive"))
      (node (ref "R37") (pin "2") (pinfunction "2_2") (pintype "passive"))
    )
    (net (code "109") (name "Net-(TP12-1)") (class "Default")
      (node (ref "C59") (pin "1") (pinfunction "1_1") (pintype "passive"))
      (node (ref "TP12") (pin "P$1") (pinfunction "1_P$1") (pintype "bidirectional"))
      (node (ref "U11") (pin "3") (pinfunction "W1_3") (pintype "passive"))
    )
    (net (code "110") (name "Net-(TP13-1)") (class "Default")
      (node (ref "C66") (pin "1") (pinfunction "1_1") (pintype "passive"))
      (node (ref "TP13") (pin "P$1") (pinfunction "1_P$1") (pintype "bidirectional"))
      (node (ref "U11") (pin "15") (pinfunction "W2_15") (pintype "passive"))
    )
    (net (code "111") (name "Net-(U1-ACDET)") (class "Default")
      (node (ref "R3") (pin "1") (pinfunction "1_1") (pintype "passive"))
      (node (ref "R4") (pin "2") (pinfunction "2_2") (pintype "passive"))
      (node (ref "U1") (pin "6") (pinfunction "ACDET_6") (pintype "input"))
    )
    (net (code "112") (name "Net-(U1-ACDRV)") (class "Default")
      (node (ref "R5") (pin "1") (pinfunction "1_1") (pintype "passive"))
      (node (ref "U1") (pin "4") (pinfunction "ACDRV_4") (pintype "input"))
    )
    (net (code "113") (name "Net-(U1-ACN)") (class "Default")
      (node (ref "C15") (pin "2") (pinfunction "2_2") (pintype "passive"))
      (node (ref "C16") (pin "2") (pinfunction "2_2") (pintype "passive"))
      (node (ref "C3") (pin "2") (pinfunction "2_2") (pintype "passive"))
      (node (ref "C5") (pin "1") (pinfunction "1_1") (pintype "passive"))
      (node (ref "Q5") (pin "5") (pinfunction "D_5") (pintype "bidirectional"))
      (node (ref "Q5") (pin "6") (pinfunction "D_6") (pintype "bidirectional"))
      (node (ref "Q5") (pin "7") (pinfunction "D_7") (pintype "bidirectional"))
      (node (ref "Q5") (pin "8") (pinfunction "D_8") (pintype "bidirectional"))
      (node (ref "R2") (pin "2") (pinfunction "2_2") (pintype "passive"))
      (node (ref "U1") (pin "1") (pinfunction "ACN_1") (pintype "input"))
    )
    (net (code "114") (name "Net-(U1-ACP)") (class "Default")
      (node (ref "C3") (pin "1") (pinfunction "1_1") (pintype "passive"))
      (node (ref "C4") (pin "2") (pinfunction "2_2") (pintype "passive"))
      (node (ref "Q2") (pin "5") (pinfunction "D_5") (pintype "bidirectional"))
      (node (ref "Q2") (pin "6") (pinfunction "D_6") (pintype "bidirectional"))
      (node (ref "Q2") (pin "7") (pinfunction "D_7") (pintype "bidirectional"))
      (node (ref "Q2") (pin "8") (pinfunction "D_8") (pintype "bidirectional"))
      (node (ref "R2") (pin "1") (pinfunction "1_1") (pintype "passive"))
      (node (ref "U1") (pin "2") (pinfunction "ACP_2") (pintype "input"))
    )
    (net (code "115") (name "Net-(U1-BAT)") (class "Default")
      (node (ref "R7") (pin "1") (pinfunction "1_1") (pintype "passive"))
      (node (ref "U1") (pin "17") (pinfunction "BAT_17") (pintype "input"))
    )
    (net (code "116") (name "Net-(U1-BATDRV_N)") (class "Default")
      (node (ref "R8") (pin "1") (pinfunction "1_1") (pintype "passive"))
      (node (ref "U1") (pin "18") (pinfunction "BATDRV_N_18") (pintype "output"))
    )
    (net (code "117") (name "Net-(U1-BATPRES_N)") (class "Default")
      (node (ref "R14") (pin "2") (pinfunction "2_2") (pintype "passive"))
      (node (ref "R15") (pin "2") (pinfunction "2_2") (pintype "passive"))
      (node (ref "U1") (pin "14") (pinfunction "CMPOUT_14") (pintype "output"))
      (node (ref "U1") (pin "15") (pinfunction "BATPRES_N_15") (pintype "input"))
    )
    (net (code "118") (name "Net-(U1-BTST)") (class "Default")
      (node (ref "C14") (pin "2") (pinfunction "2_2") (pintype "passive"))
      (node (ref "U1") (pin "25") (pinfunction "BTST_25") (pintype "power_in"))
    )
    (net (code "119") (name "Net-(U1-CMSRC)") (class "Default")
      (node (ref "R6") (pin "1") (pinfunction "1_1") (pintype "passive"))
      (node (ref "U1") (pin "3") (pinfunction "CMSRC_3") (pintype "input"))
    )
    (net (code "120") (name "Net-(U1-ILIM)") (class "Default")
      (node (ref "R23") (pin "2") (pinfunction "2_2") (pintype "passive"))
      (node (ref "R24") (pin "1") (pinfunction "1_1") (pintype "passive"))
      (node (ref "U1") (pin "21") (pinfunction "ILIM_21") (pintype "input"))
    )
    (net (code "121") (name "Net-(U1-PHASE)") (class "Default")
      (node (ref "C14") (pin "1") (pinfunction "1_1") (pintype "passive"))
      (node (ref "L1") (pin "1") (pinfunction "1_1") (pintype "passive"))
      (node (ref "Q4") (pin "5") (pinfunction "D_5") (pintype "bidirectional"))
      (node (ref "Q4") (pin "6") (pinfunction "D_6") (pintype "bidirectional"))
      (node (ref "Q4") (pin "7") (pinfunction "D_7") (pintype "bidirectional"))
      (node (ref "Q4") (pin "8") (pinfunction "D_8") (pintype "bidirectional"))
      (node (ref "Q5") (pin "1") (pinfunction "S_1") (pintype "bidirectional"))
      (node (ref "Q5") (pin "2") (pinfunction "S_2") (pintype "bidirectional"))
      (node (ref "Q5") (pin "3") (pinfunction "S_3") (pintype "bidirectional"))
      (node (ref "U1") (pin "27") (pinfunction "PHASE_27") (pintype "power_in"))
    )
    (net (code "122") (name "Net-(U1-REGN)") (class "Default")
      (node (ref "C2") (pin "1") (pinfunction "1_1") (pintype "passive"))
      (node (ref "U1") (pin "24") (pinfunction "REGN_24") (pintype "power_in"))
    )
    (net (code "123") (name "Net-(U1-SRN)") (class "Default")
      (node (ref "C11") (pin "2") (pinfunction "2_2") (pintype "passive"))
      (node (ref "C12") (pin "2") (pinfunction "2_2") (pintype "passive"))
      (node (ref "C9") (pin "1") (pinfunction "1_1") (pintype "passive"))
      (node (ref "Q3") (pin "5") (pinfunction "D_5") (pintype "bidirectional"))
      (node (ref "Q3") (pin "6") (pinfunction "D_6") (pintype "bidirectional"))
      (node (ref "Q3") (pin "7") (pinfunction "D_7") (pintype "bidirectional"))
      (node (ref "Q3") (pin "8") (pinfunction "D_8") (pintype "bidirectional"))
      (node (ref "R9") (pin "2") (pinfunction "2_2") (pintype "passive"))
      (node (ref "U1") (pin "19") (pinfunction "SRN_19") (pintype "input"))
    )
    (net (code "124") (name "Net-(U1-VCC)") (class "Default")
      (node (ref "C1") (pin "1") (pinfunction "1_1") (pintype "passive"))
      (node (ref "R1") (pin "1") (pinfunction "1_1") (pintype "passive"))
      (node (ref "U1") (pin "28") (pinfunction "VCC_28") (pintype "power_in"))
    )
    (net (code "125") (name "Net-(U3-BI{slash}TOUT)") (class "Default")
      (node (ref "C22") (pin "1") (pinfunction "1_1") (pintype "passive"))
      (node (ref "R19") (pin "1") (pinfunction "1_1") (pintype "passive"))
      (node (ref "R21") (pin "1") (pinfunction "1_1") (pintype "passive"))
      (node (ref "U3") (pin "1") (pinfunction "BI/TOUT_1") (pintype "bidirectional"))
    )
    (net (code "126") (name "Net-(U3-REG25)") (class "Default")
      (node (ref "C20") (pin "1") (pinfunction "1_1") (pintype "passive"))
      (node (ref "R19") (pin "2") (pinfunction "2_2") (pintype "passive"))
      (node (ref "U3") (pin "2") (pinfunction "REG25_2") (pintype "power_in"))
      (node (ref "U3") (pin "5") (pinfunction "VCC_5") (pintype "power_in"))
    )
    (net (code "127") (name "Net-(U3-SRN)") (class "Default")
      (node (ref "C17") (pin "1") (pinfunction "1_1") (pintype "passive"))
      (node (ref "C19") (pin "2") (pinfunction "2_2") (pintype "passive"))
      (node (ref "R18") (pin "2") (pinfunction "2_2") (pintype "passive"))
      (node (ref "U3") (pin "8") (pinfunction "SRN_8") (pintype "input"))
    )
    (net (code "128") (name "Net-(U3-SRP)") (class "Default")
      (node (ref "C17") (pin "2") (pinfunction "2_2") (pintype "passive"))
      (node (ref "C18") (pin "2") (pinfunction "2_2") (pintype "passive"))
      (node (ref "R17") (pin "2") (pinfunction "2_2") (pintype "passive"))
      (node (ref "U3") (pin "7") (pinfunction "SRP_7") (pintype "input"))
    )
    (net (code "129") (name "Net-(U3-TS)") (class "Default")
      (node (ref "C23") (pin "1") (pinfunction "1_1") (pintype "passive"))
      (node (ref "R20") (pin "1") (pinfunction "1_1") (pintype "passive"))
      (node (ref "U3") (pin "9") (pinfunction "TS_9") (pintype "input"))
    )
    (net (code "130") (name "Net-(U4-FB)") (class "Default")
      (node (ref "R25") (pin "1") (pinfunction "1_1") (pintype "passive"))
      (node (ref "R26") (pin "2") (pinfunction "2_2") (pintype "passive"))
      (node (ref "U4") (pin "5") (pinfunction "FB_5") (pintype "passive"))
    )
    (net (code "131") (name "Net-(U4-LX)") (class "Default")
      (node (ref "L3") (pin "2") (pinfunction "2_2") (pintype "passive"))
      (node (ref "U4") (pin "1") (pinfunction "LX_1") (pintype "passive"))
    )
    (net (code "132") (name "Net-(U5-FB)") (class "Default")
      (node (ref "R27") (pin "1") (pinfunction "1_1") (pintype "passive"))
      (node (ref "R28") (pin "2") (pinfunction "2_2") (pintype "passive"))
      (node (ref "U5") (pin "5") (pinfunction "FB_5") (pintype "passive"))
    )
    (net (code "133") (name "Net-(U5-LX)") (class "Default")
      (node (ref "L2") (pin "2") (pinfunction "2_2") (pintype "passive"))
      (node (ref "U5") (pin "1") (pinfunction "LX_1") (pintype "passive"))
    )
    (net (code "134") (name "Net-(U8-DISCH)") (class "Default")
      (node (ref "R38") (pin "1") (pinfunction "1_1") (pintype "passive"))
      (node (ref "U8") (pin "9") (pinfunction "DISCH_9") (pintype "bidirectional"))
    )
    (net (code "135") (name "Net-(U8-SCL)") (class "Default")
      (node (ref "R39") (pin "2") (pinfunction "2_2") (pintype "passive"))
      (node (ref "U8") (pin "7") (pinfunction "SCL_7") (pintype "input"))
      (node (ref "U9") (pin "2") (pinfunction "SCLOUT_2") (pintype "output"))
    )
    (net (code "136") (name "Net-(U8-SDA)") (class "Default")
      (node (ref "R40") (pin "2") (pinfunction "2_2") (pintype "passive"))
      (node (ref "U8") (pin "8") (pinfunction "SDA_8") (pintype "bidirectional"))
      (node (ref "U9") (pin "7") (pinfunction "SDAOUT_7") (pintype "output"))
    )
    (net (code "137") (name "Net-(U8-VBUS_EN_SNK)") (class "Default")
      (node (ref "R37") (pin "1") (pinfunction "1_1") (pintype "passive"))
      (node (ref "U8") (pin "16") (pinfunction "VBUS_EN_SNK_16") (pintype "input"))
    )
    (net (code "138") (name "Net-(U8-VBUS_VS_DISCH)") (class "Default")
      (node (ref "R35") (pin "1") (pinfunction "1_1") (pintype "passive"))
      (node (ref "U8") (pin "18") (pinfunction "VBUS_VS_DISCH_18") (pintype "input"))
    )
    (net (code "139") (name "Net-(U8-VREG_1V2)") (class "Default")
      (node (ref "C40") (pin "1") (pinfunction "1_1") (pintype "passive"))
      (node (ref "U8") (pin "21") (pinfunction "VREG_1V2_21") (pintype "power_in"))
    )
    (net (code "140") (name "Net-(U8-VREG_2V7)") (class "Default")
      (node (ref "C41") (pin "1") (pinfunction "1_1") (pintype "passive"))
      (node (ref "U8") (pin "23") (pinfunction "VREG_2V7_23") (pintype "power_in"))
    )
    (net (code "141") (name "Net-(U12-BYPASS)") (class "Default")
      (node (ref "C62") (pin "1") (pinfunction "1_1") (pintype "passive"))
      (node (ref "U12") (pin "2") (pinfunction "BYPASS_2") (pintype "input"))
      (node (ref "U12") (pin "3") (pinfunction "IN+_3") (pintype "input"))
    )
    (net (code "142") (name "Net-(U12-IN-)") (class "Default")
      (node (ref "R48") (pin "2") (pinfunction "2_2") (pintype "passive"))
      (node (ref "R49") (pin "1") (pinfunction "1_1") (pintype "passive"))
      (node (ref "U12") (pin "4") (pinfunction "IN-_4") (pintype "input"))
    )
    (net (code "143") (name "Net-(U13-BYPASS)") (class "Default")
      (node (ref "C65") (pin "1") (pinfunction "1_1") (pintype "passive"))
      (node (ref "U13") (pin "2") (pinfunction "BYPASS_2") (pintype "input"))
      (node (ref "U13") (pin "3") (pinfunction "IN+_3") (pintype "input"))
    )
    (net (code "144") (name "Net-(U13-IN-)") (class "Default")
      (node (ref "R50") (pin "2") (pinfunction "2_2") (pintype "passive"))
      (node (ref "R51") (pin "1") (pinfunction "1_1") (pintype "passive"))
      (node (ref "U13") (pin "4") (pinfunction "IN-_4") (pintype "input"))
    )
    (net (code "145") (name "Net-(U14-CPN)") (class "Default")
      (node (ref "C56") (pin "2") (pinfunction "2_2") (pintype "passive"))
      (node (ref "U14") (pin "17") (pinfunction "CPN_17") (pintype "power_in"))
    )
    (net (code "146") (name "Net-(U14-CPP)") (class "Default")
      (node (ref "C56") (pin "1") (pinfunction "1_1") (pintype "passive"))
      (node (ref "U14") (pin "18") (pinfunction "CPP_18") (pintype "power_in"))
    )
    (net (code "147") (name "Net-(U14-CPVSS)") (class "Default")
      (node (ref "C57") (pin "1") (pinfunction "1_1") (pintype "passive"))
      (node (ref "U14") (pin "15") (pinfunction "CPVSS_2_15") (pintype "power_in"))
      (node (ref "U14") (pin "16") (pinfunction "CPVSS_16") (pintype "power_in"))
    )
    (net (code "148") (name "Net-(U14-LEFTINM)") (class "Default")
      (node (ref "C50") (pin "2") (pinfunction "2_2") (pintype "passive"))
      (node (ref "U14") (pin "1") (pinfunction "LEFTINM_1") (pintype "input"))
    )
    (net (code "149") (name "Net-(U14-LEFTINP)") (class "Default")
      (node (ref "C52") (pin "2") (pinfunction "2_2") (pintype "passive"))
      (node (ref "U14") (pin "2") (pinfunction "LEFTINP_2") (pintype "input"))
    )
    (net (code "150") (name "Net-(U14-RIGHTINM)") (class "Default")
      (node (ref "C51") (pin "2") (pinfunction "2_2") (pintype "passive"))
      (node (ref "U14") (pin "5") (pinfunction "RIGHTINM_5") (pintype "input"))
    )
    (net (code "151") (name "Net-(U14-RIGHTINP)") (class "Default")
      (node (ref "C53") (pin "2") (pinfunction "2_2") (pintype "passive"))
      (node (ref "U14") (pin "4") (pinfunction "RIGHTINP_4") (pintype "input"))
    )
    (net (code "152") (name "Net-(U15-AOUTL)") (class "Default")
      (node (ref "C45") (pin "1") (pinfunction "1_1") (pintype "passive"))
      (node (ref "U15") (pin "7") (pinfunction "AOUTL_7") (pintype "output"))
    )
    (net (code "153") (name "Net-(U15-AOUTR)") (class "Default")
      (node (ref "C46") (pin "1") (pinfunction "1_1") (pintype "passive"))
      (node (ref "U15") (pin "10") (pinfunction "AOUTR_10") (pintype "output"))
    )
    (net (code "154") (name "Net-(U15-FILT+)") (class "Default")
      (node (ref "C48") (pin "+") (pinfunction "+_+") (pintype "passive"))
      (node (ref "U15") (pin "6") (pinfunction "FILT+_6") (pintype "output"))
    )
    (net (code "155") (name "Net-(U15-VQ)") (class "Default")
      (node (ref "C47") (pin "2") (pinfunction "2_2") (pintype "passive"))
      (node (ref "U15") (pin "5") (pinfunction "VQ_5") (pintype "output"))
    )
    (net (code "156") (name "Net-(U20A-RBIAS)") (class "Default")
      (node (ref "R61") (pin "2") (pinfunction "2_2") (pintype "passive"))
      (node (ref "U20") (pin "32") (pinfunction "RBIAS_32") (pintype "passive"))
    )
    (net (code "157") (name "Net-(U20A-VBUS)") (class "Default")
      (node (ref "R59") (pin "1") (pinfunction "1_1") (pintype "passive"))
      (node (ref "U20") (pin "4") (pinfunction "VBUS_4") (pintype "bidirectional"))
    )
    (net (code "158") (name "Net-(U20A-XI)") (class "Default")
      (node (ref "C80") (pin "1") (pinfunction "1_1") (pintype "passive"))
      (node (ref "R60") (pin "1") (pinfunction "1_1") (pintype "passive"))
      (node (ref "U20") (pin "28") (pinfunction "XI_28") (pintype "input"))
      (node (ref "X1") (pin "1") (pinfunction "1_1") (pintype "passive"))
    )
    (net (code "159") (name "Net-(U20A-XO)") (class "Default")
      (node (ref "C79") (pin "1") (pinfunction "1_1") (pintype "passive"))
      (node (ref "R60") (pin "2") (pinfunction "2_2") (pintype "passive"))
      (node (ref "U20") (pin "27") (pinfunction "XO_27") (pintype "output"))
      (node (ref "X1") (pin "2") (pinfunction "2_2") (pintype "passive"))
    )
    (net (code "160") (name "Net-(U20B-VDD1.8)") (class "Default")
      (node (ref "C82") (pin "1") (pinfunction "1_1") (pintype "passive"))
      (node (ref "U20") (pin "15") (pinfunction "VDD1.8_2_15") (pintype "power_in"))
      (node (ref "U20") (pin "26") (pinfunction "VDD1.8_26") (pintype "power_in"))
    )
    (net (code "161") (name "Net-(U20B-VDDA1.8)") (class "Default")
      (node (ref "C81") (pin "1") (pinfunction "1_1") (pintype "passive"))
      (node (ref "U20") (pin "29") (pinfunction "VDDA1.8_29") (pintype "power_in"))
    )
    (net (code "162") (name "Net-(U21A-O)") (class "Default")
      (node (ref "R53") (pin "2") (pinfunction "2_2") (pintype "passive"))
      (node (ref "U21") (pin "4") (pinfunction "O_4") (pintype "tri_state"))
    )
    (net (code "163") (name "Net-(U22A-PH1-OSC_OUT)") (class "Default")
      (node (ref "C83") (pin "1") (pinfunction "1_1") (pintype "passive"))
      (node (ref "U22") (pin "33") (pinfunction "PH1-OSC_OUT_33") (pintype "bidirectional"))
      (node (ref "X2") (pin "1") (pinfunction "1_1") (pintype "passive"))
    )
    (net (code "164") (name "Net-(U22B-PH0-OSC_IN)") (class "Default")
      (node (ref "C88") (pin "1") (pinfunction "1_1") (pintype "passive"))
      (node (ref "U22") (pin "32") (pinfunction "PH0-OSC_IN_32") (pintype "bidirectional"))
      (node (ref "X2") (pin "2") (pinfunction "2_2") (pintype "passive"))
    )
    (net (code "165") (name "Net-(U22D-VCAP1)") (class "Default")
      (node (ref "C110") (pin "1") (pinfunction "1_1") (pintype "passive"))
      (node (ref "C111") (pin "1") (pinfunction "1_1") (pintype "passive"))
      (node (ref "U22") (pin "148") (pinfunction "VCAP2_148") (pintype "power_in"))
      (node (ref "U22") (pin "92") (pinfunction "VCAP1_92") (pintype "power_in"))
    )
    (net (code "166") (name "POWBUS_SCL") (class "Default")
      (node (ref "R11") (pin "2") (pinfunction "2_2") (pintype "passive"))
      (node (ref "U1") (pin "12") (pinfunction "SCL_12") (pintype "input"))
      (node (ref "U16") (pin "6") (pinfunction "SCL_6") (pintype "bidirectional"))
      (node (ref "U22") (pin "195") (pinfunction "PB6_195") (pintype "bidirectional"))
      (node (ref "U3") (pin "11") (pinfunction "SCL_11") (pintype "input"))
      (node (ref "U9") (pin "3") (pinfunction "SCLIN_3") (pintype "input"))
    )
    (net (code "167") (name "POWBUS_SDA") (class "Default")
      (node (ref "R12") (pin "2") (pinfunction "2_2") (pintype "passive"))
      (node (ref "U1") (pin "11") (pinfunction "SDA_11") (pintype "bidirectional"))
      (node (ref "U16") (pin "5") (pinfunction "SDA_5") (pintype "bidirectional"))
      (node (ref "U22") (pin "196") (pinfunction "PB7_196") (pintype "bidirectional"))
      (node (ref "U3") (pin "10") (pinfunction "SDA_10") (pintype "bidirectional"))
      (node (ref "U9") (pin "6") (pinfunction "SDAIN_6") (pintype "input"))
    )
    (net (code "168") (name "RESET") (class "Default")
      (node (ref "C114") (pin "2") (pinfunction "2_2") (pintype "passive"))
      (node (ref "R64") (pin "2") (pinfunction "2_2") (pintype "passive"))
      (node (ref "S1") (pin "1") (pinfunction "S_1") (pintype "passive"))
      (node (ref "S1") (pin "2") (pinfunction "S1_2") (pintype "passive"))
      (node (ref "U22") (pin "34") (pinfunction "NRST_34") (pintype "bidirectional"))
    )
    (net (code "169") (name "SDIO_CLK") (class "Default")
      (node (ref "U18") (pin "14") (pinfunction "CLKOUT_14") (pintype "output"))
      (node (ref "U22") (pin "163") (pinfunction "PC12_163") (pintype "bidirectional"))
    )
    (net (code "170") (name "SDIO_CMD") (class "Default")
      (node (ref "U18") (pin "11") (pinfunction "CMDOUT_11") (pintype "output"))
      (node (ref "U22") (pin "166") (pinfunction "PD2_166") (pintype "bidirectional"))
    )
    (net (code "171") (name "SDIO_D0") (class "Default")
      (node (ref "U18") (pin "15") (pinfunction "DAT0OUT_15") (pintype "output"))
      (node (ref "U22") (pin "140") (pinfunction "PC8_140") (pintype "bidirectional"))
    )
    (net (code "172") (name "SDIO_D1") (class "Default")
      (node (ref "U18") (pin "16") (pinfunction "DAT1OUT_16") (pintype "output"))
      (node (ref "U22") (pin "141") (pinfunction "PC9_141") (pintype "bidirectional"))
    )
    (net (code "173") (name "SDIO_D2") (class "Default")
      (node (ref "U18") (pin "9") (pinfunction "DAT2OUT_9") (pintype "output"))
      (node (ref "U22") (pin "161") (pinfunction "PC10_161") (pintype "bidirectional"))
    )
    (net (code "174") (name "SDIO_D3") (class "Default")
      (node (ref "U18") (pin "10") (pinfunction "DAT3OUT_10") (pintype "output"))
      (node (ref "U22") (pin "162") (pinfunction "PC11_162") (pintype "bidirectional"))
    )
    (net (code "175") (name "SDIO_INSERTED") (class "Default")
      (node (ref "J2") (pin "B") (pinfunction "B_B") (pintype "bidirectional"))
      (node (ref "R58") (pin "1") (pinfunction "1_1") (pintype "passive"))
      (node (ref "U22") (pin "126") (pinfunction "PK0_126") (pintype "bidirectional"))
    )
    (net (code "176") (name "SDRAM_A0") (class "Default")
      (node (ref "U19") (pin "23") (pinfunction "A0_23") (pintype "input"))
      (node (ref "U22") (pin "16") (pinfunction "PF0_16") (pintype "bidirectional"))
    )
    (net (code "177") (name "SDRAM_A1") (class "Default")
      (node (ref "U19") (pin "24") (pinfunction "A1_24") (pintype "input"))
      (node (ref "U22") (pin "17") (pinfunction "PF1_17") (pintype "bidirectional"))
    )
    (net (code "178") (name "SDRAM_A2") (class "Default")
      (node (ref "U19") (pin "25") (pinfunction "A2_25") (pintype "input"))
      (node (ref "U22") (pin "18") (pinfunction "PF2_18") (pintype "bidirectional"))
    )
    (net (code "179") (name "SDRAM_A3") (class "Default")
      (node (ref "U19") (pin "26") (pinfunction "A3_26") (pintype "input"))
      (node (ref "U22") (pin "22") (pinfunction "PF3_22") (pintype "bidirectional"))
    )
    (net (code "180") (name "SDRAM_A4") (class "Default")
      (node (ref "U19") (pin "29") (pinfunction "A4_29") (pintype "input"))
      (node (ref "U22") (pin "23") (pinfunction "PF4_23") (pintype "bidirectional"))
    )
    (net (code "181") (name "SDRAM_A5") (class "Default")
      (node (ref "U19") (pin "30") (pinfunction "A5_30") (pintype "input"))
      (node (ref "U22") (pin "24") (pinfunction "PF5_24") (pintype "bidirectional"))
    )
    (net (code "182") (name "SDRAM_A6") (class "Default")
      (node (ref "U19") (pin "31") (pinfunction "A6_31") (pintype "input"))
      (node (ref "U22") (pin "71") (pinfunction "PF12_71") (pintype "bidirectional"))
    )
    (net (code "183") (name "SDRAM_A7") (class "Default")
      (node (ref "U19") (pin "32") (pinfunction "A7_32") (pintype "input"))
      (node (ref "U22") (pin "74") (pinfunction "PF13_74") (pintype "bidirectional"))
    )
    (net (code "184") (name "SDRAM_A8") (class "Default")
      (node (ref "U19") (pin "33") (pinfunction "A8_33") (pintype "input"))
      (node (ref "U22") (pin "75") (pinfunction "PF14_75") (pintype "bidirectional"))
    )
    (net (code "185") (name "SDRAM_A9") (class "Default")
      (node (ref "U19") (pin "34") (pinfunction "A9_34") (pintype "input"))
      (node (ref "U22") (pin "76") (pinfunction "PF15_76") (pintype "bidirectional"))
    )
    (net (code "186") (name "SDRAM_A10") (class "Default")
      (node (ref "U19") (pin "22") (pinfunction "A10_22") (pintype "input"))
      (node (ref "U22") (pin "77") (pinfunction "PG0_77") (pintype "bidirectional"))
    )
    (net (code "187") (name "SDRAM_A11") (class "Default")
      (node (ref "U19") (pin "35") (pinfunction "A11_35") (pintype "input"))
      (node (ref "U22") (pin "78") (pinfunction "PG1_78") (pintype "bidirectional"))
    )
    (net (code "188") (name "SDRAM_A12") (class "Default")
      (node (ref "U19") (pin "36") (pinfunction "A12_36") (pintype "input"))
      (node (ref "U22") (pin "129") (pinfunction "PG2_129") (pintype "bidirectional"))
    )
    (net (code "189") (name "SDRAM_BA0") (class "Default")
      (node (ref "U19") (pin "20") (pinfunction "BA0_20") (pintype "input"))
      (node (ref "U22") (pin "131") (pinfunction "PG4_131") (pintype "bidirectional"))
    )
    (net (code "190") (name "SDRAM_BA1") (class "Default")
      (node (ref "U19") (pin "21") (pinfunction "BA1_21") (pintype "input"))
      (node (ref "U22") (pin "132") (pinfunction "PG5_132") (pintype "bidirectional"))
    )
    (net (code "191") (name "SDRAM_DQ0") (class "Default")
      (node (ref "U19") (pin "2") (pinfunction "DQ0_2") (pintype "bidirectional"))
      (node (ref "U22") (pin "116") (pinfunction "PD14_116") (pintype "bidirectional"))
    )
    (net (code "192") (name "SDRAM_DQ1") (class "Default")
      (node (ref "U19") (pin "4") (pinfunction "DQ1_4") (pintype "bidirectional"))
      (node (ref "U22") (pin "117") (pinfunction "PD15_117") (pintype "bidirectional"))
    )
    (net (code "193") (name "SDRAM_DQ2") (class "Default")
      (node (ref "U19") (pin "5") (pinfunction "DQ2_5") (pintype "bidirectional"))
      (node (ref "U22") (pin "164") (pinfunction "PD0_164") (pintype "bidirectional"))
    )
    (net (code "194") (name "SDRAM_DQ3") (class "Default")
      (node (ref "U19") (pin "7") (pinfunction "DQ3_7") (pintype "bidirectional"))
      (node (ref "U22") (pin "165") (pinfunction "PD1_165") (pintype "bidirectional"))
    )
    (net (code "195") (name "SDRAM_DQ4") (class "Default")
      (node (ref "U19") (pin "8") (pinfunction "DQ4_8") (pintype "bidirectional"))
      (node (ref "U22") (pin "79") (pinfunction "PE7_79") (pintype "bidirectional"))
    )
    (net (code "196") (name "SDRAM_DQ5") (class "Default")
      (node (ref "U19") (pin "10") (pinfunction "DQ5_10") (pintype "bidirectional"))
      (node (ref "U22") (pin "80") (pinfunction "PE8_80") (pintype "bidirectional"))
    )
    (net (code "197") (name "SDRAM_DQ6") (class "Default")
      (node (ref "U19") (pin "11") (pinfunction "DQ6_11") (pintype "bidirectional"))
      (node (ref "U22") (pin "81") (pinfunction "PE9_81") (pintype "bidirectional"))
    )
    (net (code "198") (name "SDRAM_DQ7") (class "Default")
      (node (ref "U19") (pin "13") (pinfunction "DQ7_13") (pintype "bidirectional"))
      (node (ref "U22") (pin "84") (pinfunction "PE10_84") (pintype "bidirectional"))
    )
    (net (code "199") (name "SDRAM_DQ8") (class "Default")
      (node (ref "U19") (pin "42") (pinfunction "DQ8_42") (pintype "bidirectional"))
      (node (ref "U22") (pin "85") (pinfunction "PE11_85") (pintype "bidirectional"))
    )
    (net (code "200") (name "SDRAM_DQ9") (class "Default")
      (node (ref "U19") (pin "44") (pinfunction "DQ9_44") (pintype "bidirectional"))
      (node (ref "U22") (pin "86") (pinfunction "PE12_86") (pintype "bidirectional"))
    )
    (net (code "201") (name "SDRAM_DQ10") (class "Default")
      (node (ref "U19") (pin "45") (pinfunction "DQ10_45") (pintype "bidirectional"))
      (node (ref "U22") (pin "87") (pinfunction "PE13_87") (pintype "bidirectional"))
    )
    (net (code "202") (name "SDRAM_DQ11") (class "Default")
      (node (ref "U19") (pin "47") (pinfunction "DQ11_47") (pintype "bidirectional"))
      (node (ref "U22") (pin "88") (pinfunction "PE14_88") (pintype "bidirectional"))
    )
    (net (code "203") (name "SDRAM_DQ12") (class "Default")
      (node (ref "U19") (pin "48") (pinfunction "DQ12_48") (pintype "bidirectional"))
      (node (ref "U22") (pin "89") (pinfunction "PE15_89") (pintype "bidirectional"))
    )
    (net (code "204") (name "SDRAM_DQ13") (class "Default")
      (node (ref "U19") (pin "50") (pinfunction "DQ13_50") (pintype "bidirectional"))
      (node (ref "U22") (pin "108") (pinfunction "PD8_108") (pintype "bidirectional"))
    )
    (net (code "205") (name "SDRAM_DQ14") (class "Default")
      (node (ref "U19") (pin "51") (pinfunction "DQ14_51") (pintype "bidirectional"))
      (node (ref "U22") (pin "109") (pinfunction "PD9_109") (pintype "bidirectional"))
    )
    (net (code "206") (name "SDRAM_DQ15") (class "Default")
      (node (ref "U19") (pin "53") (pinfunction "DQ15_53") (pintype "bidirectional"))
      (node (ref "U22") (pin "110") (pinfunction "PD10_110") (pintype "bidirectional"))
    )
    (net (code "207") (name "SDRAM_NBL0") (class "Default")
      (node (ref "U19") (pin "15") (pinfunction "DQML_15") (pintype "bidirectional"))
      (node (ref "U22") (pin "200") (pinfunction "PE0_200") (pintype "bidirectional"))
    )
    (net (code "208") (name "SDRAM_NBL1") (class "Default")
      (node (ref "U19") (pin "39") (pinfunction "DQMH_39") (pintype "bidirectional"))
      (node (ref "U22") (pin "201") (pinfunction "PE1_201") (pintype "bidirectional"))
    )
    (net (code "209") (name "SDRAM_SDCKE") (class "Default")
      (node (ref "U19") (pin "37") (pinfunction "CKE_37") (pintype "input"))
      (node (ref "U22") (pin "46") (pinfunction "PH2_46") (pintype "bidirectional"))
    )
    (net (code "210") (name "SDRAM_SDCLK") (class "Default")
      (node (ref "U19") (pin "38") (pinfunction "CLK_38") (pintype "input"))
      (node (ref "U22") (pin "135") (pinfunction "PG8_135") (pintype "bidirectional"))
    )
    (net (code "211") (name "SDRAM_SDNCAS") (class "Default")
      (node (ref "U19") (pin "17") (pinfunction "~{CAS}_17") (pintype "input"))
      (node (ref "U22") (pin "191") (pinfunction "PG15_191") (pintype "bidirectional"))
    )
    (net (code "212") (name "SDRAM_SDNE") (class "Default")
      (node (ref "R52") (pin "1") (pinfunction "1_1") (pintype "passive"))
      (node (ref "U19") (pin "19") (pinfunction "~{CS}_19") (pintype "input"))
      (node (ref "U22") (pin "37") (pinfunction "PC2_C_37") (pintype "bidirectional"))
    )
    (net (code "213") (name "SDRAM_SDNRAS") (class "Default")
      (node (ref "U19") (pin "18") (pinfunction "~{RAS}_18") (pintype "input"))
      (node (ref "U22") (pin "70") (pinfunction "PF11_70") (pintype "bidirectional"))
    )
    (net (code "214") (name "SDRAM_SDNWE") (class "Default")
      (node (ref "U19") (pin "16") (pinfunction "~{WE}_16") (pintype "input"))
      (node (ref "U22") (pin "49") (pinfunction "PH5_49") (pintype "bidirectional"))
    )
    (net (code "215") (name "SPK_SD") (class "Default")
      (node (ref "U11") (pin "13") (pinfunction "O2_13") (pintype "passive"))
      (node (ref "U12") (pin "1") (pinfunction "SHUTDOWN_1") (pintype "input"))
      (node (ref "U13") (pin "1") (pinfunction "SHUTDOWN_1") (pintype "input"))
    )
    (net (code "216") (name "SPOUT_L_N") (class "Default")
      (node (ref "J8") (pin "2") (pinfunction "2_2") (pintype "passive"))
      (node (ref "U12") (pin "8") (pinfunction "VO2_8") (pintype "output"))
    )
    (net (code "217") (name "SPOUT_L_P") (class "Default")
      (node (ref "J8") (pin "1") (pinfunction "1_1") (pintype "passive"))
      (node (ref "R49") (pin "2") (pinfunction "2_2") (pintype "passive"))
      (node (ref "U12") (pin "5") (pinfunction "VO1_5") (pintype "output"))
    )
    (net (code "218") (name "SPOUT_R_N") (class "Default")
      (node (ref "J9") (pin "2") (pinfunction "2_2") (pintype "passive"))
      (node (ref "U13") (pin "8") (pinfunction "VO2_8") (pintype "output"))
    )
    (net (code "219") (name "SPOUT_R_P") (class "Default")
      (node (ref "J9") (pin "1") (pinfunction "1_1") (pintype "passive"))
      (node (ref "R51") (pin "2") (pinfunction "2_2") (pintype "passive"))
      (node (ref "U13") (pin "5") (pinfunction "VO1_5") (pintype "output"))
    )
    (net (code "220") (name "SWCLK") (class "Default")
      (node (ref "JP2") (pin "2") (pinfunction "2_2") (pintype "passive"))
      (node (ref "U22") (pin "159") (pinfunction "PA14_159") (pintype "bidirectional"))
    )
    (net (code "221") (name "SWDIO") (class "Default")
      (node (ref "JP2") (pin "4") (pinfunction "4_4") (pintype "passive"))
      (node (ref "U22") (pin "147") (pinfunction "PA13_147") (pintype "bidirectional"))
    )
    (net (code "222") (name "TOUCH_CS") (class "Default")
      (node (ref "JP1") (pin "6") (pinfunction "6_6") (pintype "passive"))
      (node (ref "U22") (pin "160") (pinfunction "PA15_160") (pintype "bidirectional"))
    )
    (net (code "223") (name "TOUCH_IRQ") (class "Default")
      (node (ref "JP1") (pin "1") (pinfunction "1_1") (pintype "passive"))
      (node (ref "U22") (pin "156") (pinfunction "PI2_156") (pintype "bidirectional"))
    )
    (net (code "224") (name "TOUCH_MISO") (class "Default")
      (node (ref "JP1") (pin "4") (pinfunction "4_4") (pintype "passive"))
      (node (ref "U22") (pin "178") (pinfunction "PG9_178") (pintype "bidirectional"))
    )
    (net (code "225") (name "TOUCH_MOSI") (class "Default")
      (node (ref "JP1") (pin "3") (pinfunction "3_3") (pintype "passive"))
      (node (ref "U22") (pin "173") (pinfunction "PD7_173") (pintype "bidirectional"))
    )
    (net (code "226") (name "TOUCH_SCK") (class "Default")
      (node (ref "JP1") (pin "5") (pinfunction "5_5") (pintype "passive"))
      (node (ref "U22") (pin "180") (pinfunction "PG11_180") (pintype "bidirectional"))
    )
    (net (code "227") (name "USBIN_D_N") (class "Default")
      (node (ref "D4") (pin "1") (pinfunction "P$1_1") (pintype "bidirectional"))
      (node (ref "J1") (pin "A7") (pinfunction "D1-_A7") (pintype "passive"))
      (node (ref "J1") (pin "B7") (pinfunction "D2-_B7") (pintype "passive"))
      (node (ref "U22") (pin "145") (pinfunction "PA11_145") (pintype "bidirectional"))
    )
    (net (code "228") (name "USBIN_D_P") (class "Default")
      (node (ref "D4") (pin "2") (pinfunction "P$2_2") (pintype "bidirectional"))
      (node (ref "J1") (pin "A6") (pinfunction "D1+_A6") (pintype "passive"))
      (node (ref "J1") (pin "B6") (pinfunction "D2+_B6") (pintype "passive"))
      (node (ref "U22") (pin "146") (pinfunction "PA12_146") (pintype "bidirectional"))
    )
    (net (code "229") (name "USBOUT_CLK") (class "Default")
      (node (ref "U20") (pin "14") (pinfunction "CLKOUT_14") (pintype "output"))
      (node (ref "U22") (pin "54") (pinfunction "PA5_54") (pintype "bidirectional"))
    )
    (net (code "230") (name "USBOUT_D0") (class "Default")
      (node (ref "U20") (pin "24") (pinfunction "DATA0_24") (pintype "bidirectional"))
      (node (ref "U22") (pin "50") (pinfunction "PA3_50") (pintype "bidirectional"))
    )
    (net (code "231") (name "USBOUT_D1") (class "Default")
      (node (ref "U20") (pin "23") (pinfunction "DATA1_23") (pintype "bidirectional"))
      (node (ref "U22") (pin "61") (pinfunction "PB0_61") (pintype "bidirectional"))
    )
    (net (code "232") (name "USBOUT_D2") (class "Default")
      (node (ref "U20") (pin "22") (pinfunction "DATA2_22") (pintype "bidirectional"))
      (node (ref "U22") (pin "62") (pinfunction "PB1_62") (pintype "bidirectional"))
    )
    (net (code "233") (name "USBOUT_D3") (class "Default")
      (node (ref "U20") (pin "21") (pinfunction "DATA3_21") (pintype "bidirectional"))
      (node (ref "U22") (pin "90") (pinfunction "PB10_90") (pintype "bidirectional"))
    )
    (net (code "234") (name "USBOUT_D4") (class "Default")
      (node (ref "U20") (pin "20") (pinfunction "DATA4_20") (pintype "bidirectional"))
      (node (ref "U22") (pin "91") (pinfunction "PB11_91") (pintype "bidirectional"))
    )
    (net (code "235") (name "USBOUT_D5") (class "Default")
      (node (ref "U20") (pin "19") (pinfunction "DATA5_19") (pintype "bidirectional"))
      (node (ref "U22") (pin "104") (pinfunction "PB12_104") (pintype "bidirectional"))
    )
    (net (code "236") (name "USBOUT_D6") (class "Default")
      (node (ref "U20") (pin "18") (pinfunction "DATA6_18") (pintype "bidirectional"))
      (node (ref "U22") (pin "105") (pinfunction "PB13_105") (pintype "bidirectional"))
    )
    (net (code "237") (name "USBOUT_D7") (class "Default")
      (node (ref "U20") (pin "17") (pinfunction "DATA7_17") (pintype "bidirectional"))
      (node (ref "U22") (pin "194") (pinfunction "PB5_194") (pintype "bidirectional"))
    )
    (net (code "238") (name "USBOUT_DIR") (class "Default")
      (node (ref "U20") (pin "12") (pinfunction "DIR_12") (pintype "output"))
      (node (ref "U22") (pin "13") (pinfunction "PI11_13") (pintype "bidirectional"))
    )
    (net (code "239") (name "USBOUT_D_N") (class "Default")
      (node (ref "J3") (pin "2") (pinfunction "D-_2") (pintype "passive"))
      (node (ref "U20") (pin "8") (pinfunction "DM_8") (pintype "bidirectional"))
    )
    (net (code "240") (name "USBOUT_D_P") (class "Default")
      (node (ref "J3") (pin "3") (pinfunction "D+_3") (pintype "passive"))
      (node (ref "U20") (pin "7") (pinfunction "DP_7") (pintype "bidirectional"))
    )
    (net (code "241") (name "USBOUT_NXT") (class "Default")
      (node (ref "U20") (pin "11") (pinfunction "NXT_11") (pintype "output"))
      (node (ref "U22") (pin "38") (pinfunction "PC3_C_38") (pintype "bidirectional"))
    )
    (net (code "242") (name "USBOUT_STP") (class "Default")
      (node (ref "U20") (pin "13") (pinfunction "STP_13") (pintype "input"))
      (node (ref "U22") (pin "35") (pinfunction "PC0_35") (pintype "bidirectional"))
    )
    (net (code "243") (name "VAMP") (class "Default")
      (node (ref "C31") (pin "1") (pinfunction "1_1") (pintype "passive"))
      (node (ref "C34") (pin "1") (pinfunction "1_1") (pintype "passive"))
      (node (ref "C60") (pin "+") (pinfunction "+_+") (pintype "passive"))
      (node (ref "C61") (pin "1") (pinfunction "1_1") (pintype "passive"))
      (node (ref "C63") (pin "+") (pinfunction "+_+") (pintype "passive"))
      (node (ref "C64") (pin "1") (pinfunction "1_1") (pintype "passive"))
      (node (ref "R27") (pin "2") (pinfunction "2_2") (pintype "passive"))
      (node (ref "U12") (pin "6") (pinfunction "VDD_6") (pintype "power_in"))
      (node (ref "U13") (pin "6") (pinfunction "VDD_6") (pintype "power_in"))
      (node (ref "U5") (pin "7") (pinfunction "OUT_7") (pintype "output"))
    )
    (net (code "244") (name "VBAT_IN") (class "Default")
      (node (ref "C21") (pin "1") (pinfunction "1_1") (pintype "passive"))
      (node (ref "C8") (pin "1") (pinfunction "1_1") (pintype "passive"))
      (node (ref "D2") (pin "1") (pinfunction "A_1") (pintype "passive"))
      (node (ref "J6") (pin "3") (pinfunction "S_3") (pintype "passive"))
      (node (ref "Q3") (pin "1") (pinfunction "S_1") (pintype "bidirectional"))
      (node (ref "Q3") (pin "2") (pinfunction "S_2") (pintype "bidirectional"))
      (node (ref "Q3") (pin "3") (pinfunction "S_3") (pintype "bidirectional"))
      (node (ref "R14") (pin "1") (pinfunction "1_1") (pintype "passive"))
      (node (ref "R7") (pin "2") (pinfunction "2_2") (pintype "passive"))
      (node (ref "TP2") (pin "P$1") (pinfunction "1_P$1") (pintype "bidirectional"))
      (node (ref "U1") (pin "13") (pinfunction "CMPIN_13") (pintype "input"))
      (node (ref "U3") (pin "4") (pinfunction "BAT_4") (pintype "input"))
    )
    (net (code "245") (name "VBAT_OUT") (class "Default")
      (node (ref "J6") (pin "1") (pinfunction "S_1") (pintype "passive"))
      (node (ref "R16") (pin "1") (pinfunction "1_1") (pintype "passive"))
      (node (ref "R17") (pin "1") (pinfunction "1_1") (pintype "passive"))
    )
    (net (code "246") (name "VBUS_IN") (class "Default")
      (node (ref "C7") (pin "1") (pinfunction "1_1") (pintype "passive"))
      (node (ref "D1") (pin "1") (pinfunction "A_1") (pintype "passive"))
      (node (ref "Q1") (pin "5") (pinfunction "D_5") (pintype "bidirectional"))
      (node (ref "Q1") (pin "6") (pinfunction "D_6") (pintype "bidirectional"))
      (node (ref "Q1") (pin "7") (pinfunction "D_7") (pintype "bidirectional"))
      (node (ref "Q1") (pin "8") (pinfunction "D_8") (pintype "bidirectional"))
      (node (ref "Q6") (pin "5") (pinfunction "D_5") (pintype "bidirectional"))
      (node (ref "Q6") (pin "6") (pinfunction "D_6") (pintype "bidirectional"))
      (node (ref "Q6") (pin "7") (pinfunction "D_7") (pintype "bidirectional"))
      (node (ref "Q6") (pin "8") (pinfunction "D_8") (pintype "bidirectional"))
      (node (ref "R3") (pin "2") (pinfunction "2_2") (pintype "passive"))
      (node (ref "R38") (pin "2") (pinfunction "2_2") (pintype "passive"))
    )
    (net (code "247") (name "VBUS_OUT") (class "Default")
      (node (ref "C37") (pin "1") (pinfunction "1_1") (pintype "passive"))
      (node (ref "J3") (pin "1") (pinfunction "5V_1") (pintype "passive"))
      (node (ref "R59") (pin "2") (pinfunction "2_2") (pintype "passive"))
      (node (ref "U6") (pin "1") (pinfunction "OUT_1") (pintype "power_in"))
    )
    (net (code "248") (name "VDD") (class "Default")
      (node (ref "C100") (pin "1") (pinfunction "1_1") (pintype "passive"))
      (node (ref "C101") (pin "1") (pinfunction "1_1") (pintype "passive"))
      (node (ref "C102") (pin "1") (pinfunction "1_1") (pintype "passive"))
      (node (ref "C103") (pin "1") (pinfunction "1_1") (pintype "passive"))
      (node (ref "C104") (pin "1") (pinfunction "1_1") (pintype "passive"))
      (node (ref "C105") (pin "1") (pinfunction "1_1") (pintype "passive"))
      (node (ref "C106") (pin "1") (pinfunction "1_1") (pintype "passive"))
      (node (ref "C107") (pin "1") (pinfunction "1_1") (pintype "passive"))
      (node (ref "C108") (pin "1") (pinfunction "1_1") (pintype "passive"))
      (node (ref "C109") (pin "1") (pinfunction "1_1") (pintype "passive"))
      (node (ref "C25") (pin "1") (pinfunction "1_1") (pintype "passive"))
      (node (ref "C42") (pin "1") (pinfunction "1_1") (pintype "passive"))
      (node (ref "C44") (pin "1") (pinfunction "1_1") (pintype "passive"))
      (node (ref "C49") (pin "1") (pinfunction "1_1") (pintype "passive"))
      (node (ref "C54") (pin "1") (pinfunction "1_1") (pintype "passive"))
      (node (ref "C55") (pin "1") (pinfunction "1_1") (pintype "passive"))
      (node (ref "C58") (pin "1") (pinfunction "1_1") (pintype "passive"))
      (node (ref "C77") (pin "1") (pinfunction "1_1") (pintype "passive"))
      (node (ref "C84") (pin "1") (pinfunction "1_1") (pintype "passive"))
      (node (ref "C85") (pin "1") (pinfunction "1_1") (pintype "passive"))
      (node (ref "C86") (pin "1") (pinfunction "1_1") (pintype "passive"))
      (node (ref "C87") (pin "1") (pinfunction "1_1") (pintype "passive"))
      (node (ref "C91") (pin "2") (pinfunction "2_2") (pintype "passive"))
      (node (ref "C92") (pin "1") (pinfunction "1_1") (pintype "passive"))
      (node (ref "C93") (pin "1") (pinfunction "1_1") (pintype "passive"))
      (node (ref "C94") (pin "1") (pinfunction "1_1") (pintype "passive"))
      (node (ref "C95") (pin "1") (pinfunction "1_1") (pintype "passive"))
      (node (ref "C96") (pin "1") (pinfunction "1_1") (pintype "passive"))
      (node (ref "C97") (pin "1") (pinfunction "1_1") (pintype "passive"))
      (node (ref "C98") (pin "1") (pinfunction "1_1") (pintype "passive"))
      (node (ref "C99") (pin "1") (pinfunction "1_1") (pintype "passive"))
      (node (ref "J7") (pin "6") (pinfunction "6_6") (pintype "passive"))
      (node (ref "JP2") (pin "1") (pinfunction "1_1") (pintype "passive"))
      (node (ref "JP3") (pin "4") (pinfunction "4_4") (pintype "passive"))
      (node (ref "L4") (pin "1") (pinfunction "1_1") (pintype "passive"))
      (node (ref "R10") (pin "1") (pinfunction "1_1") (pintype "passive"))
      (node (ref "R11") (pin "1") (pinfunction "1_1") (pintype "passive"))
      (node (ref "R12") (pin "1") (pinfunction "1_1") (pintype "passive"))
      (node (ref "R13") (pin "1") (pinfunction "1_1") (pintype "passive"))
      (node (ref "R15") (pin "1") (pinfunction "1_1") (pintype "passive"))
      (node (ref "R22") (pin "1") (pinfunction "1_1") (pintype "passive"))
      (node (ref "R24") (pin "2") (pinfunction "2_2") (pintype "passive"))
      (node (ref "R31") (pin "1") (pinfunction "1_1") (pintype "passive"))
      (node (ref "R32") (pin "1") (pinfunction "1_1") (pintype "passive"))
      (node (ref "R39") (pin "1") (pinfunction "1_1") (pintype "passive"))
      (node (ref "R40") (pin "1") (pinfunction "1_1") (pintype "passive"))
      (node (ref "R41") (pin "1") (pinfunction "1_1") (pintype "passive"))
      (node (ref "R46") (pin "1") (pinfunction "1_1") (pintype "passive"))
      (node (ref "R47") (pin "1") (pinfunction "1_1") (pintype "passive"))
      (node (ref "R54") (pin "2") (pinfunction "2_2") (pintype "passive"))
      (node (ref "R55") (pin "2") (pinfunction "2_2") (pintype "passive"))
      (node (ref "R58") (pin "2") (pinfunction "2_2") (pintype "passive"))
      (node (ref "R64") (pin "1") (pinfunction "1_1") (pintype "passive"))
      (node (ref "R77") (pin "1") (pinfunction "1_1") (pintype "passive"))
      (node (ref "TP6") (pin "P$1") (pinfunction "1_P$1") (pintype "bidirectional"))
      (node (ref "U10") (pin "4") (pinfunction "VIN_2_4") (pintype "input"))
      (node (ref "U10") (pin "6") (pinfunction "VIN_6") (pintype "input"))
      (node (ref "U11") (pin "5") (pinfunction "VDD_5") (pintype "power_in"))
      (node (ref "U14") (pin "12") (pinfunction "VDD_2_12") (pintype "power_in"))
      (node (ref "U14") (pin "20") (pinfunction "VDD_20") (pintype "power_in"))
      (node (ref "U15") (pin "9") (pinfunction "VA_9") (pintype "power_in"))
      (node (ref "U16") (pin "1") (pinfunction "E0_1") (pintype "bidirectional"))
      (node (ref "U16") (pin "8") (pinfunction "VCC_8") (pintype "power_in"))
      (node (ref "U2") (pin "3") (pinfunction "VO_3") (pintype "passive"))
      (node (ref "U20") (pin "16") (pinfunction "VDD3.3_3_16") (pintype "power_in"))
      (node (ref "U20") (pin "25") (pinfunction "VDD3.3_4_25") (pintype "power_in"))
      (node (ref "U20") (pin "30") (pinfunction "VDD3.3_30") (pintype "power_in"))
      (node (ref "U20") (pin "31") (pinfunction "REG_EN_31") (pintype "bidirectional"))
      (node (ref "U20") (pin "6") (pinfunction "VDD3.3_2_6") (pintype "power_in"))
      (node (ref "U21") (pin "5") (pinfunction "VCC_5") (pintype "power_in"))
      (node (ref "U22") (pin "103") (pinfunction "VDD_10_103") (pintype "power_in"))
      (node (ref "U22") (pin "115") (pinfunction "VDD_11_115") (pintype "power_in"))
      (node (ref "U22") (pin "124") (pinfunction "VDD_12_124") (pintype "power_in"))
      (node (ref "U22") (pin "137") (pinfunction "VDD33USB_137") (pintype "power_in"))
      (node (ref "U22") (pin "15") (pinfunction "VDD_2_15") (pintype "power_in"))
      (node (ref "U22") (pin "150") (pinfunction "VDD_13_150") (pintype "power_in"))
      (node (ref "U22") (pin "158") (pinfunction "VDD_14_158") (pintype "power_in"))
      (node (ref "U22") (pin "171") (pinfunction "VDD_15_171") (pintype "power_in"))
      (node (ref "U22") (pin "185") (pinfunction "VDD_16_185") (pintype "power_in"))
      (node (ref "U22") (pin "203") (pinfunction "PDR_ON_203") (pintype "passive"))
      (node (ref "U22") (pin "204") (pinfunction "VDD_204") (pintype "power_in"))
      (node (ref "U22") (pin "26") (pinfunction "VDD_3_26") (pintype "power_in"))
      (node (ref "U22") (pin "39") (pinfunction "VDD_4_39") (pintype "power_in"))
      (node (ref "U22") (pin "52") (pinfunction "VDD_5_52") (pintype "power_in"))
      (node (ref "U22") (pin "59") (pinfunction "VDD_6_59") (pintype "power_in"))
      (node (ref "U22") (pin "6") (pinfunction "VBAT_6") (pintype "power_in"))
      (node (ref "U22") (pin "73") (pinfunction "VDD_7_73") (pintype "power_in"))
      (node (ref "U22") (pin "83") (pinfunction "VDD_8_83") (pintype "power_in"))
      (node (ref "U22") (pin "94") (pinfunction "VDD_9_94") (pintype "power_in"))
      (node (ref "U7") (pin "5") (pinfunction "IN_5") (pintype "power_in"))
      (node (ref "U9") (pin "8") (pinfunction "VCC_8") (pintype "power_in"))
      (node (ref "VR1") (pin "3") (pinfunction "E_3") (pintype "passive"))
      (node (ref "VR2") (pin "3") (pinfunction "E_3") (pintype "passive"))
      (node (ref "VR3") (pin "3") (pinfunction "E_3") (pintype "passive"))
      (node (ref "VR4") (pin "3") (pinfunction "E_3") (pintype "passive"))
    )
    (net (code "249") (name "VDDA") (class "Default")
      (node (ref "C112") (pin "2") (pinfunction "2_2") (pintype "passive"))
      (node (ref "C113") (pin "2") (pinfunction "2_2") (pintype "passive"))
      (node (ref "C89") (pin "1") (pinfunction "1_1") (pintype "passive"))
      (node (ref "C90") (pin "1") (pinfunction "1_1") (pintype "passive"))
      (node (ref "L4") (pin "2") (pinfunction "2_2") (pintype "passive"))
      (node (ref "U22") (pin "41") (pinfunction "VREF+_41") (pintype "power_in"))
      (node (ref "U22") (pin "42") (pinfunction "VDDA_42") (pintype "power_in"))
    )
    (net (code "250") (name "VMEM") (class "Default")
      (node (ref "C43") (pin "1") (pinfunction "1_1") (pintype "passive"))
      (node (ref "C67") (pin "1") (pinfunction "1_1") (pintype "passive"))
      (node (ref "C68") (pin "1") (pinfunction "1_1") (pintype "passive"))
      (node (ref "C69") (pin "1") (pinfunction "1_1") (pintype "passive"))
      (node (ref "C70") (pin "+") (pinfunction "+_+") (pintype "passive"))
      (node (ref "C71") (pin "1") (pinfunction "1_1") (pintype "passive"))
      (node (ref "C72") (pin "1") (pinfunction "1_1") (pintype "passive"))
      (node (ref "C73") (pin "1") (pinfunction "1_1") (pintype "passive"))
      (node (ref "C74") (pin "1") (pinfunction "1_1") (pintype "passive"))
      (node (ref "C75") (pin "1") (pinfunction "1_1") (pintype "passive"))
      (node (ref "C76") (pin "1") (pinfunction "1_1") (pintype "passive"))
      (node (ref "R30") (pin "2") (pinfunction "2_2") (pintype "passive"))
      (node (ref "R52") (pin "2") (pinfunction "2_2") (pintype "passive"))
      (node (ref "U10") (pin "1") (pinfunction "VOUT_1") (pintype "output"))
      (node (ref "U17") (pin "8") (pinfunction "VCC_8") (pintype "power_in"))
      (node (ref "U19") (pin "1") (pinfunction "VDD_1") (pintype "power_in"))
      (node (ref "U19") (pin "14") (pinfunction "VDD_14") (pintype "power_in"))
      (node (ref "U19") (pin "27") (pinfunction "VDD_27") (pintype "power_in"))
      (node (ref "U19") (pin "3") (pinfunction "VDDQ_3") (pintype "power_in"))
      (node (ref "U19") (pin "43") (pinfunction "VDDQ_43") (pintype "power_in"))
      (node (ref "U19") (pin "49") (pinfunction "VDDQ_49") (pintype "power_in"))
      (node (ref "U19") (pin "9") (pinfunction "VDDQ_9") (pintype "power_in"))
    )
    (net (code "251") (name "VOLUME") (class "Default")
      (node (ref "U22") (pin "58") (pinfunction "PC5_58") (pintype "bidirectional"))
      (node (ref "VR3") (pin "2") (pinfunction "S_2") (pintype "passive"))
    )
    (net (code "252") (name "VREG_5V_EN") (class "Default")
      (node (ref "R29") (pin "2") (pinfunction "2_2") (pintype "passive"))
      (node (ref "U22") (pin "8") (pinfunction "PC13_8") (pintype "bidirectional"))
      (node (ref "U4") (pin "2") (pinfunction "EN_2") (pintype "passive"))
      (node (ref "U5") (pin "2") (pinfunction "EN_2") (pintype "passive"))
    )
    (net (code "253") (name "VSD") (class "Default")
      (node (ref "C38") (pin "1") (pinfunction "1_1") (pintype "passive"))
      (node (ref "J2") (pin "4") (pinfunction "VCC_4") (pintype "bidirectional"))
      (node (ref "R57") (pin "2") (pinfunction "2_2") (pintype "passive"))
      (node (ref "U18") (pin "13") (pinfunction "RUP3_13") (pintype "output"))
      (node (ref "U18") (pin "4") (pinfunction "RUP1_4") (pintype "input"))
      (node (ref "U18") (pin "5") (pinfunction "VDD_5") (pintype "power_in"))
      (node (ref "U7") (pin "1") (pinfunction "OUT_1") (pintype "power_in"))
    )
    (net (code "254") (name "VSW_MEM_EN") (class "Default")
      (node (ref "R41") (pin "2") (pinfunction "2_2") (pintype "passive"))
      (node (ref "U10") (pin "3") (pinfunction "ON_3") (pintype "input"))
      (node (ref "U22") (pin "9") (pinfunction "PC14-OSC32_IN_9") (pintype "bidirectional"))
    )
    (net (code "255") (name "VSW_SD_EN") (class "Default")
      (node (ref "R32") (pin "2") (pinfunction "2_2") (pintype "passive"))
      (node (ref "U22") (pin "5") (pinfunction "PE6_5") (pintype "bidirectional"))
      (node (ref "U7") (pin "4") (pinfunction "EN_4") (pintype "output"))
    )
    (net (code "256") (name "VSW_SD_FAULT") (class "Default")
      (node (ref "R34") (pin "2") (pinfunction "2_2") (pintype "passive"))
      (node (ref "U22") (pin "157") (pinfunction "PI3_157") (pintype "bidirectional"))
      (node (ref "U7") (pin "3") (pinfunction "FAULT_3") (pintype "output"))
    )
    (net (code "257") (name "VSW_USB_EN") (class "Default")
      (node (ref "R31") (pin "2") (pinfunction "2_2") (pintype "passive"))
      (node (ref "U20") (pin "3") (pinfunction "CPEN_3") (pintype "output"))
      (node (ref "U6") (pin "4") (pinfunction "EN_4") (pintype "output"))
    )
    (net (code "258") (name "VSW_USB_FAULT") (class "Default")
      (node (ref "R33") (pin "2") (pinfunction "2_2") (pintype "passive"))
      (node (ref "U20") (pin "10") (pinfunction "EXTVBUS_10") (pintype "input"))
      (node (ref "U6") (pin "3") (pinfunction "FAULT_3") (pintype "output"))
    )
    (net (code "259") (name "VSYS") (class "Default")
      (node (ref "C10") (pin "1") (pinfunction "1_1") (pintype "passive"))
      (node (ref "C11") (pin "1") (pinfunction "1_1") (pintype "passive"))
      (node (ref "C13") (pin "2") (pinfunction "2_2") (pintype "passive"))
      (node (ref "C24") (pin "1") (pinfunction "1_1") (pintype "passive"))
      (node (ref "C26") (pin "1") (pinfunction "1_1") (pintype "passive"))
      (node (ref "C27") (pin "2") (pinfunction "2_2") (pintype "passive"))
      (node (ref "C28") (pin "2") (pinfunction "2_2") (pintype "passive"))
      (node (ref "C29") (pin "2") (pinfunction "2_2") (pintype "passive"))
      (node (ref "C30") (pin "+") (pinfunction "+_+") (pintype "passive"))
      (node (ref "C35") (pin "1") (pinfunction "1_1") (pintype "passive"))
      (node (ref "C36") (pin "1") (pinfunction "1_1") (pintype "passive"))
      (node (ref "L1") (pin "2") (pinfunction "2_2") (pintype "passive"))
      (node (ref "L2") (pin "1") (pinfunction "1_1") (pintype "passive"))
      (node (ref "L3") (pin "1") (pinfunction "1_1") (pintype "passive"))
      (node (ref "R29") (pin "1") (pinfunction "1_1") (pintype "passive"))
      (node (ref "R9") (pin "1") (pinfunction "1_1") (pintype "passive"))
      (node (ref "TP7") (pin "P$1") (pinfunction "1_P$1") (pintype "bidirectional"))
      (node (ref "U1") (pin "20") (pinfunction "SRP_20") (pintype "input"))
      (node (ref "U2") (pin "1") (pinfunction "VI_1") (pintype "passive"))
      (node (ref "U3") (pin "3") (pinfunction "REGIN_3") (pintype "power_in"))
      (node (ref "U4") (pin "3") (pinfunction "VIN_3") (pintype "input"))
      (node (ref "U5") (pin "3") (pinfunction "VIN_3") (pintype "input"))
    )
    (net (code "260") (name "WAKEUP") (class "Default")
      (node (ref "C116") (pin "2") (pinfunction "2_2") (pintype "passive"))
      (node (ref "R77") (pin "2") (pinfunction "2_2") (pintype "passive"))
      (node (ref "S25") (pin "3") (pinfunction "2_3") (pintype "passive"))
      (node (ref "U22") (pin "43") (pinfunction "PA0-WKUP_43") (pintype "bidirectional"))
    )
    (net (code "261") (name "unconnected-(J1-RX1+-PadB11)") (class "Default")
      (node (ref "J1") (pin "B11") (pinfunction "RX1+_B11") (pintype "passive"))
    )
    (net (code "262") (name "unconnected-(J1-RX1--PadB10)") (class "Default")
      (node (ref "J1") (pin "B10") (pinfunction "RX1-_B10") (pintype "passive"))
    )
    (net (code "263") (name "unconnected-(J1-RX2+-PadA11)") (class "Default")
      (node (ref "J1") (pin "A11") (pinfunction "RX2+_A11") (pintype "passive"))
    )
    (net (code "264") (name "unconnected-(J1-RX2--PadA10)") (class "Default")
      (node (ref "J1") (pin "A10") (pinfunction "RX2-_A10") (pintype "passive"))
    )
    (net (code "265") (name "unconnected-(J1-SBU1-PadA8)") (class "Default")
      (node (ref "J1") (pin "A8") (pinfunction "SBU1_A8") (pintype "passive"))
    )
    (net (code "266") (name "unconnected-(J1-SBU2-PadB8)") (class "Default")
      (node (ref "J1") (pin "B8") (pinfunction "SBU2_B8") (pintype "passive"))
    )
    (net (code "267") (name "unconnected-(J1-TX1+-PadA2)") (class "Default")
      (node (ref "J1") (pin "A2") (pinfunction "TX1+_A2") (pintype "passive"))
    )
    (net (code "268") (name "unconnected-(J1-TX1--PadA3)") (class "Default")
      (node (ref "J1") (pin "A3") (pinfunction "TX1-_A3") (pintype "passive"))
    )
    (net (code "269") (name "unconnected-(J1-TX2+-PadB2)") (class "Default")
      (node (ref "J1") (pin "B2") (pinfunction "TX2+_B2") (pintype "passive"))
    )
    (net (code "270") (name "unconnected-(J1-TX2--PadB3)") (class "Default")
      (node (ref "J1") (pin "B3") (pinfunction "TX2-_B3") (pintype "passive"))
    )
    (net (code "271") (name "unconnected-(J4-Pad1)") (class "Default")
      (node (ref "J4") (pin "1") (pinfunction "1_1") (pintype "bidirectional"))
    )
    (net (code "272") (name "unconnected-(J4-Pad3)") (class "Default")
      (node (ref "J4") (pin "3") (pinfunction "3_3") (pintype "bidirectional"))
    )
    (net (code "273") (name "unconnected-(J5-Pad1)") (class "Default")
      (node (ref "J5") (pin "1") (pinfunction "1_1") (pintype "bidirectional"))
    )
    (net (code "274") (name "unconnected-(J5-Pad3)") (class "Default")
      (node (ref "J5") (pin "3") (pinfunction "3_3") (pintype "bidirectional"))
    )
    (net (code "275") (name "unconnected-(JP1-Pad9)") (class "Default")
      (node (ref "JP1") (pin "9") (pinfunction "9_9") (pintype "passive"))
    )
    (net (code "276") (name "unconnected-(JP1-Pad10)") (class "Default")
      (node (ref "JP1") (pin "10") (pinfunction "10_10") (pintype "passive"))
    )
    (net (code "277") (name "unconnected-(JP1-Pad38)") (class "Default")
      (node (ref "JP1") (pin "38") (pinfunction "38_38") (pintype "passive"))
    )
    (net (code "278") (name "unconnected-(U1-IADP-Pad7)") (class "Default")
      (node (ref "U1") (pin "7") (pinfunction "IADP_7") (pintype "output"))
    )
    (net (code "279") (name "unconnected-(U1-IBAT-Pad8)") (class "Default")
      (node (ref "U1") (pin "8") (pinfunction "IBAT_8") (pintype "output"))
    )
    (net (code "280") (name "unconnected-(U1-PMON-Pad9)") (class "Default")
      (node (ref "U1") (pin "9") (pinfunction "PMON_9") (pintype "output"))
    )
    (net (code "281") (name "unconnected-(U4-RSET-Pad6)") (class "Default")
      (node (ref "U4") (pin "6") (pinfunction "RSET_6") (pintype "passive"))
    )
    (net (code "282") (name "unconnected-(U5-RSET-Pad6)") (class "Default")
      (node (ref "U5") (pin "6") (pinfunction "RSET_6") (pintype "passive"))
    )
    (net (code "283") (name "unconnected-(U8-ALERT-Pad19)") (class "Default")
      (node (ref "U8") (pin "19") (pinfunction "ALERT_19") (pintype "output"))
    )
    (net (code "284") (name "unconnected-(U8-ATTACH-Pad11)") (class "Default")
      (node (ref "U8") (pin "11") (pinfunction "ATTACH_11") (pintype "output"))
    )
    (net (code "285") (name "unconnected-(U8-A_B_SIDE-Pad17)") (class "Default")
      (node (ref "U8") (pin "17") (pinfunction "A_B_SIDE_17") (pintype "output"))
    )
    (net (code "286") (name "unconnected-(U8-GPIO-Pad15)") (class "Default")
      (node (ref "U8") (pin "15") (pinfunction "GPIO_15") (pintype "output"))
    )
    (net (code "287") (name "unconnected-(U8-NC-Pad3)") (class "Default")
      (node (ref "U8") (pin "3") (pinfunction "NC_3") (pintype "no_connect"))
    )
    (net (code "288") (name "unconnected-(U8-POWER_OK2-Pad20)") (class "Default")
      (node (ref "U8") (pin "20") (pinfunction "POWER_OK2_20") (pintype "output"))
    )
    (net (code "289") (name "unconnected-(U8-POWER_OK3-Pad14)") (class "Default")
      (node (ref "U8") (pin "14") (pinfunction "POWER_OK3_14") (pintype "output"))
    )
    (net (code "290") (name "unconnected-(U9-READY-Pad5)") (class "Default")
      (node (ref "U9") (pin "5") (pinfunction "READY_5") (pintype "passive"))
    )
    (net (code "291") (name "unconnected-(U18-RUP2-Pad12)") (class "Default")
      (node (ref "U18") (pin "12") (pinfunction "RUP2_12") (pintype "output"))
    )
    (net (code "292") (name "unconnected-(U20A-ID-Pad5)") (class "Default")
      (node (ref "U20") (pin "5") (pinfunction "ID_5") (pintype "input"))
    )
    (net (code "293") (name "unconnected-(U22A-PA4-Pad53)") (class "Default")
      (node (ref "U22") (pin "53") (pinfunction "PA4_53") (pintype "bidirectional"))
    )
    (net (code "294") (name "unconnected-(U22A-PB3-Pad192)") (class "Default")
      (node (ref "U22") (pin "192") (pinfunction "PB3_192") (pintype "bidirectional"))
    )
    (net (code "295") (name "unconnected-(U22A-PB4-Pad193)") (class "Default")
      (node (ref "U22") (pin "193") (pinfunction "PB4_193") (pintype "bidirectional"))
    )
    (net (code "296") (name "unconnected-(U22A-PB8-Pad198)") (class "Default")
      (node (ref "U22") (pin "198") (pinfunction "PB8_198") (pintype "bidirectional"))
    )
    (net (code "297") (name "unconnected-(U22A-PB9-Pad199)") (class "Default")
      (node (ref "U22") (pin "199") (pinfunction "PB9_199") (pintype "bidirectional"))
    )
    (net (code "298") (name "unconnected-(U22A-PB14-Pad106)") (class "Default")
      (node (ref "U22") (pin "106") (pinfunction "PB14_106") (pintype "bidirectional"))
    )
    (net (code "299") (name "unconnected-(U22A-PC15-OSC32_OUT-Pad10)") (class "Default")
      (node (ref "U22") (pin "10") (pinfunction "PC15-OSC32_OUT_10") (pintype "bidirectional"))
    )
    (net (code "300") (name "unconnected-(U22A-PD5-Pad169)") (class "Default")
      (node (ref "U22") (pin "169") (pinfunction "PD5_169") (pintype "bidirectional"))
    )
    (net (code "301") (name "unconnected-(U22A-PD11-Pad111)") (class "Default")
      (node (ref "U22") (pin "111") (pinfunction "PD11_111") (pintype "bidirectional"))
    )
    (net (code "302") (name "unconnected-(U22A-PD12-Pad112)") (class "Default")
      (node (ref "U22") (pin "112") (pinfunction "PD12_112") (pintype "bidirectional"))
    )
    (net (code "303") (name "unconnected-(U22A-PD13-Pad113)") (class "Default")
      (node (ref "U22") (pin "113") (pinfunction "PD13_113") (pintype "bidirectional"))
    )
    (net (code "304") (name "unconnected-(U22B-PE2-Pad1)") (class "Default")
      (node (ref "U22") (pin "1") (pinfunction "PE2_1") (pintype "bidirectional"))
    )
    (net (code "305") (name "unconnected-(U22B-PG3-Pad130)") (class "Default")
      (node (ref "U22") (pin "130") (pinfunction "PG3_130") (pintype "bidirectional"))
    )
    (net (code "306") (name "unconnected-(U22B-PG7-Pad134)") (class "Default")
      (node (ref "U22") (pin "134") (pinfunction "PG7_134") (pintype "bidirectional"))
    )
    (net (code "307") (name "unconnected-(U22B-PG12-Pad181)") (class "Default")
      (node (ref "U22") (pin "181") (pinfunction "PG12_181") (pintype "bidirectional"))
    )
    (net (code "308") (name "unconnected-(U22B-PG13-Pad182)") (class "Default")
      (node (ref "U22") (pin "182") (pinfunction "PG13_182") (pintype "bidirectional"))
    )
    (net (code "309") (name "unconnected-(U22B-PH3-Pad47)") (class "Default")
      (node (ref "U22") (pin "47") (pinfunction "PH3_47") (pintype "bidirectional"))
    )
    (net (code "310") (name "unconnected-(U22B-PH6-Pad96)") (class "Default")
      (node (ref "U22") (pin "96") (pinfunction "PH6_96") (pintype "bidirectional"))
    )
    (net (code "311") (name "unconnected-(U22B-PH14-Pad152)") (class "Default")
      (node (ref "U22") (pin "152") (pinfunction "PH14_152") (pintype "bidirectional"))
    )
    (net (code "312") (name "unconnected-(U22B-PH15-Pad153)") (class "Default")
      (node (ref "U22") (pin "153") (pinfunction "PH15_153") (pintype "bidirectional"))
    )
    (net (code "313") (name "unconnected-(U22B-PI1-Pad155)") (class "Default")
      (node (ref "U22") (pin "155") (pinfunction "PI1_155") (pintype "bidirectional"))
    )
    (net (code "314") (name "unconnected-(U22B-PJ7-Pad119)") (class "Default")
      (node (ref "U22") (pin "119") (pinfunction "PJ7_119") (pintype "bidirectional"))
    )
    (net (code "315") (name "unconnected-(U22B-PJ8-Pad120)") (class "Default")
      (node (ref "U22") (pin "120") (pinfunction "PJ8_120") (pintype "bidirectional"))
    )
    (net (code "316") (name "unconnected-(U22B-PJ9-Pad121)") (class "Default")
      (node (ref "U22") (pin "121") (pinfunction "PJ9_121") (pintype "bidirectional"))
    )
    (net (code "317") (name "unconnected-(U22B-PJ12-Pad174)") (class "Default")
      (node (ref "U22") (pin "174") (pinfunction "PJ12_174") (pintype "bidirectional"))
    )
    (net (code "318") (name "unconnected-(U22B-PJ13-Pad175)") (class "Default")
      (node (ref "U22") (pin "175") (pinfunction "PJ13_175") (pintype "bidirectional"))
    )
    (net (code "319") (name "unconnected-(U22C-PK3-Pad186)") (class "Default")
      (node (ref "U22") (pin "186") (pinfunction "PK3_186") (pintype "bidirectional"))
    )
    (net (code "320") (name "unconnected-(U22C-PK7-Pad190)") (class "Default")
      (node (ref "U22") (pin "190") (pinfunction "PK7_190") (pintype "bidirectional"))
    )
    (net (code "321") (name "~{AUD_SD}") (class "Default")
      (node (ref "U11") (pin "1") (pinfunction "O1_1") (pintype "passive"))
      (node (ref "U11") (pin "6") (pinfunction "~{SHDN}_6") (pintype "passive"))
      (node (ref "U14") (pin "6") (pinfunction "~{SD}_6") (pintype "input"))
    )
  )
)
